# SCH_RP2040_Carrier_Board_for_AC_and_Meas.net
KiCad netlist of a schematic drawn in EasyEDA
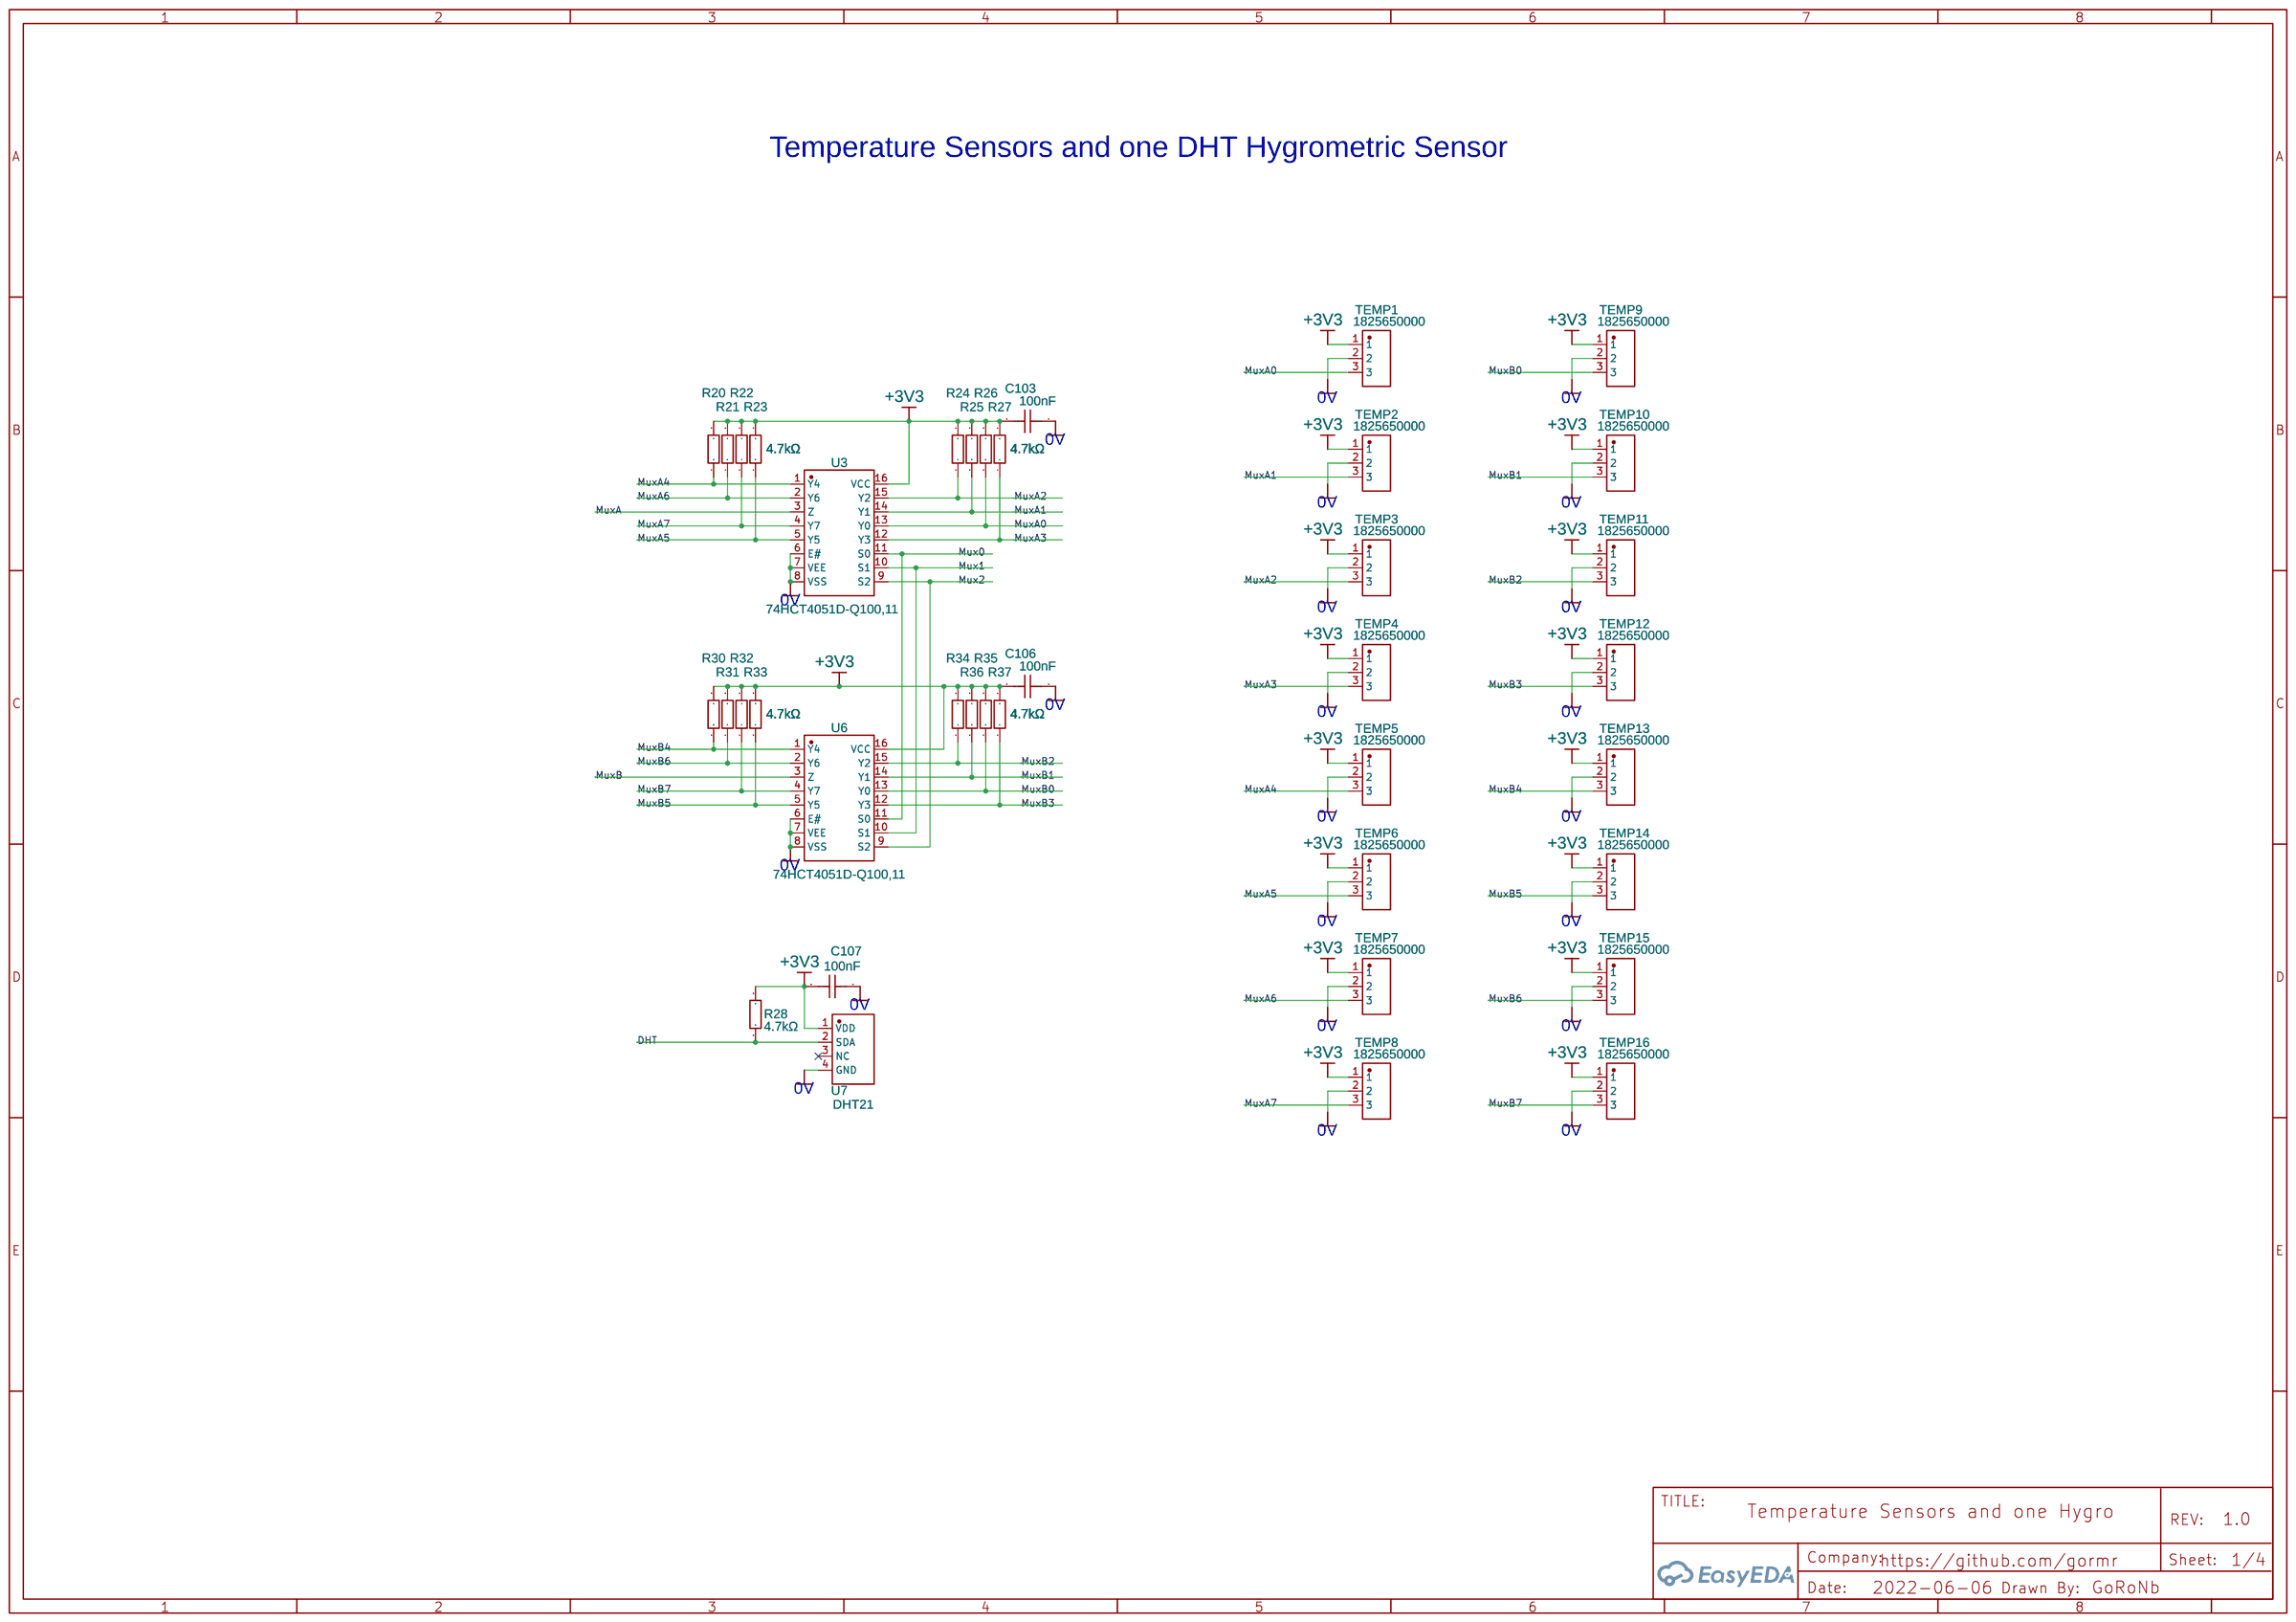
[diagram p0: Temperature/Analog Multiplexer]
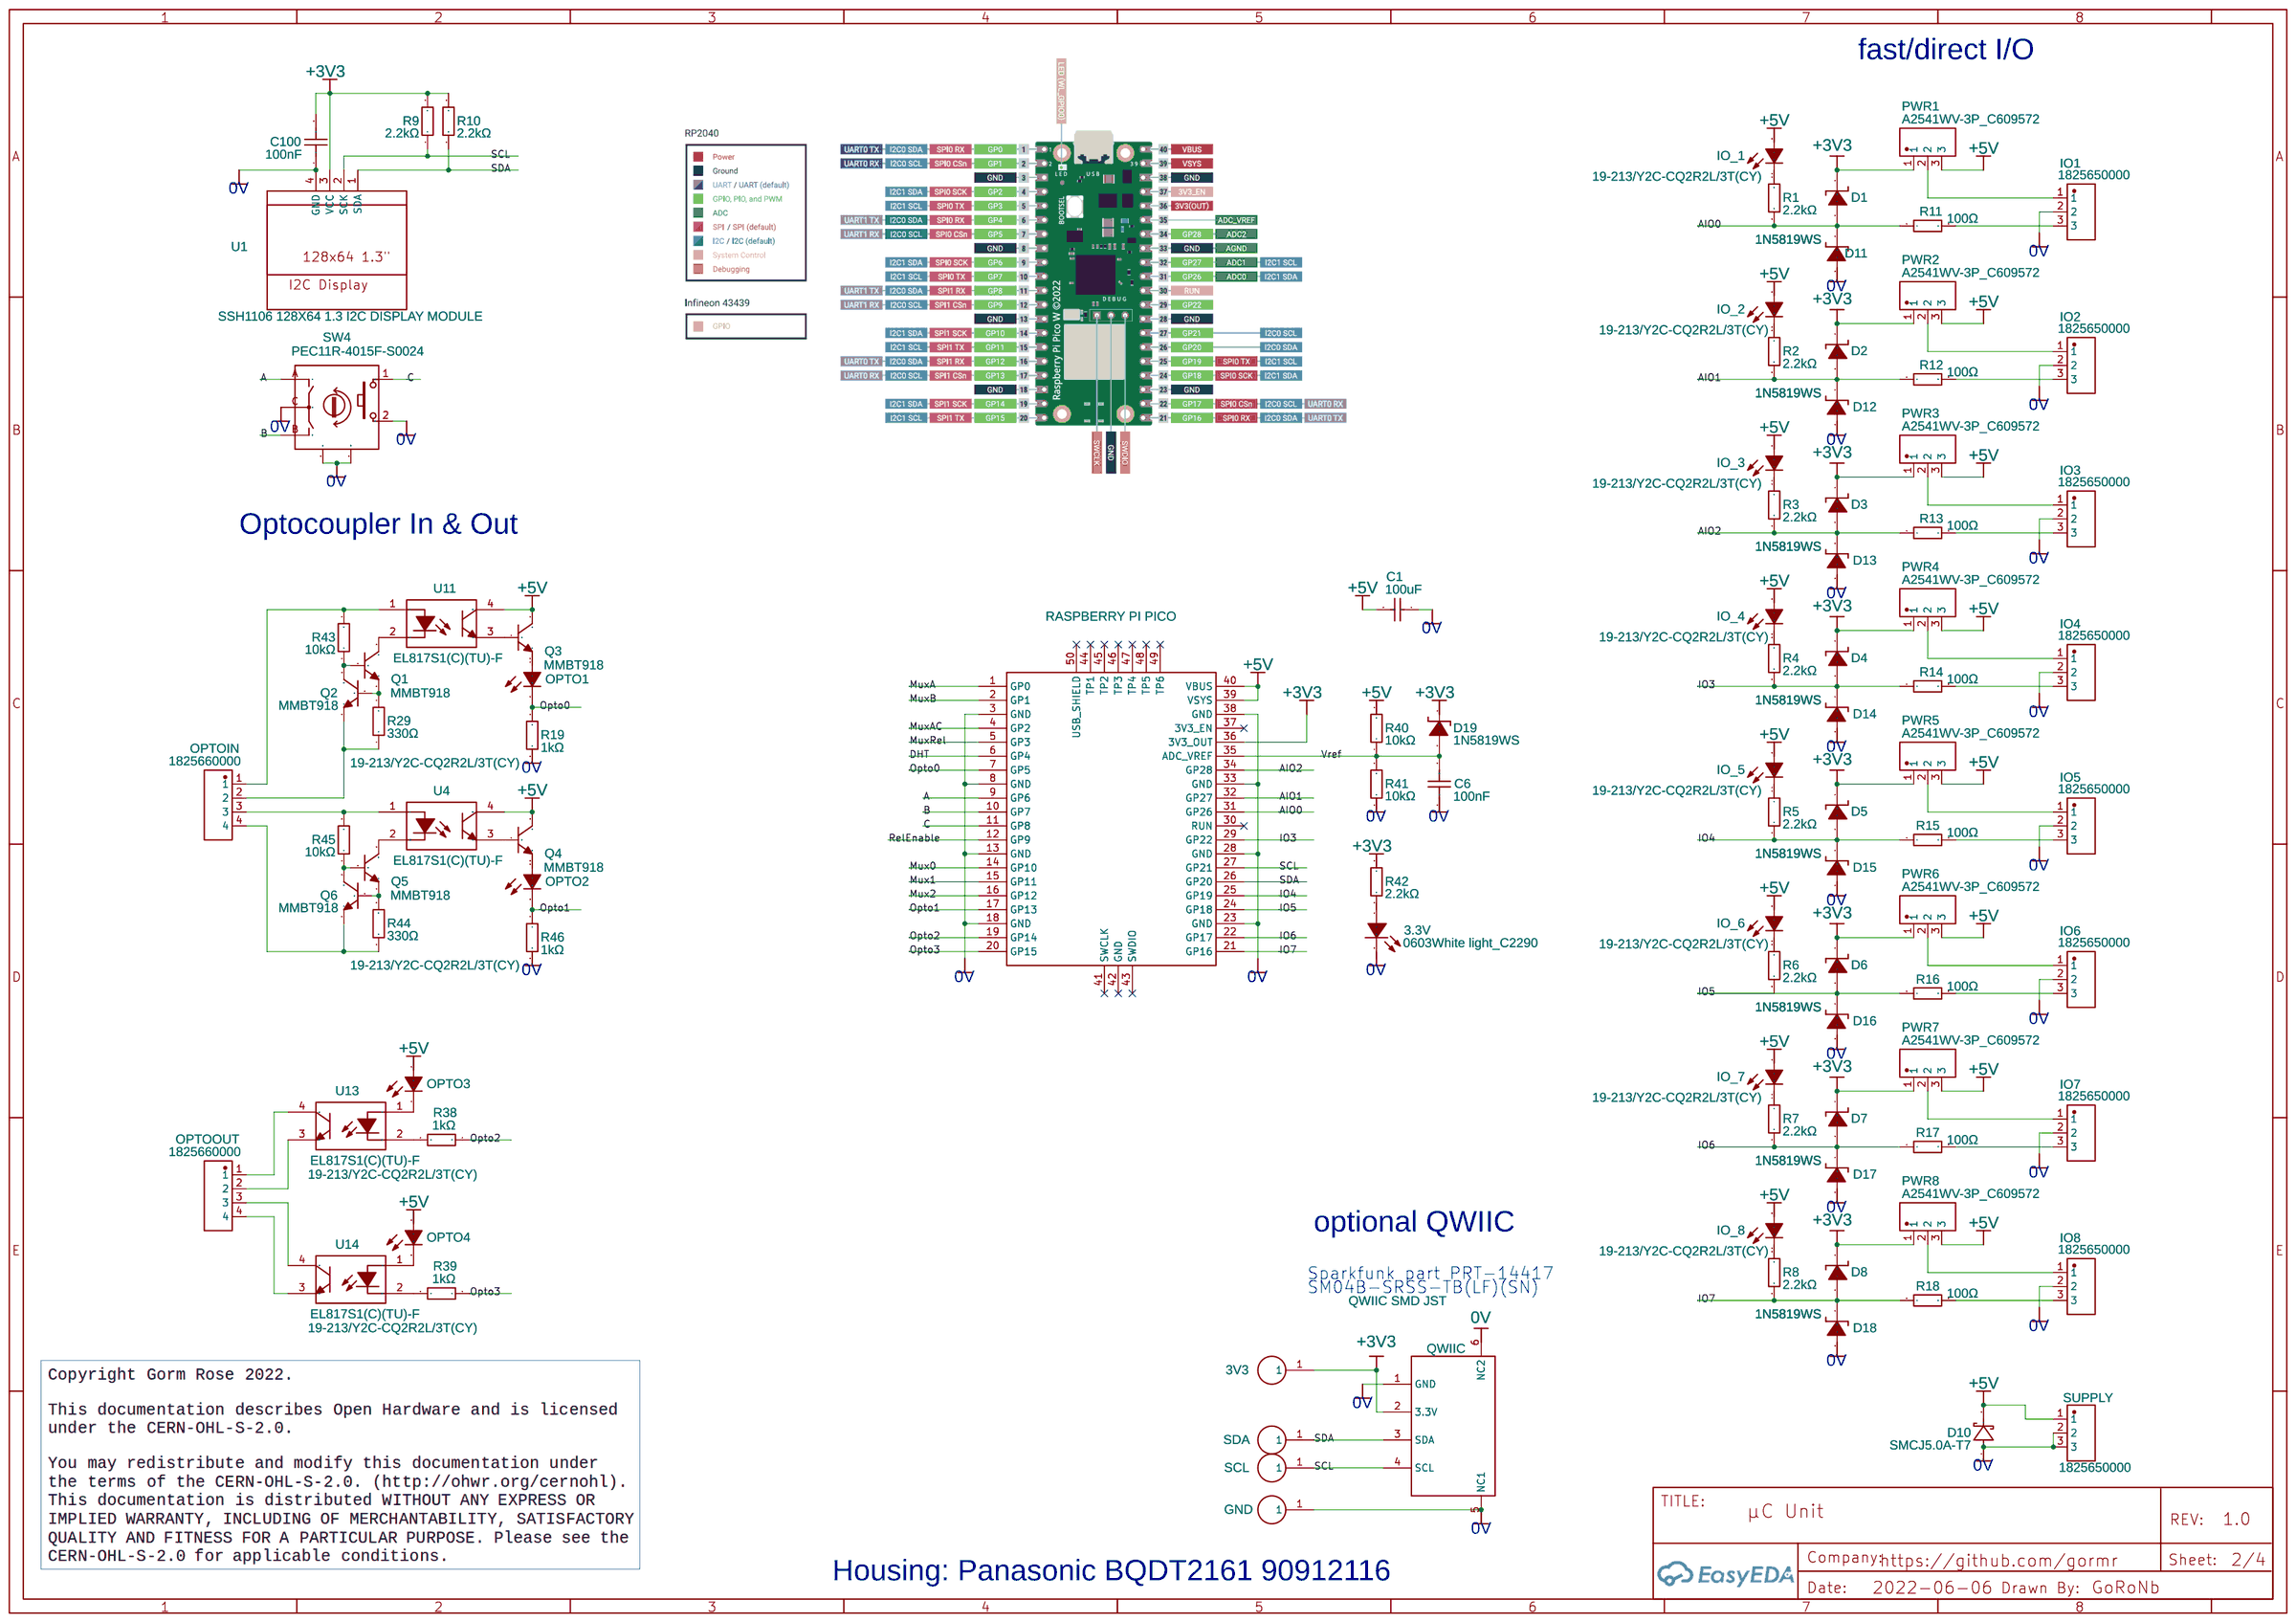
[diagram p1: Controller Unit]
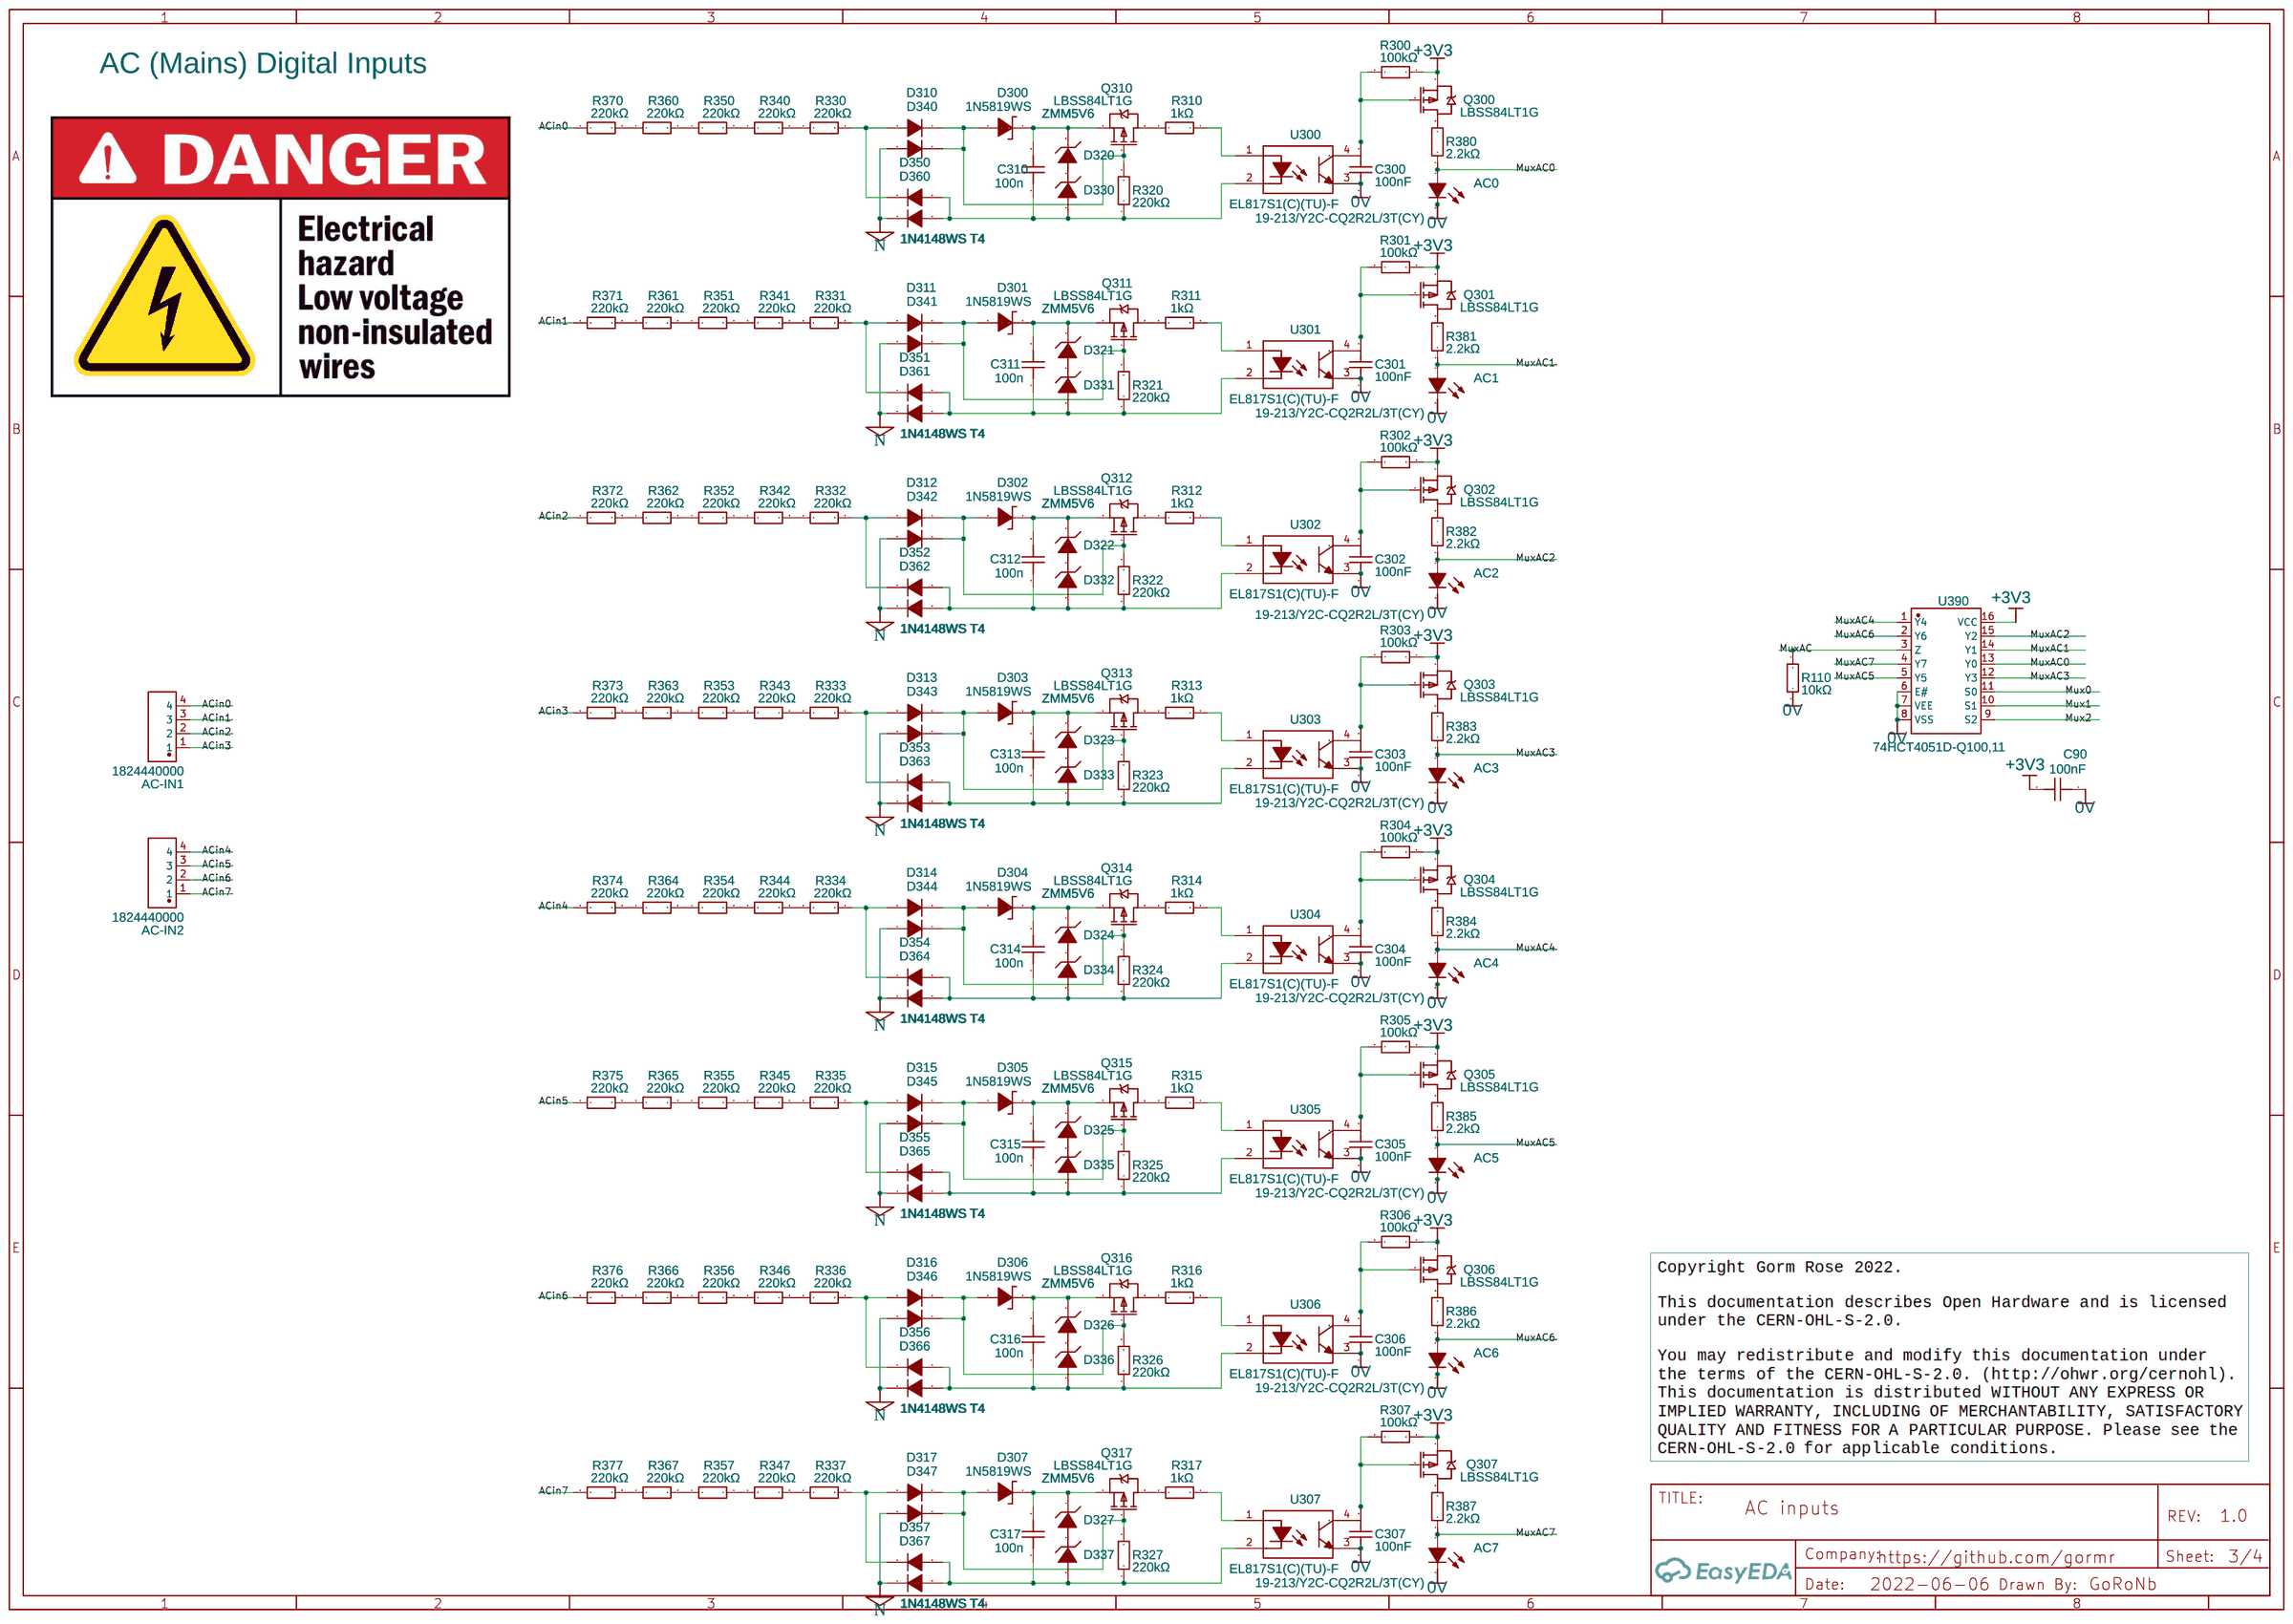
[diagram p2: AC inputs]
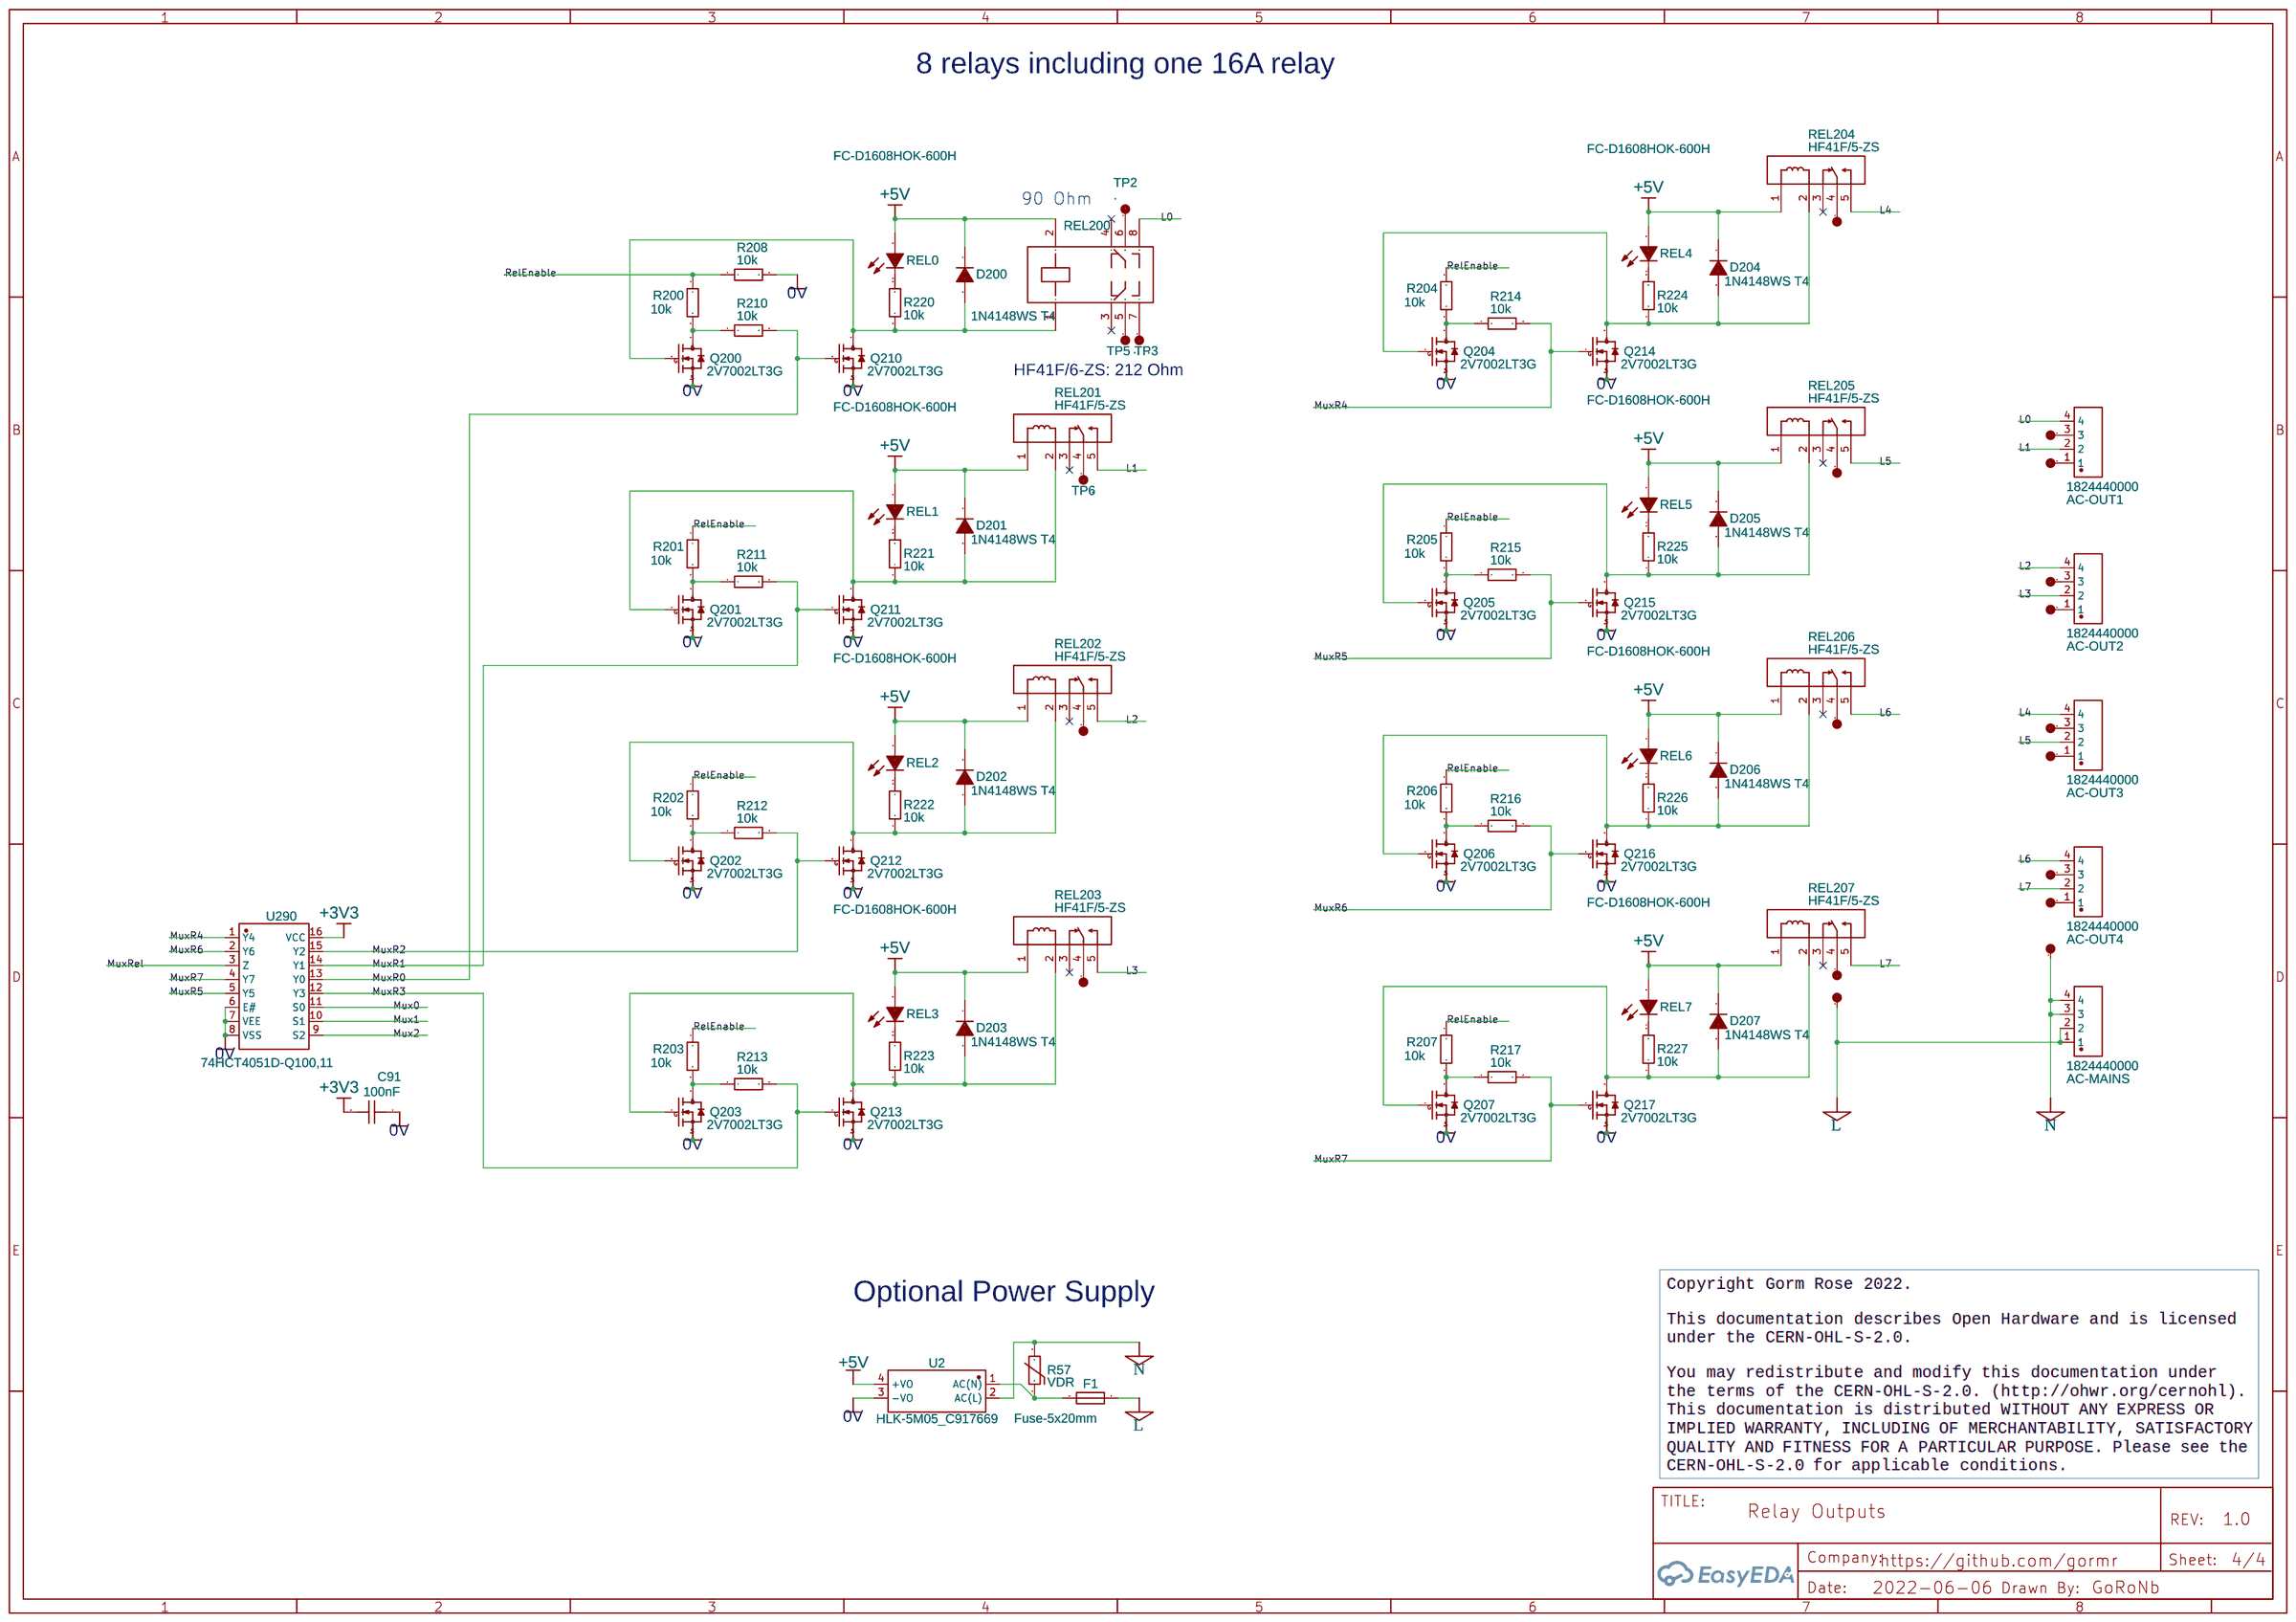
[diagram p3: Relay Outputs]

(export (version "E")
  (design (tool "Eeschema 10.0.6"))
  (components
    (comp (ref "C103")
      (value "100nF")
      (fields
        (field (name "BOM_Manufacturer Part") "CC0603KRX7R9BB104")
        (field (name "BOM_Supplier Part") "C14663")
      )
      (libsource (lib "") (part "CC0603KRX7R9BB104"))
    )
    (comp (ref "C106")
      (value "100nF")
      (fields
        (field (name "BOM_Manufacturer Part") "CC0603KRX7R9BB104")
        (field (name "BOM_Supplier Part") "C14663")
      )
      (libsource (lib "") (part "CC0603KRX7R9BB104"))
    )
    (comp (ref "C107")
      (value "100nF")
      (fields
        (field (name "BOM_Manufacturer Part") "CC0603KRX7R9BB104")
        (field (name "BOM_Supplier Part") "C14663")
      )
      (libsource (lib "") (part "CC0603KRX7R9BB104"))
    )
    (comp (ref "R20")
      (value "4.7kΩ")
      (fields
        (field (name "BOM_Manufacturer Part") "0603WAF4701T5E")
        (field (name "BOM_Supplier Part") "C23162")
      )
      (libsource (lib "") (part "0603WAF4701T5E"))
    )
    (comp (ref "R21")
      (value "4.7kΩ")
      (fields
        (field (name "BOM_Manufacturer Part") "0603WAF4701T5E")
        (field (name "BOM_Supplier Part") "C23162")
      )
      (libsource (lib "") (part "0603WAF4701T5E"))
    )
    (comp (ref "R22")
      (value "4.7kΩ")
      (fields
        (field (name "BOM_Manufacturer Part") "0603WAF4701T5E")
        (field (name "BOM_Supplier Part") "C23162")
      )
      (libsource (lib "") (part "0603WAF4701T5E"))
    )
    (comp (ref "R23")
      (value "4.7kΩ")
      (fields
        (field (name "BOM_Manufacturer Part") "0603WAF4701T5E")
        (field (name "BOM_Supplier Part") "C23162")
      )
      (libsource (lib "") (part "0603WAF4701T5E"))
    )
    (comp (ref "R24")
      (value "4.7kΩ")
      (fields
        (field (name "BOM_Manufacturer Part") "0603WAF4701T5E")
        (field (name "BOM_Supplier Part") "C23162")
      )
      (libsource (lib "") (part "0603WAF4701T5E"))
    )
    (comp (ref "R25")
      (value "4.7kΩ")
      (fields
        (field (name "BOM_Manufacturer Part") "0603WAF4701T5E")
        (field (name "BOM_Supplier Part") "C23162")
      )
      (libsource (lib "") (part "0603WAF4701T5E"))
    )
    (comp (ref "R26")
      (value "4.7kΩ")
      (fields
        (field (name "BOM_Manufacturer Part") "0603WAF4701T5E")
        (field (name "BOM_Supplier Part") "C23162")
      )
      (libsource (lib "") (part "0603WAF4701T5E"))
    )
    (comp (ref "R27")
      (value "4.7kΩ")
      (fields
        (field (name "BOM_Manufacturer Part") "0603WAF4701T5E")
        (field (name "BOM_Supplier Part") "C23162")
      )
      (libsource (lib "") (part "0603WAF4701T5E"))
    )
    (comp (ref "R28")
      (value "4.7kΩ")
      (fields
        (field (name "BOM_Manufacturer Part") "0603WAF4701T5E")
        (field (name "BOM_Supplier Part") "C23162")
      )
      (libsource (lib "") (part "0603WAF4701T5E"))
    )
    (comp (ref "R30")
      (value "4.7kΩ")
      (fields
        (field (name "BOM_Manufacturer Part") "0603WAF4701T5E")
        (field (name "BOM_Supplier Part") "C23162")
      )
      (libsource (lib "") (part "0603WAF4701T5E"))
    )
    (comp (ref "R31")
      (value "4.7kΩ")
      (fields
        (field (name "BOM_Manufacturer Part") "0603WAF4701T5E")
        (field (name "BOM_Supplier Part") "C23162")
      )
      (libsource (lib "") (part "0603WAF4701T5E"))
    )
    (comp (ref "R32")
      (value "4.7kΩ")
      (fields
        (field (name "BOM_Manufacturer Part") "0603WAF4701T5E")
        (field (name "BOM_Supplier Part") "C23162")
      )
      (libsource (lib "") (part "0603WAF4701T5E"))
    )
    (comp (ref "R33")
      (value "4.7kΩ")
      (fields
        (field (name "BOM_Manufacturer Part") "0603WAF4701T5E")
        (field (name "BOM_Supplier Part") "C23162")
      )
      (libsource (lib "") (part "0603WAF4701T5E"))
    )
    (comp (ref "R34")
      (value "4.7kΩ")
      (fields
        (field (name "BOM_Manufacturer Part") "0603WAF4701T5E")
        (field (name "BOM_Supplier Part") "C23162")
      )
      (libsource (lib "") (part "0603WAF4701T5E"))
    )
    (comp (ref "R35")
      (value "4.7kΩ")
      (fields
        (field (name "BOM_Manufacturer Part") "0603WAF4701T5E")
        (field (name "BOM_Supplier Part") "C23162")
      )
      (libsource (lib "") (part "0603WAF4701T5E"))
    )
    (comp (ref "R36")
      (value "4.7kΩ")
      (fields
        (field (name "BOM_Manufacturer Part") "0603WAF4701T5E")
        (field (name "BOM_Supplier Part") "C23162")
      )
      (libsource (lib "") (part "0603WAF4701T5E"))
    )
    (comp (ref "R37")
      (value "4.7kΩ")
      (fields
        (field (name "BOM_Manufacturer Part") "0603WAF4701T5E")
        (field (name "BOM_Supplier Part") "C23162")
      )
      (libsource (lib "") (part "0603WAF4701T5E"))
    )
    (comp (ref "TEMP1")
      (value "1825650000")
      (fields (field (name "BOM_Supplier Part") "281-2043-ND"))
      (libsource (lib "") (part "1825650000"))
    )
    (comp (ref "TEMP2")
      (value "1825650000")
      (fields (field (name "BOM_Supplier Part") "281-2043-ND"))
      (libsource (lib "") (part "1825650000"))
    )
    (comp (ref "TEMP3")
      (value "1825650000")
      (fields (field (name "BOM_Supplier Part") "281-2043-ND"))
      (libsource (lib "") (part "1825650000"))
    )
    (comp (ref "TEMP4")
      (value "1825650000")
      (fields (field (name "BOM_Supplier Part") "281-2043-ND"))
      (libsource (lib "") (part "1825650000"))
    )
    (comp (ref "TEMP5")
      (value "1825650000")
      (fields (field (name "BOM_Supplier Part") "281-2043-ND"))
      (libsource (lib "") (part "1825650000"))
    )
    (comp (ref "TEMP6")
      (value "1825650000")
      (fields (field (name "BOM_Supplier Part") "281-2043-ND"))
      (libsource (lib "") (part "1825650000"))
    )
    (comp (ref "TEMP7")
      (value "1825650000")
      (fields (field (name "BOM_Supplier Part") "281-2043-ND"))
      (libsource (lib "") (part "1825650000"))
    )
    (comp (ref "TEMP8")
      (value "1825650000")
      (fields (field (name "BOM_Supplier Part") "281-2043-ND"))
      (libsource (lib "") (part "1825650000"))
    )
    (comp (ref "TEMP9")
      (value "1825650000")
      (fields (field (name "BOM_Supplier Part") "281-2043-ND"))
      (libsource (lib "") (part "1825650000"))
    )
    (comp (ref "TEMP10")
      (value "1825650000")
      (fields (field (name "BOM_Supplier Part") "281-2043-ND"))
      (libsource (lib "") (part "1825650000"))
    )
    (comp (ref "TEMP11")
      (value "1825650000")
      (fields (field (name "BOM_Supplier Part") "281-2043-ND"))
      (libsource (lib "") (part "1825650000"))
    )
    (comp (ref "TEMP12")
      (value "1825650000")
      (fields (field (name "BOM_Supplier Part") "281-2043-ND"))
      (libsource (lib "") (part "1825650000"))
    )
    (comp (ref "TEMP13")
      (value "1825650000")
      (fields (field (name "BOM_Supplier Part") "281-2043-ND"))
      (libsource (lib "") (part "1825650000"))
    )
    (comp (ref "TEMP14")
      (value "1825650000")
      (fields (field (name "BOM_Supplier Part") "281-2043-ND"))
      (libsource (lib "") (part "1825650000"))
    )
    (comp (ref "TEMP15")
      (value "1825650000")
      (fields (field (name "BOM_Supplier Part") "281-2043-ND"))
      (libsource (lib "") (part "1825650000"))
    )
    (comp (ref "TEMP16")
      (value "1825650000")
      (fields (field (name "BOM_Supplier Part") "281-2043-ND"))
      (libsource (lib "") (part "1825650000"))
    )
    (comp (ref "U3")
      (value "74HCT4051D-Q100,11")
      (fields (field (name "BOM_Supplier Part") "C547698"))
      (libsource (lib "") (part "74HCT4051D-Q100,11"))
    )
    (comp (ref "U6")
      (value "74HCT4051D-Q100,11")
      (fields (field (name "BOM_Supplier Part") "C547698"))
      (libsource (lib "") (part "74HCT4051D-Q100,11"))
    )
    (comp (ref "U7")
      (value "DHT21")
      (fields (field (name "BOM_Supplier Part") "C2880290"))
      (libsource (lib "") (part "DHT21"))
    )
    (comp (ref "3.3V")
      (value "0603White light_C2290")
      (fields
        (field (name "BOM_Manufacturer Part") "0603White light")
        (field (name "BOM_Supplier Part") "C2290")
      )
      (libsource (lib "") (part "0603White light_C2290"))
    )
    (comp (ref "3V3") (value "10mA max.") (libsource (lib "") (part "Testpoint_1")))
    (comp (ref "C1")
      (value "100uF")
      (fields
        (field (name "BOM_Manufacturer Part") "CL31A107MQHNNNE")
        (field (name "BOM_Supplier Part") "C15008")
      )
      (libsource (lib "") (part "CL31A107MQHNNNE"))
    )
    (comp (ref "C6")
      (value "100nF")
      (fields
        (field (name "BOM_Manufacturer Part") "CC0603KRX7R9BB104")
        (field (name "BOM_Supplier Part") "C14663")
      )
      (libsource (lib "") (part "CC0603KRX7R9BB104_1"))
    )
    (comp (ref "C100")
      (value "100nF")
      (fields
        (field (name "BOM_Manufacturer Part") "CC0603KRX7R9BB104")
        (field (name "BOM_Supplier Part") "C14663")
      )
      (libsource (lib "") (part "CC0603KRX7R9BB104"))
    )
    (comp (ref "D1")
      (value "1N5819WS")
      (fields (field (name "BOM_Supplier Part") "C191023"))
      (libsource (lib "") (part "1N5819WS_1"))
    )
    (comp (ref "D2")
      (value "1N5819WS")
      (fields (field (name "BOM_Supplier Part") "C191023"))
      (libsource (lib "") (part "1N5819WS_1"))
    )
    (comp (ref "D3")
      (value "1N5819WS")
      (fields (field (name "BOM_Supplier Part") "C191023"))
      (libsource (lib "") (part "1N5819WS_1"))
    )
    (comp (ref "D4")
      (value "1N5819WS")
      (fields (field (name "BOM_Supplier Part") "C191023"))
      (libsource (lib "") (part "1N5819WS_1"))
    )
    (comp (ref "D5")
      (value "1N5819WS")
      (fields (field (name "BOM_Supplier Part") "C191023"))
      (libsource (lib "") (part "1N5819WS_1"))
    )
    (comp (ref "D6")
      (value "1N5819WS")
      (fields (field (name "BOM_Supplier Part") "C191023"))
      (libsource (lib "") (part "1N5819WS_1"))
    )
    (comp (ref "D7")
      (value "1N5819WS")
      (fields (field (name "BOM_Supplier Part") "C191023"))
      (libsource (lib "") (part "1N5819WS_1"))
    )
    (comp (ref "D8")
      (value "1N5819WS")
      (fields (field (name "BOM_Supplier Part") "C191023"))
      (libsource (lib "") (part "1N5819WS_1"))
    )
    (comp (ref "D10")
      (value "SMCJ5.0A-T7")
      (fields (field (name "BOM_Supplier Part") "C1983017"))
      (libsource (lib "") (part "SMCJ5.0A-T7"))
    )
    (comp (ref "D11")
      (value "1N5819WS")
      (fields (field (name "BOM_Supplier Part") "C191023"))
      (libsource (lib "") (part "1N5819WS"))
    )
    (comp (ref "D12")
      (value "1N5819WS")
      (fields (field (name "BOM_Supplier Part") "C191023"))
      (libsource (lib "") (part "1N5819WS"))
    )
    (comp (ref "D13")
      (value "1N5819WS")
      (fields (field (name "BOM_Supplier Part") "C191023"))
      (libsource (lib "") (part "1N5819WS"))
    )
    (comp (ref "D14")
      (value "1N5819WS")
      (fields (field (name "BOM_Supplier Part") "C191023"))
      (libsource (lib "") (part "1N5819WS"))
    )
    (comp (ref "D15")
      (value "1N5819WS")
      (fields (field (name "BOM_Supplier Part") "C191023"))
      (libsource (lib "") (part "1N5819WS"))
    )
    (comp (ref "D16")
      (value "1N5819WS")
      (fields (field (name "BOM_Supplier Part") "C191023"))
      (libsource (lib "") (part "1N5819WS"))
    )
    (comp (ref "D17")
      (value "1N5819WS")
      (fields (field (name "BOM_Supplier Part") "C191023"))
      (libsource (lib "") (part "1N5819WS"))
    )
    (comp (ref "D18")
      (value "1N5819WS")
      (fields (field (name "BOM_Supplier Part") "C191023"))
      (libsource (lib "") (part "1N5819WS"))
    )
    (comp (ref "D19")
      (value "1N5819WS")
      (fields (field (name "BOM_Supplier Part") "C191023"))
      (libsource (lib "") (part "1N5819WS_2"))
    )
    (comp (ref "GND") (value "10mA max.") (libsource (lib "") (part "Testpoint")))
    (comp (ref "GP1")
      (value "RASPBERRY PI PICO")
      (fields (field (name "BOM_Manufacturer Part") "RPi Pico"))
      (libsource (lib "") (part "RASPBERRY PI PICO"))
    )
    (comp (ref "IO1")
      (value "1825650000")
      (fields (field (name "BOM_Supplier Part") "281-2043-ND"))
      (libsource (lib "") (part "1825650000"))
    )
    (comp (ref "IO2")
      (value "1825650000")
      (fields (field (name "BOM_Supplier Part") "281-2043-ND"))
      (libsource (lib "") (part "1825650000"))
    )
    (comp (ref "IO3")
      (value "1825650000")
      (fields (field (name "BOM_Supplier Part") "281-2043-ND"))
      (libsource (lib "") (part "1825650000"))
    )
    (comp (ref "IO4")
      (value "1825650000")
      (fields (field (name "BOM_Supplier Part") "281-2043-ND"))
      (libsource (lib "") (part "1825650000"))
    )
    (comp (ref "IO5")
      (value "1825650000")
      (fields (field (name "BOM_Supplier Part") "281-2043-ND"))
      (libsource (lib "") (part "1825650000"))
    )
    (comp (ref "IO6")
      (value "1825650000")
      (fields (field (name "BOM_Supplier Part") "281-2043-ND"))
      (libsource (lib "") (part "1825650000"))
    )
    (comp (ref "IO7")
      (value "1825650000")
      (fields (field (name "BOM_Supplier Part") "281-2043-ND"))
      (libsource (lib "") (part "1825650000"))
    )
    (comp (ref "IO8")
      (value "1825650000")
      (fields (field (name "BOM_Supplier Part") "281-2043-ND"))
      (libsource (lib "") (part "1825650000"))
    )
    (comp (ref "IO_1")
      (value "19-213/Y2C-CQ2R2L/3T(CY)")
      (fields (field (name "BOM_Supplier Part") "C72038"))
      (libsource (lib "") (part "FC-D1608HYK-588J"))
    )
    (comp (ref "IO_2")
      (value "19-213/Y2C-CQ2R2L/3T(CY)")
      (fields (field (name "BOM_Supplier Part") "C72038"))
      (libsource (lib "") (part "FC-D1608HYK-588J"))
    )
    (comp (ref "IO_3")
      (value "19-213/Y2C-CQ2R2L/3T(CY)")
      (fields (field (name "BOM_Supplier Part") "C72038"))
      (libsource (lib "") (part "FC-D1608HYK-588J"))
    )
    (comp (ref "IO_4")
      (value "19-213/Y2C-CQ2R2L/3T(CY)")
      (fields (field (name "BOM_Supplier Part") "C72038"))
      (libsource (lib "") (part "FC-D1608HYK-588J"))
    )
    (comp (ref "IO_5")
      (value "19-213/Y2C-CQ2R2L/3T(CY)")
      (fields (field (name "BOM_Supplier Part") "C72038"))
      (libsource (lib "") (part "FC-D1608HYK-588J"))
    )
    (comp (ref "IO_6")
      (value "19-213/Y2C-CQ2R2L/3T(CY)")
      (fields (field (name "BOM_Supplier Part") "C72038"))
      (libsource (lib "") (part "FC-D1608HYK-588J"))
    )
    (comp (ref "IO_7")
      (value "19-213/Y2C-CQ2R2L/3T(CY)")
      (fields (field (name "BOM_Supplier Part") "C72038"))
      (libsource (lib "") (part "FC-D1608HYK-588J"))
    )
    (comp (ref "IO_8")
      (value "19-213/Y2C-CQ2R2L/3T(CY)")
      (fields (field (name "BOM_Supplier Part") "C72038"))
      (libsource (lib "") (part "FC-D1608HYK-588J"))
    )
    (comp (ref "OPTO1")
      (value "19-213/Y2C-CQ2R2L/3T(CY)")
      (fields (field (name "BOM_Supplier Part") "C72038"))
      (libsource (lib "") (part "19-213/Y2C-CQ2R2L/3T(CY)"))
    )
    (comp (ref "OPTO2")
      (value "19-213/Y2C-CQ2R2L/3T(CY)")
      (fields (field (name "BOM_Supplier Part") "C72038"))
      (libsource (lib "") (part "19-213/Y2C-CQ2R2L/3T(CY)"))
    )
    (comp (ref "OPTO3")
      (value "19-213/Y2C-CQ2R2L/3T(CY)")
      (fields (field (name "BOM_Supplier Part") "C72038"))
      (libsource (lib "") (part "19-213/Y2C-CQ2R2L/3T(CY)"))
    )
    (comp (ref "OPTO4")
      (value "19-213/Y2C-CQ2R2L/3T(CY)")
      (fields (field (name "BOM_Supplier Part") "C72038"))
      (libsource (lib "") (part "19-213/Y2C-CQ2R2L/3T(CY)"))
    )
    (comp (ref "OPTOIN")
      (value "1825660000")
      (fields (field (name "BOM_Supplier Part") "281-2044-ND"))
      (libsource (lib "") (part "1825660000_1"))
    )
    (comp (ref "OPTOOUT")
      (value "1825660000")
      (fields (field (name "BOM_Supplier Part") "281-2044-ND"))
      (libsource (lib "") (part "1825660000"))
    )
    (comp (ref "PWR1")
      (value "A2541WV-3P_C609572")
      (fields
        (field (name "BOM_Manufacturer Part") "A2541WV-3P")
        (field (name "BOM_Supplier Part") "C609572")
      )
      (libsource (lib "") (part "A2541WV-3P_C609572"))
    )
    (comp (ref "PWR2")
      (value "A2541WV-3P_C609572")
      (fields
        (field (name "BOM_Manufacturer Part") "A2541WV-3P")
        (field (name "BOM_Supplier Part") "C609572")
      )
      (libsource (lib "") (part "A2541WV-3P_C609572"))
    )
    (comp (ref "PWR3")
      (value "A2541WV-3P_C609572")
      (fields
        (field (name "BOM_Manufacturer Part") "A2541WV-3P")
        (field (name "BOM_Supplier Part") "C609572")
      )
      (libsource (lib "") (part "A2541WV-3P_C609572"))
    )
    (comp (ref "PWR4")
      (value "A2541WV-3P_C609572")
      (fields
        (field (name "BOM_Manufacturer Part") "A2541WV-3P")
        (field (name "BOM_Supplier Part") "C609572")
      )
      (libsource (lib "") (part "A2541WV-3P_C609572"))
    )
    (comp (ref "PWR5")
      (value "A2541WV-3P_C609572")
      (fields
        (field (name "BOM_Manufacturer Part") "A2541WV-3P")
        (field (name "BOM_Supplier Part") "C609572")
      )
      (libsource (lib "") (part "A2541WV-3P_C609572"))
    )
    (comp (ref "PWR6")
      (value "A2541WV-3P_C609572")
      (fields
        (field (name "BOM_Manufacturer Part") "A2541WV-3P")
        (field (name "BOM_Supplier Part") "C609572")
      )
      (libsource (lib "") (part "A2541WV-3P_C609572"))
    )
    (comp (ref "PWR7")
      (value "A2541WV-3P_C609572")
      (fields
        (field (name "BOM_Manufacturer Part") "A2541WV-3P")
        (field (name "BOM_Supplier Part") "C609572")
      )
      (libsource (lib "") (part "A2541WV-3P_C609572"))
    )
    (comp (ref "PWR8")
      (value "A2541WV-3P_C609572")
      (fields
        (field (name "BOM_Manufacturer Part") "A2541WV-3P")
        (field (name "BOM_Supplier Part") "C609572")
      )
      (libsource (lib "") (part "A2541WV-3P_C609572"))
    )
    (comp (ref "Q1")
      (value "MMBT918")
      (fields (field (name "BOM_Supplier Part") "C184118"))
      (libsource (lib "") (part "MMBT918"))
    )
    (comp (ref "Q2")
      (value "MMBT918")
      (fields (field (name "BOM_Supplier Part") "C184118"))
      (libsource (lib "") (part "MMBT918_1"))
    )
    (comp (ref "Q3")
      (value "MMBT918")
      (fields (field (name "BOM_Supplier Part") "C184118"))
      (libsource (lib "") (part "MMBT918"))
    )
    (comp (ref "Q4")
      (value "MMBT918")
      (fields (field (name "BOM_Supplier Part") "C184118"))
      (libsource (lib "") (part "MMBT918"))
    )
    (comp (ref "Q5")
      (value "MMBT918")
      (fields (field (name "BOM_Supplier Part") "C184118"))
      (libsource (lib "") (part "MMBT918"))
    )
    (comp (ref "Q6")
      (value "MMBT918")
      (fields (field (name "BOM_Supplier Part") "C184118"))
      (libsource (lib "") (part "MMBT918_1"))
    )
    (comp (ref "QWIIC")
      (value "QWIIC SMD JST")
      (fields
        (field (name "BOM_Manufacturer Part") "SM04B-SRSS-TB(LF)(SN)")
        (field (name "BOM_Supplier Part") "C160404")
      )
      (libsource (lib "") (part "QWIIC SMD JST"))
    )
    (comp (ref "R1")
      (value "2.2kΩ")
      (fields
        (field (name "BOM_Manufacturer Part") "0603WAF2201T5E")
        (field (name "BOM_Supplier Part") "C4190")
      )
      (libsource (lib "") (part "0603WAF2201T5E_1"))
    )
    (comp (ref "R2")
      (value "2.2kΩ")
      (fields
        (field (name "BOM_Manufacturer Part") "0603WAF2201T5E")
        (field (name "BOM_Supplier Part") "C4190")
      )
      (libsource (lib "") (part "0603WAF2201T5E_1"))
    )
    (comp (ref "R3")
      (value "2.2kΩ")
      (fields
        (field (name "BOM_Manufacturer Part") "0603WAF2201T5E")
        (field (name "BOM_Supplier Part") "C4190")
      )
      (libsource (lib "") (part "0603WAF2201T5E_1"))
    )
    (comp (ref "R4")
      (value "2.2kΩ")
      (fields
        (field (name "BOM_Manufacturer Part") "0603WAF2201T5E")
        (field (name "BOM_Supplier Part") "C4190")
      )
      (libsource (lib "") (part "0603WAF2201T5E_1"))
    )
    (comp (ref "R5")
      (value "2.2kΩ")
      (fields
        (field (name "BOM_Manufacturer Part") "0603WAF2201T5E")
        (field (name "BOM_Supplier Part") "C4190")
      )
      (libsource (lib "") (part "0603WAF2201T5E_1"))
    )
    (comp (ref "R6")
      (value "2.2kΩ")
      (fields
        (field (name "BOM_Manufacturer Part") "0603WAF2201T5E")
        (field (name "BOM_Supplier Part") "C4190")
      )
      (libsource (lib "") (part "0603WAF2201T5E_1"))
    )
    (comp (ref "R7")
      (value "2.2kΩ")
      (fields
        (field (name "BOM_Manufacturer Part") "0603WAF2201T5E")
        (field (name "BOM_Supplier Part") "C4190")
      )
      (libsource (lib "") (part "0603WAF2201T5E_1"))
    )
    (comp (ref "R8")
      (value "2.2kΩ")
      (fields
        (field (name "BOM_Manufacturer Part") "0603WAF2201T5E")
        (field (name "BOM_Supplier Part") "C4190")
      )
      (libsource (lib "") (part "0603WAF2201T5E_1"))
    )
    (comp (ref "R9")
      (value "2.2kΩ")
      (fields
        (field (name "BOM_Manufacturer Part") "0603WAF2201T5E")
        (field (name "BOM_Supplier Part") "C4190")
      )
      (libsource (lib "") (part "0603WAF2201T5E"))
    )
    (comp (ref "R10")
      (value "2.2kΩ")
      (fields
        (field (name "BOM_Manufacturer Part") "0603WAF2201T5E")
        (field (name "BOM_Supplier Part") "C4190")
      )
      (libsource (lib "") (part "0603WAF2201T5E"))
    )
    (comp (ref "R11")
      (value "100Ω")
      (fields
        (field (name "BOM_Manufacturer Part") "0603WAF1000T5E")
        (field (name "BOM_Supplier Part") "C22775")
      )
      (libsource (lib "") (part "0603WAF1000T5E"))
    )
    (comp (ref "R12")
      (value "100Ω")
      (fields
        (field (name "BOM_Manufacturer Part") "0603WAF1000T5E")
        (field (name "BOM_Supplier Part") "C22775")
      )
      (libsource (lib "") (part "0603WAF1000T5E"))
    )
    (comp (ref "R13")
      (value "100Ω")
      (fields
        (field (name "BOM_Manufacturer Part") "0603WAF1000T5E")
        (field (name "BOM_Supplier Part") "C22775")
      )
      (libsource (lib "") (part "0603WAF1000T5E"))
    )
    (comp (ref "R14")
      (value "100Ω")
      (fields
        (field (name "BOM_Manufacturer Part") "0603WAF1000T5E")
        (field (name "BOM_Supplier Part") "C22775")
      )
      (libsource (lib "") (part "0603WAF1000T5E"))
    )
    (comp (ref "R15")
      (value "100Ω")
      (fields
        (field (name "BOM_Manufacturer Part") "0603WAF1000T5E")
        (field (name "BOM_Supplier Part") "C22775")
      )
      (libsource (lib "") (part "0603WAF1000T5E"))
    )
    (comp (ref "R16")
      (value "100Ω")
      (fields
        (field (name "BOM_Manufacturer Part") "0603WAF1000T5E")
        (field (name "BOM_Supplier Part") "C22775")
      )
      (libsource (lib "") (part "0603WAF1000T5E"))
    )
    (comp (ref "R17")
      (value "100Ω")
      (fields
        (field (name "BOM_Manufacturer Part") "0603WAF1000T5E")
        (field (name "BOM_Supplier Part") "C22775")
      )
      (libsource (lib "") (part "0603WAF1000T5E"))
    )
    (comp (ref "R18")
      (value "100Ω")
      (fields
        (field (name "BOM_Manufacturer Part") "0603WAF1000T5E")
        (field (name "BOM_Supplier Part") "C22775")
      )
      (libsource (lib "") (part "0603WAF1000T5E"))
    )
    (comp (ref "R19")
      (value "1kΩ")
      (fields
        (field (name "BOM_Manufacturer Part") "0603WAF1001T5E")
        (field (name "BOM_Supplier Part") "C21190")
      )
      (libsource (lib "") (part "0603WAF1001T5E"))
    )
    (comp (ref "R29")
      (value "330Ω")
      (fields
        (field (name "BOM_Manufacturer Part") "0603WAF3300T5E")
        (field (name "BOM_Supplier Part") "C23138")
      )
      (libsource (lib "") (part "0603WAF3300T5E"))
    )
    (comp (ref "R38")
      (value "1kΩ")
      (fields
        (field (name "BOM_Manufacturer Part") "0603WAF1001T5E")
        (field (name "BOM_Supplier Part") "C21190")
      )
      (libsource (lib "") (part "0603WAF1001T5E_1"))
    )
    (comp (ref "R39")
      (value "1kΩ")
      (fields
        (field (name "BOM_Manufacturer Part") "0603WAF1001T5E")
        (field (name "BOM_Supplier Part") "C21190")
      )
      (libsource (lib "") (part "0603WAF1001T5E_1"))
    )
    (comp (ref "R40")
      (value "10kΩ")
      (fields
        (field (name "BOM_Manufacturer Part") "0603WAF1002T5E")
        (field (name "BOM_Supplier Part") "C25804")
      )
      (libsource (lib "") (part "0603WAF1002T5E"))
    )
    (comp (ref "R41")
      (value "10kΩ")
      (fields
        (field (name "BOM_Manufacturer Part") "0603WAF1002T5E")
        (field (name "BOM_Supplier Part") "C25804")
      )
      (libsource (lib "") (part "0603WAF1002T5E"))
    )
    (comp (ref "R42")
      (value "2.2kΩ")
      (fields
        (field (name "BOM_Manufacturer Part") "0603WAF2201T5E")
        (field (name "BOM_Supplier Part") "C4190")
      )
      (libsource (lib "") (part "0603WAF2201T5E"))
    )
    (comp (ref "R43")
      (value "10kΩ")
      (fields
        (field (name "BOM_Manufacturer Part") "0603WAF1002T5E")
        (field (name "BOM_Supplier Part") "C25804")
      )
      (libsource (lib "") (part "0603WAF1002T5E"))
    )
    (comp (ref "R44")
      (value "330Ω")
      (fields
        (field (name "BOM_Manufacturer Part") "0603WAF3300T5E")
        (field (name "BOM_Supplier Part") "C23138")
      )
      (libsource (lib "") (part "0603WAF3300T5E"))
    )
    (comp (ref "R45")
      (value "10kΩ")
      (fields
        (field (name "BOM_Manufacturer Part") "0603WAF1002T5E")
        (field (name "BOM_Supplier Part") "C25804")
      )
      (libsource (lib "") (part "0603WAF1002T5E"))
    )
    (comp (ref "R46")
      (value "1kΩ")
      (fields
        (field (name "BOM_Manufacturer Part") "0603WAF1001T5E")
        (field (name "BOM_Supplier Part") "C21190")
      )
      (libsource (lib "") (part "0603WAF1001T5E"))
    )
    (comp (ref "SCL") (value "10mA max.") (libsource (lib "") (part "Testpoint_3")))
    (comp (ref "SDA") (value "10mA max.") (libsource (lib "") (part "Testpoint_2")))
    (comp (ref "SUPPLY")
      (value "1825650000")
      (fields (field (name "BOM_Supplier Part") "281-2043-ND"))
      (libsource (lib "") (part "1825650000_1"))
    )
    (comp (ref "SW4")
      (value "PEC11R-4015F-S0024")
      (fields (field (name "BOM_Supplier Part") "C143789"))
      (libsource (lib "") (part "PEC11R-4015F-S0024"))
    )
    (comp (ref "U1")
      (value "SSH1106 128X64 1.3 I2C DISPLAY MODULE")
      (libsource (lib "") (part "SSH1106 128X64 1.3 I2C DISPLAY MODULE"))
    )
    (comp (ref "U4")
      (value "EL817S1(C)(TU)-F")
      (fields (field (name "BOM_Supplier Part") "C106900"))
      (libsource (lib "") (part "EL817S1(C)(TU)-F_1"))
    )
    (comp (ref "U11")
      (value "EL817S1(C)(TU)-F")
      (fields (field (name "BOM_Supplier Part") "C106900"))
      (libsource (lib "") (part "EL817S1(C)(TU)-F_1"))
    )
    (comp (ref "U13")
      (value "EL817S1(C)(TU)-F")
      (fields (field (name "BOM_Supplier Part") "C106900"))
      (libsource (lib "") (part "EL817S1(C)(TU)-F"))
    )
    (comp (ref "U14")
      (value "EL817S1(C)(TU)-F")
      (fields (field (name "BOM_Supplier Part") "C106900"))
      (libsource (lib "") (part "EL817S1(C)(TU)-F"))
    )
    (comp (ref "AC-IN1")
      (value "1824440000")
      (fields (field (name "BOM_Supplier Part") "281-2022-ND"))
      (libsource (lib "") (part "1824440000"))
    )
    (comp (ref "AC-IN2")
      (value "1824440000")
      (fields (field (name "BOM_Supplier Part") "281-2022-ND"))
      (libsource (lib "") (part "1824440000"))
    )
    (comp (ref "AC0")
      (value "19-213/Y2C-CQ2R2L/3T(CY)")
      (fields (field (name "BOM_Supplier Part") "C72038"))
      (libsource (lib "") (part "19-213/Y2C-CQ2R2L/3T(CY)"))
    )
    (comp (ref "AC1")
      (value "19-213/Y2C-CQ2R2L/3T(CY)")
      (fields (field (name "BOM_Supplier Part") "C72038"))
      (libsource (lib "") (part "19-213/Y2C-CQ2R2L/3T(CY)"))
    )
    (comp (ref "AC2")
      (value "19-213/Y2C-CQ2R2L/3T(CY)")
      (fields (field (name "BOM_Supplier Part") "C72038"))
      (libsource (lib "") (part "19-213/Y2C-CQ2R2L/3T(CY)"))
    )
    (comp (ref "AC3")
      (value "19-213/Y2C-CQ2R2L/3T(CY)")
      (fields (field (name "BOM_Supplier Part") "C72038"))
      (libsource (lib "") (part "19-213/Y2C-CQ2R2L/3T(CY)"))
    )
    (comp (ref "AC4")
      (value "19-213/Y2C-CQ2R2L/3T(CY)")
      (fields (field (name "BOM_Supplier Part") "C72038"))
      (libsource (lib "") (part "19-213/Y2C-CQ2R2L/3T(CY)"))
    )
    (comp (ref "AC5")
      (value "19-213/Y2C-CQ2R2L/3T(CY)")
      (fields (field (name "BOM_Supplier Part") "C72038"))
      (libsource (lib "") (part "19-213/Y2C-CQ2R2L/3T(CY)"))
    )
    (comp (ref "AC6")
      (value "19-213/Y2C-CQ2R2L/3T(CY)")
      (fields (field (name "BOM_Supplier Part") "C72038"))
      (libsource (lib "") (part "19-213/Y2C-CQ2R2L/3T(CY)"))
    )
    (comp (ref "AC7")
      (value "19-213/Y2C-CQ2R2L/3T(CY)")
      (fields (field (name "BOM_Supplier Part") "C72038"))
      (libsource (lib "") (part "19-213/Y2C-CQ2R2L/3T(CY)"))
    )
    (comp (ref "C90")
      (value "100nF")
      (fields
        (field (name "BOM_Manufacturer Part") "CC0603KRX7R9BB104")
        (field (name "BOM_Supplier Part") "C14663")
      )
      (libsource (lib "") (part "CC0603KRX7R9BB104_1"))
    )
    (comp (ref "C300")
      (value "100nF")
      (fields
        (field (name "BOM_Manufacturer Part") "CC0603KRX7R9BB104")
        (field (name "BOM_Supplier Part") "C14663")
      )
      (libsource (lib "") (part "CC0603KRX7R9BB104"))
    )
    (comp (ref "C301")
      (value "100nF")
      (fields
        (field (name "BOM_Manufacturer Part") "CC0603KRX7R9BB104")
        (field (name "BOM_Supplier Part") "C14663")
      )
      (libsource (lib "") (part "CC0603KRX7R9BB104"))
    )
    (comp (ref "C302")
      (value "100nF")
      (fields
        (field (name "BOM_Manufacturer Part") "CC0603KRX7R9BB104")
        (field (name "BOM_Supplier Part") "C14663")
      )
      (libsource (lib "") (part "CC0603KRX7R9BB104"))
    )
    (comp (ref "C303")
      (value "100nF")
      (fields
        (field (name "BOM_Manufacturer Part") "CC0603KRX7R9BB104")
        (field (name "BOM_Supplier Part") "C14663")
      )
      (libsource (lib "") (part "CC0603KRX7R9BB104"))
    )
    (comp (ref "C304")
      (value "100nF")
      (fields
        (field (name "BOM_Manufacturer Part") "CC0603KRX7R9BB104")
        (field (name "BOM_Supplier Part") "C14663")
      )
      (libsource (lib "") (part "CC0603KRX7R9BB104"))
    )
    (comp (ref "C305")
      (value "100nF")
      (fields
        (field (name "BOM_Manufacturer Part") "CC0603KRX7R9BB104")
        (field (name "BOM_Supplier Part") "C14663")
      )
      (libsource (lib "") (part "CC0603KRX7R9BB104"))
    )
    (comp (ref "C306")
      (value "100nF")
      (fields
        (field (name "BOM_Manufacturer Part") "CC0603KRX7R9BB104")
        (field (name "BOM_Supplier Part") "C14663")
      )
      (libsource (lib "") (part "CC0603KRX7R9BB104"))
    )
    (comp (ref "C307")
      (value "100nF")
      (fields
        (field (name "BOM_Manufacturer Part") "CC0603KRX7R9BB104")
        (field (name "BOM_Supplier Part") "C14663")
      )
      (libsource (lib "") (part "CC0603KRX7R9BB104"))
    )
    (comp (ref "C310") (value "100n") (libsource (lib "") (part "CC0603JRX7R8BB104")))
    (comp (ref "C311") (value "100n") (libsource (lib "") (part "CC0603JRX7R8BB104")))
    (comp (ref "C312") (value "100n") (libsource (lib "") (part "CC0603JRX7R8BB104")))
    (comp (ref "C313") (value "100n") (libsource (lib "") (part "CC0603JRX7R8BB104")))
    (comp (ref "C314") (value "100n") (libsource (lib "") (part "CC0603JRX7R8BB104")))
    (comp (ref "C315") (value "100n") (libsource (lib "") (part "CC0603JRX7R8BB104")))
    (comp (ref "C316") (value "100n") (libsource (lib "") (part "CC0603JRX7R8BB104")))
    (comp (ref "C317") (value "100n") (libsource (lib "") (part "CC0603JRX7R8BB104")))
    (comp (ref "D300")
      (value "1N5819WS")
      (fields (field (name "BOM_Supplier Part") "C191023"))
      (libsource (lib "") (part "1N5819WS"))
    )
    (comp (ref "D301")
      (value "1N5819WS")
      (fields (field (name "BOM_Supplier Part") "C191023"))
      (libsource (lib "") (part "1N5819WS"))
    )
    (comp (ref "D302")
      (value "1N5819WS")
      (fields (field (name "BOM_Supplier Part") "C191023"))
      (libsource (lib "") (part "1N5819WS"))
    )
    (comp (ref "D303")
      (value "1N5819WS")
      (fields (field (name "BOM_Supplier Part") "C191023"))
      (libsource (lib "") (part "1N5819WS"))
    )
    (comp (ref "D304")
      (value "1N5819WS")
      (fields (field (name "BOM_Supplier Part") "C191023"))
      (libsource (lib "") (part "1N5819WS"))
    )
    (comp (ref "D305")
      (value "1N5819WS")
      (fields (field (name "BOM_Supplier Part") "C191023"))
      (libsource (lib "") (part "1N5819WS"))
    )
    (comp (ref "D306")
      (value "1N5819WS")
      (fields (field (name "BOM_Supplier Part") "C191023"))
      (libsource (lib "") (part "1N5819WS"))
    )
    (comp (ref "D307")
      (value "1N5819WS")
      (fields (field (name "BOM_Supplier Part") "C191023"))
      (libsource (lib "") (part "1N5819WS"))
    )
    (comp (ref "D310")
      (value "1N4148WS T4")
      (fields (field (name "BOM_Manufacturer Part") "1N4148WS") (field (name "BOM_Supplier Part") "C2128"))
      (libsource (lib "") (part "1N4148WS T4"))
    )
    (comp (ref "D311")
      (value "1N4148WS T4")
      (fields (field (name "BOM_Manufacturer Part") "1N4148WS") (field (name "BOM_Supplier Part") "C2128"))
      (libsource (lib "") (part "1N4148WS T4"))
    )
    (comp (ref "D312")
      (value "1N4148WS T4")
      (fields (field (name "BOM_Manufacturer Part") "1N4148WS") (field (name "BOM_Supplier Part") "C2128"))
      (libsource (lib "") (part "1N4148WS T4"))
    )
    (comp (ref "D313")
      (value "1N4148WS T4")
      (fields (field (name "BOM_Manufacturer Part") "1N4148WS") (field (name "BOM_Supplier Part") "C2128"))
      (libsource (lib "") (part "1N4148WS T4"))
    )
    (comp (ref "D314")
      (value "1N4148WS T4")
      (fields (field (name "BOM_Manufacturer Part") "1N4148WS") (field (name "BOM_Supplier Part") "C2128"))
      (libsource (lib "") (part "1N4148WS T4"))
    )
    (comp (ref "D315")
      (value "1N4148WS T4")
      (fields (field (name "BOM_Manufacturer Part") "1N4148WS") (field (name "BOM_Supplier Part") "C2128"))
      (libsource (lib "") (part "1N4148WS T4"))
    )
    (comp (ref "D316")
      (value "1N4148WS T4")
      (fields (field (name "BOM_Manufacturer Part") "1N4148WS") (field (name "BOM_Supplier Part") "C2128"))
      (libsource (lib "") (part "1N4148WS T4"))
    )
    (comp (ref "D317")
      (value "1N4148WS T4")
      (fields (field (name "BOM_Manufacturer Part") "1N4148WS") (field (name "BOM_Supplier Part") "C2128"))
      (libsource (lib "") (part "1N4148WS T4"))
    )
    (comp (ref "D320")
      (value "ZMM5V6")
      (fields (field (name "BOM_Supplier Part") "C8062"))
      (libsource (lib "") (part "ZMM5V6"))
    )
    (comp (ref "D321")
      (value "ZMM5V6")
      (fields (field (name "BOM_Supplier Part") "C8062"))
      (libsource (lib "") (part "ZMM5V6"))
    )
    (comp (ref "D322")
      (value "ZMM5V6")
      (fields (field (name "BOM_Supplier Part") "C8062"))
      (libsource (lib "") (part "ZMM5V6"))
    )
    (comp (ref "D323")
      (value "ZMM5V6")
      (fields (field (name "BOM_Supplier Part") "C8062"))
      (libsource (lib "") (part "ZMM5V6"))
    )
    (comp (ref "D324")
      (value "ZMM5V6")
      (fields (field (name "BOM_Supplier Part") "C8062"))
      (libsource (lib "") (part "ZMM5V6"))
    )
    (comp (ref "D325")
      (value "ZMM5V6")
      (fields (field (name "BOM_Supplier Part") "C8062"))
      (libsource (lib "") (part "ZMM5V6"))
    )
    (comp (ref "D326")
      (value "ZMM5V6")
      (fields (field (name "BOM_Supplier Part") "C8062"))
      (libsource (lib "") (part "ZMM5V6"))
    )
    (comp (ref "D327")
      (value "ZMM5V6")
      (fields (field (name "BOM_Supplier Part") "C8062"))
      (libsource (lib "") (part "ZMM5V6"))
    )
    (comp (ref "D330")
      (value "ZMM5V6")
      (fields (field (name "BOM_Supplier Part") "C8062"))
      (libsource (lib "") (part "ZMM5V6"))
    )
    (comp (ref "D331")
      (value "ZMM5V6")
      (fields (field (name "BOM_Supplier Part") "C8062"))
      (libsource (lib "") (part "ZMM5V6"))
    )
    (comp (ref "D332")
      (value "ZMM5V6")
      (fields (field (name "BOM_Supplier Part") "C8062"))
      (libsource (lib "") (part "ZMM5V6"))
    )
    (comp (ref "D333")
      (value "ZMM5V6")
      (fields (field (name "BOM_Supplier Part") "C8062"))
      (libsource (lib "") (part "ZMM5V6"))
    )
    (comp (ref "D334")
      (value "ZMM5V6")
      (fields (field (name "BOM_Supplier Part") "C8062"))
      (libsource (lib "") (part "ZMM5V6"))
    )
    (comp (ref "D335")
      (value "ZMM5V6")
      (fields (field (name "BOM_Supplier Part") "C8062"))
      (libsource (lib "") (part "ZMM5V6"))
    )
    (comp (ref "D336")
      (value "ZMM5V6")
      (fields (field (name "BOM_Supplier Part") "C8062"))
      (libsource (lib "") (part "ZMM5V6"))
    )
    (comp (ref "D337")
      (value "ZMM5V6")
      (fields (field (name "BOM_Supplier Part") "C8062"))
      (libsource (lib "") (part "ZMM5V6"))
    )
    (comp (ref "D340")
      (value "1N4148WS T4")
      (fields (field (name "BOM_Manufacturer Part") "1N4148WS") (field (name "BOM_Supplier Part") "C2128"))
      (libsource (lib "") (part "1N4148WS T4"))
    )
    (comp (ref "D341")
      (value "1N4148WS T4")
      (fields (field (name "BOM_Manufacturer Part") "1N4148WS") (field (name "BOM_Supplier Part") "C2128"))
      (libsource (lib "") (part "1N4148WS T4"))
    )
    (comp (ref "D342")
      (value "1N4148WS T4")
      (fields (field (name "BOM_Manufacturer Part") "1N4148WS") (field (name "BOM_Supplier Part") "C2128"))
      (libsource (lib "") (part "1N4148WS T4"))
    )
    (comp (ref "D343")
      (value "1N4148WS T4")
      (fields (field (name "BOM_Manufacturer Part") "1N4148WS") (field (name "BOM_Supplier Part") "C2128"))
      (libsource (lib "") (part "1N4148WS T4"))
    )
    (comp (ref "D344")
      (value "1N4148WS T4")
      (fields (field (name "BOM_Manufacturer Part") "1N4148WS") (field (name "BOM_Supplier Part") "C2128"))
      (libsource (lib "") (part "1N4148WS T4"))
    )
    (comp (ref "D345")
      (value "1N4148WS T4")
      (fields (field (name "BOM_Manufacturer Part") "1N4148WS") (field (name "BOM_Supplier Part") "C2128"))
      (libsource (lib "") (part "1N4148WS T4"))
    )
    (comp (ref "D346")
      (value "1N4148WS T4")
      (fields (field (name "BOM_Manufacturer Part") "1N4148WS") (field (name "BOM_Supplier Part") "C2128"))
      (libsource (lib "") (part "1N4148WS T4"))
    )
    (comp (ref "D347")
      (value "1N4148WS T4")
      (fields (field (name "BOM_Manufacturer Part") "1N4148WS") (field (name "BOM_Supplier Part") "C2128"))
      (libsource (lib "") (part "1N4148WS T4"))
    )
    (comp (ref "D350")
      (value "1N4148WS T4")
      (fields (field (name "BOM_Manufacturer Part") "1N4148WS") (field (name "BOM_Supplier Part") "C2128"))
      (libsource (lib "") (part "1N4148WS T4_1"))
    )
    (comp (ref "D351")
      (value "1N4148WS T4")
      (fields (field (name "BOM_Manufacturer Part") "1N4148WS") (field (name "BOM_Supplier Part") "C2128"))
      (libsource (lib "") (part "1N4148WS T4_1"))
    )
    (comp (ref "D352")
      (value "1N4148WS T4")
      (fields (field (name "BOM_Manufacturer Part") "1N4148WS") (field (name "BOM_Supplier Part") "C2128"))
      (libsource (lib "") (part "1N4148WS T4_1"))
    )
    (comp (ref "D353")
      (value "1N4148WS T4")
      (fields (field (name "BOM_Manufacturer Part") "1N4148WS") (field (name "BOM_Supplier Part") "C2128"))
      (libsource (lib "") (part "1N4148WS T4_1"))
    )
    (comp (ref "D354")
      (value "1N4148WS T4")
      (fields (field (name "BOM_Manufacturer Part") "1N4148WS") (field (name "BOM_Supplier Part") "C2128"))
      (libsource (lib "") (part "1N4148WS T4_1"))
    )
    (comp (ref "D355")
      (value "1N4148WS T4")
      (fields (field (name "BOM_Manufacturer Part") "1N4148WS") (field (name "BOM_Supplier Part") "C2128"))
      (libsource (lib "") (part "1N4148WS T4_1"))
    )
    (comp (ref "D356")
      (value "1N4148WS T4")
      (fields (field (name "BOM_Manufacturer Part") "1N4148WS") (field (name "BOM_Supplier Part") "C2128"))
      (libsource (lib "") (part "1N4148WS T4_1"))
    )
    (comp (ref "D357")
      (value "1N4148WS T4")
      (fields (field (name "BOM_Manufacturer Part") "1N4148WS") (field (name "BOM_Supplier Part") "C2128"))
      (libsource (lib "") (part "1N4148WS T4_1"))
    )
    (comp (ref "D360")
      (value "1N4148WS T4")
      (fields (field (name "BOM_Manufacturer Part") "1N4148WS") (field (name "BOM_Supplier Part") "C2128"))
      (libsource (lib "") (part "1N4148WS T4_1"))
    )
    (comp (ref "D361")
      (value "1N4148WS T4")
      (fields (field (name "BOM_Manufacturer Part") "1N4148WS") (field (name "BOM_Supplier Part") "C2128"))
      (libsource (lib "") (part "1N4148WS T4_1"))
    )
    (comp (ref "D362")
      (value "1N4148WS T4")
      (fields (field (name "BOM_Manufacturer Part") "1N4148WS") (field (name "BOM_Supplier Part") "C2128"))
      (libsource (lib "") (part "1N4148WS T4_1"))
    )
    (comp (ref "D363")
      (value "1N4148WS T4")
      (fields (field (name "BOM_Manufacturer Part") "1N4148WS") (field (name "BOM_Supplier Part") "C2128"))
      (libsource (lib "") (part "1N4148WS T4_1"))
    )
    (comp (ref "D364")
      (value "1N4148WS T4")
      (fields (field (name "BOM_Manufacturer Part") "1N4148WS") (field (name "BOM_Supplier Part") "C2128"))
      (libsource (lib "") (part "1N4148WS T4_1"))
    )
    (comp (ref "D365")
      (value "1N4148WS T4")
      (fields (field (name "BOM_Manufacturer Part") "1N4148WS") (field (name "BOM_Supplier Part") "C2128"))
      (libsource (lib "") (part "1N4148WS T4_1"))
    )
    (comp (ref "D366")
      (value "1N4148WS T4")
      (fields (field (name "BOM_Manufacturer Part") "1N4148WS") (field (name "BOM_Supplier Part") "C2128"))
      (libsource (lib "") (part "1N4148WS T4_1"))
    )
    (comp (ref "D367")
      (value "1N4148WS T4")
      (fields (field (name "BOM_Manufacturer Part") "1N4148WS") (field (name "BOM_Supplier Part") "C2128"))
      (libsource (lib "") (part "1N4148WS T4_1"))
    )
    (comp (ref "Q300")
      (value "LBSS84LT1G")
      (fields (field (name "BOM_Supplier Part") "C8492"))
      (libsource (lib "") (part "LBSS84LT1G_1"))
    )
    (comp (ref "Q301")
      (value "LBSS84LT1G")
      (fields (field (name "BOM_Supplier Part") "C8492"))
      (libsource (lib "") (part "LBSS84LT1G_1"))
    )
    (comp (ref "Q302")
      (value "LBSS84LT1G")
      (fields (field (name "BOM_Supplier Part") "C8492"))
      (libsource (lib "") (part "LBSS84LT1G_1"))
    )
    (comp (ref "Q303")
      (value "LBSS84LT1G")
      (fields (field (name "BOM_Supplier Part") "C8492"))
      (libsource (lib "") (part "LBSS84LT1G_1"))
    )
    (comp (ref "Q304")
      (value "LBSS84LT1G")
      (fields (field (name "BOM_Supplier Part") "C8492"))
      (libsource (lib "") (part "LBSS84LT1G_1"))
    )
    (comp (ref "Q305")
      (value "LBSS84LT1G")
      (fields (field (name "BOM_Supplier Part") "C8492"))
      (libsource (lib "") (part "LBSS84LT1G_1"))
    )
    (comp (ref "Q306")
      (value "LBSS84LT1G")
      (fields (field (name "BOM_Supplier Part") "C8492"))
      (libsource (lib "") (part "LBSS84LT1G_1"))
    )
    (comp (ref "Q307")
      (value "LBSS84LT1G")
      (fields (field (name "BOM_Supplier Part") "C8492"))
      (libsource (lib "") (part "LBSS84LT1G_1"))
    )
    (comp (ref "Q310")
      (value "LBSS84LT1G")
      (fields (field (name "BOM_Supplier Part") "C8492"))
      (libsource (lib "") (part "LBSS84LT1G"))
    )
    (comp (ref "Q311")
      (value "LBSS84LT1G")
      (fields (field (name "BOM_Supplier Part") "C8492"))
      (libsource (lib "") (part "LBSS84LT1G"))
    )
    (comp (ref "Q312")
      (value "LBSS84LT1G")
      (fields (field (name "BOM_Supplier Part") "C8492"))
      (libsource (lib "") (part "LBSS84LT1G"))
    )
    (comp (ref "Q313")
      (value "LBSS84LT1G")
      (fields (field (name "BOM_Supplier Part") "C8492"))
      (libsource (lib "") (part "LBSS84LT1G"))
    )
    (comp (ref "Q314")
      (value "LBSS84LT1G")
      (fields (field (name "BOM_Supplier Part") "C8492"))
      (libsource (lib "") (part "LBSS84LT1G"))
    )
    (comp (ref "Q315")
      (value "LBSS84LT1G")
      (fields (field (name "BOM_Supplier Part") "C8492"))
      (libsource (lib "") (part "LBSS84LT1G"))
    )
    (comp (ref "Q316")
      (value "LBSS84LT1G")
      (fields (field (name "BOM_Supplier Part") "C8492"))
      (libsource (lib "") (part "LBSS84LT1G"))
    )
    (comp (ref "Q317")
      (value "LBSS84LT1G")
      (fields (field (name "BOM_Supplier Part") "C8492"))
      (libsource (lib "") (part "LBSS84LT1G"))
    )
    (comp (ref "R110")
      (value "10kΩ")
      (fields
        (field (name "BOM_Manufacturer Part") "0603WAF1002T5E")
        (field (name "BOM_Supplier Part") "C25804")
      )
      (libsource (lib "") (part "0603WAF1002T5E"))
    )
    (comp (ref "R300")
      (value "100kΩ")
      (fields
        (field (name "BOM_Manufacturer Part") "0603WAF1003T5E")
        (field (name "BOM_Supplier Part") "C25803")
      )
      (libsource (lib "") (part "0603WAF1003T5E"))
    )
    (comp (ref "R301")
      (value "100kΩ")
      (fields
        (field (name "BOM_Manufacturer Part") "0603WAF1003T5E")
        (field (name "BOM_Supplier Part") "C25803")
      )
      (libsource (lib "") (part "0603WAF1003T5E"))
    )
    (comp (ref "R302")
      (value "100kΩ")
      (fields
        (field (name "BOM_Manufacturer Part") "0603WAF1003T5E")
        (field (name "BOM_Supplier Part") "C25803")
      )
      (libsource (lib "") (part "0603WAF1003T5E"))
    )
    (comp (ref "R303")
      (value "100kΩ")
      (fields
        (field (name "BOM_Manufacturer Part") "0603WAF1003T5E")
        (field (name "BOM_Supplier Part") "C25803")
      )
      (libsource (lib "") (part "0603WAF1003T5E"))
    )
    (comp (ref "R304")
      (value "100kΩ")
      (fields
        (field (name "BOM_Manufacturer Part") "0603WAF1003T5E")
        (field (name "BOM_Supplier Part") "C25803")
      )
      (libsource (lib "") (part "0603WAF1003T5E"))
    )
    (comp (ref "R305")
      (value "100kΩ")
      (fields
        (field (name "BOM_Manufacturer Part") "0603WAF1003T5E")
        (field (name "BOM_Supplier Part") "C25803")
      )
      (libsource (lib "") (part "0603WAF1003T5E"))
    )
    (comp (ref "R306")
      (value "100kΩ")
      (fields
        (field (name "BOM_Manufacturer Part") "0603WAF1003T5E")
        (field (name "BOM_Supplier Part") "C25803")
      )
      (libsource (lib "") (part "0603WAF1003T5E"))
    )
    (comp (ref "R307")
      (value "100kΩ")
      (fields
        (field (name "BOM_Manufacturer Part") "0603WAF1003T5E")
        (field (name "BOM_Supplier Part") "C25803")
      )
      (libsource (lib "") (part "0603WAF1003T5E"))
    )
    (comp (ref "R310")
      (value "1kΩ")
      (fields
        (field (name "BOM_Manufacturer Part") "0603WAF1001T5E")
        (field (name "BOM_Supplier Part") "C21190")
      )
      (libsource (lib "") (part "0603WAF1001T5E"))
    )
    (comp (ref "R311")
      (value "1kΩ")
      (fields
        (field (name "BOM_Manufacturer Part") "0603WAF1001T5E")
        (field (name "BOM_Supplier Part") "C21190")
      )
      (libsource (lib "") (part "0603WAF1001T5E"))
    )
    (comp (ref "R312")
      (value "1kΩ")
      (fields
        (field (name "BOM_Manufacturer Part") "0603WAF1001T5E")
        (field (name "BOM_Supplier Part") "C21190")
      )
      (libsource (lib "") (part "0603WAF1001T5E"))
    )
    (comp (ref "R313")
      (value "1kΩ")
      (fields
        (field (name "BOM_Manufacturer Part") "0603WAF1001T5E")
        (field (name "BOM_Supplier Part") "C21190")
      )
      (libsource (lib "") (part "0603WAF1001T5E"))
    )
    (comp (ref "R314")
      (value "1kΩ")
      (fields
        (field (name "BOM_Manufacturer Part") "0603WAF1001T5E")
        (field (name "BOM_Supplier Part") "C21190")
      )
      (libsource (lib "") (part "0603WAF1001T5E"))
    )
    (comp (ref "R315")
      (value "1kΩ")
      (fields
        (field (name "BOM_Manufacturer Part") "0603WAF1001T5E")
        (field (name "BOM_Supplier Part") "C21190")
      )
      (libsource (lib "") (part "0603WAF1001T5E"))
    )
    (comp (ref "R316")
      (value "1kΩ")
      (fields
        (field (name "BOM_Manufacturer Part") "0603WAF1001T5E")
        (field (name "BOM_Supplier Part") "C21190")
      )
      (libsource (lib "") (part "0603WAF1001T5E"))
    )
    (comp (ref "R317")
      (value "1kΩ")
      (fields
        (field (name "BOM_Manufacturer Part") "0603WAF1001T5E")
        (field (name "BOM_Supplier Part") "C21190")
      )
      (libsource (lib "") (part "0603WAF1001T5E"))
    )
    (comp (ref "R320")
      (value "220kΩ")
      (fields
        (field (name "BOM_Manufacturer Part") "0805W8F2203T5E")
        (field (name "BOM_Supplier Part") "C17556")
      )
      (libsource (lib "") (part "0805W8F2203T5E_1"))
    )
    (comp (ref "R321")
      (value "220kΩ")
      (fields
        (field (name "BOM_Manufacturer Part") "0805W8F2203T5E")
        (field (name "BOM_Supplier Part") "C17556")
      )
      (libsource (lib "") (part "0805W8F2203T5E_1"))
    )
    (comp (ref "R322")
      (value "220kΩ")
      (fields
        (field (name "BOM_Manufacturer Part") "0805W8F2203T5E")
        (field (name "BOM_Supplier Part") "C17556")
      )
      (libsource (lib "") (part "0805W8F2203T5E_1"))
    )
    (comp (ref "R323")
      (value "220kΩ")
      (fields
        (field (name "BOM_Manufacturer Part") "0805W8F2203T5E")
        (field (name "BOM_Supplier Part") "C17556")
      )
      (libsource (lib "") (part "0805W8F2203T5E_1"))
    )
    (comp (ref "R324")
      (value "220kΩ")
      (fields
        (field (name "BOM_Manufacturer Part") "0805W8F2203T5E")
        (field (name "BOM_Supplier Part") "C17556")
      )
      (libsource (lib "") (part "0805W8F2203T5E_1"))
    )
    (comp (ref "R325")
      (value "220kΩ")
      (fields
        (field (name "BOM_Manufacturer Part") "0805W8F2203T5E")
        (field (name "BOM_Supplier Part") "C17556")
      )
      (libsource (lib "") (part "0805W8F2203T5E_1"))
    )
    (comp (ref "R326")
      (value "220kΩ")
      (fields
        (field (name "BOM_Manufacturer Part") "0805W8F2203T5E")
        (field (name "BOM_Supplier Part") "C17556")
      )
      (libsource (lib "") (part "0805W8F2203T5E_1"))
    )
    (comp (ref "R327")
      (value "220kΩ")
      (fields
        (field (name "BOM_Manufacturer Part") "0805W8F2203T5E")
        (field (name "BOM_Supplier Part") "C17556")
      )
      (libsource (lib "") (part "0805W8F2203T5E_1"))
    )
    (comp (ref "R330")
      (value "220kΩ")
      (fields
        (field (name "BOM_Manufacturer Part") "0805W8F2203T5E")
        (field (name "BOM_Supplier Part") "C17556")
      )
      (libsource (lib "") (part "0805W8F2203T5E"))
    )
    (comp (ref "R331")
      (value "220kΩ")
      (fields
        (field (name "BOM_Manufacturer Part") "0805W8F2203T5E")
        (field (name "BOM_Supplier Part") "C17556")
      )
      (libsource (lib "") (part "0805W8F2203T5E"))
    )
    (comp (ref "R332")
      (value "220kΩ")
      (fields
        (field (name "BOM_Manufacturer Part") "0805W8F2203T5E")
        (field (name "BOM_Supplier Part") "C17556")
      )
      (libsource (lib "") (part "0805W8F2203T5E"))
    )
    (comp (ref "R333")
      (value "220kΩ")
      (fields
        (field (name "BOM_Manufacturer Part") "0805W8F2203T5E")
        (field (name "BOM_Supplier Part") "C17556")
      )
      (libsource (lib "") (part "0805W8F2203T5E"))
    )
    (comp (ref "R334")
      (value "220kΩ")
      (fields
        (field (name "BOM_Manufacturer Part") "0805W8F2203T5E")
        (field (name "BOM_Supplier Part") "C17556")
      )
      (libsource (lib "") (part "0805W8F2203T5E"))
    )
    (comp (ref "R335")
      (value "220kΩ")
      (fields
        (field (name "BOM_Manufacturer Part") "0805W8F2203T5E")
        (field (name "BOM_Supplier Part") "C17556")
      )
      (libsource (lib "") (part "0805W8F2203T5E"))
    )
    (comp (ref "R336")
      (value "220kΩ")
      (fields
        (field (name "BOM_Manufacturer Part") "0805W8F2203T5E")
        (field (name "BOM_Supplier Part") "C17556")
      )
      (libsource (lib "") (part "0805W8F2203T5E"))
    )
    (comp (ref "R337")
      (value "220kΩ")
      (fields
        (field (name "BOM_Manufacturer Part") "0805W8F2203T5E")
        (field (name "BOM_Supplier Part") "C17556")
      )
      (libsource (lib "") (part "0805W8F2203T5E"))
    )
    (comp (ref "R340")
      (value "220kΩ")
      (fields
        (field (name "BOM_Manufacturer Part") "0805W8F2203T5E")
        (field (name "BOM_Supplier Part") "C17556")
      )
      (libsource (lib "") (part "0805W8F2203T5E"))
    )
    (comp (ref "R341")
      (value "220kΩ")
      (fields
        (field (name "BOM_Manufacturer Part") "0805W8F2203T5E")
        (field (name "BOM_Supplier Part") "C17556")
      )
      (libsource (lib "") (part "0805W8F2203T5E"))
    )
    (comp (ref "R342")
      (value "220kΩ")
      (fields
        (field (name "BOM_Manufacturer Part") "0805W8F2203T5E")
        (field (name "BOM_Supplier Part") "C17556")
      )
      (libsource (lib "") (part "0805W8F2203T5E"))
    )
    (comp (ref "R343")
      (value "220kΩ")
      (fields
        (field (name "BOM_Manufacturer Part") "0805W8F2203T5E")
        (field (name "BOM_Supplier Part") "C17556")
      )
      (libsource (lib "") (part "0805W8F2203T5E"))
    )
    (comp (ref "R344")
      (value "220kΩ")
      (fields
        (field (name "BOM_Manufacturer Part") "0805W8F2203T5E")
        (field (name "BOM_Supplier Part") "C17556")
      )
      (libsource (lib "") (part "0805W8F2203T5E"))
    )
    (comp (ref "R345")
      (value "220kΩ")
      (fields
        (field (name "BOM_Manufacturer Part") "0805W8F2203T5E")
        (field (name "BOM_Supplier Part") "C17556")
      )
      (libsource (lib "") (part "0805W8F2203T5E"))
    )
    (comp (ref "R346")
      (value "220kΩ")
      (fields
        (field (name "BOM_Manufacturer Part") "0805W8F2203T5E")
        (field (name "BOM_Supplier Part") "C17556")
      )
      (libsource (lib "") (part "0805W8F2203T5E"))
    )
    (comp (ref "R347")
      (value "220kΩ")
      (fields
        (field (name "BOM_Manufacturer Part") "0805W8F2203T5E")
        (field (name "BOM_Supplier Part") "C17556")
      )
      (libsource (lib "") (part "0805W8F2203T5E"))
    )
    (comp (ref "R350")
      (value "220kΩ")
      (fields
        (field (name "BOM_Manufacturer Part") "0805W8F2203T5E")
        (field (name "BOM_Supplier Part") "C17556")
      )
      (libsource (lib "") (part "0805W8F2203T5E"))
    )
    (comp (ref "R351")
      (value "220kΩ")
      (fields
        (field (name "BOM_Manufacturer Part") "0805W8F2203T5E")
        (field (name "BOM_Supplier Part") "C17556")
      )
      (libsource (lib "") (part "0805W8F2203T5E"))
    )
    (comp (ref "R352")
      (value "220kΩ")
      (fields
        (field (name "BOM_Manufacturer Part") "0805W8F2203T5E")
        (field (name "BOM_Supplier Part") "C17556")
      )
      (libsource (lib "") (part "0805W8F2203T5E"))
    )
    (comp (ref "R353")
      (value "220kΩ")
      (fields
        (field (name "BOM_Manufacturer Part") "0805W8F2203T5E")
        (field (name "BOM_Supplier Part") "C17556")
      )
      (libsource (lib "") (part "0805W8F2203T5E"))
    )
    (comp (ref "R354")
      (value "220kΩ")
      (fields
        (field (name "BOM_Manufacturer Part") "0805W8F2203T5E")
        (field (name "BOM_Supplier Part") "C17556")
      )
      (libsource (lib "") (part "0805W8F2203T5E"))
    )
    (comp (ref "R355")
      (value "220kΩ")
      (fields
        (field (name "BOM_Manufacturer Part") "0805W8F2203T5E")
        (field (name "BOM_Supplier Part") "C17556")
      )
      (libsource (lib "") (part "0805W8F2203T5E"))
    )
    (comp (ref "R356")
      (value "220kΩ")
      (fields
        (field (name "BOM_Manufacturer Part") "0805W8F2203T5E")
        (field (name "BOM_Supplier Part") "C17556")
      )
      (libsource (lib "") (part "0805W8F2203T5E"))
    )
    (comp (ref "R357")
      (value "220kΩ")
      (fields
        (field (name "BOM_Manufacturer Part") "0805W8F2203T5E")
        (field (name "BOM_Supplier Part") "C17556")
      )
      (libsource (lib "") (part "0805W8F2203T5E"))
    )
    (comp (ref "R360")
      (value "220kΩ")
      (fields
        (field (name "BOM_Manufacturer Part") "0805W8F2203T5E")
        (field (name "BOM_Supplier Part") "C17556")
      )
      (libsource (lib "") (part "0805W8F2203T5E"))
    )
    (comp (ref "R361")
      (value "220kΩ")
      (fields
        (field (name "BOM_Manufacturer Part") "0805W8F2203T5E")
        (field (name "BOM_Supplier Part") "C17556")
      )
      (libsource (lib "") (part "0805W8F2203T5E"))
    )
    (comp (ref "R362")
      (value "220kΩ")
      (fields
        (field (name "BOM_Manufacturer Part") "0805W8F2203T5E")
        (field (name "BOM_Supplier Part") "C17556")
      )
      (libsource (lib "") (part "0805W8F2203T5E"))
    )
    (comp (ref "R363")
      (value "220kΩ")
      (fields
        (field (name "BOM_Manufacturer Part") "0805W8F2203T5E")
        (field (name "BOM_Supplier Part") "C17556")
      )
      (libsource (lib "") (part "0805W8F2203T5E"))
    )
    (comp (ref "R364")
      (value "220kΩ")
      (fields
        (field (name "BOM_Manufacturer Part") "0805W8F2203T5E")
        (field (name "BOM_Supplier Part") "C17556")
      )
      (libsource (lib "") (part "0805W8F2203T5E"))
    )
    (comp (ref "R365")
      (value "220kΩ")
      (fields
        (field (name "BOM_Manufacturer Part") "0805W8F2203T5E")
        (field (name "BOM_Supplier Part") "C17556")
      )
      (libsource (lib "") (part "0805W8F2203T5E"))
    )
    (comp (ref "R366")
      (value "220kΩ")
      (fields
        (field (name "BOM_Manufacturer Part") "0805W8F2203T5E")
        (field (name "BOM_Supplier Part") "C17556")
      )
      (libsource (lib "") (part "0805W8F2203T5E"))
    )
    (comp (ref "R367")
      (value "220kΩ")
      (fields
        (field (name "BOM_Manufacturer Part") "0805W8F2203T5E")
        (field (name "BOM_Supplier Part") "C17556")
      )
      (libsource (lib "") (part "0805W8F2203T5E"))
    )
    (comp (ref "R370")
      (value "220kΩ")
      (fields
        (field (name "BOM_Manufacturer Part") "0805W8F2203T5E")
        (field (name "BOM_Supplier Part") "C17556")
      )
      (libsource (lib "") (part "0805W8F2203T5E"))
    )
    (comp (ref "R371")
      (value "220kΩ")
      (fields
        (field (name "BOM_Manufacturer Part") "0805W8F2203T5E")
        (field (name "BOM_Supplier Part") "C17556")
      )
      (libsource (lib "") (part "0805W8F2203T5E"))
    )
    (comp (ref "R372")
      (value "220kΩ")
      (fields
        (field (name "BOM_Manufacturer Part") "0805W8F2203T5E")
        (field (name "BOM_Supplier Part") "C17556")
      )
      (libsource (lib "") (part "0805W8F2203T5E"))
    )
    (comp (ref "R373")
      (value "220kΩ")
      (fields
        (field (name "BOM_Manufacturer Part") "0805W8F2203T5E")
        (field (name "BOM_Supplier Part") "C17556")
      )
      (libsource (lib "") (part "0805W8F2203T5E"))
    )
    (comp (ref "R374")
      (value "220kΩ")
      (fields
        (field (name "BOM_Manufacturer Part") "0805W8F2203T5E")
        (field (name "BOM_Supplier Part") "C17556")
      )
      (libsource (lib "") (part "0805W8F2203T5E"))
    )
    (comp (ref "R375")
      (value "220kΩ")
      (fields
        (field (name "BOM_Manufacturer Part") "0805W8F2203T5E")
        (field (name "BOM_Supplier Part") "C17556")
      )
      (libsource (lib "") (part "0805W8F2203T5E"))
    )
    (comp (ref "R376")
      (value "220kΩ")
      (fields
        (field (name "BOM_Manufacturer Part") "0805W8F2203T5E")
        (field (name "BOM_Supplier Part") "C17556")
      )
      (libsource (lib "") (part "0805W8F2203T5E"))
    )
    (comp (ref "R377")
      (value "220kΩ")
      (fields
        (field (name "BOM_Manufacturer Part") "0805W8F2203T5E")
        (field (name "BOM_Supplier Part") "C17556")
      )
      (libsource (lib "") (part "0805W8F2203T5E"))
    )
    (comp (ref "R380")
      (value "2.2kΩ")
      (fields
        (field (name "BOM_Manufacturer Part") "0603WAF2201T5E")
        (field (name "BOM_Supplier Part") "C4190")
      )
      (libsource (lib "") (part "0603WAF2201T5E"))
    )
    (comp (ref "R381")
      (value "2.2kΩ")
      (fields
        (field (name "BOM_Manufacturer Part") "0603WAF2201T5E")
        (field (name "BOM_Supplier Part") "C4190")
      )
      (libsource (lib "") (part "0603WAF2201T5E"))
    )
    (comp (ref "R382")
      (value "2.2kΩ")
      (fields
        (field (name "BOM_Manufacturer Part") "0603WAF2201T5E")
        (field (name "BOM_Supplier Part") "C4190")
      )
      (libsource (lib "") (part "0603WAF2201T5E"))
    )
    (comp (ref "R383")
      (value "2.2kΩ")
      (fields
        (field (name "BOM_Manufacturer Part") "0603WAF2201T5E")
        (field (name "BOM_Supplier Part") "C4190")
      )
      (libsource (lib "") (part "0603WAF2201T5E"))
    )
    (comp (ref "R384")
      (value "2.2kΩ")
      (fields
        (field (name "BOM_Manufacturer Part") "0603WAF2201T5E")
        (field (name "BOM_Supplier Part") "C4190")
      )
      (libsource (lib "") (part "0603WAF2201T5E"))
    )
    (comp (ref "R385")
      (value "2.2kΩ")
      (fields
        (field (name "BOM_Manufacturer Part") "0603WAF2201T5E")
        (field (name "BOM_Supplier Part") "C4190")
      )
      (libsource (lib "") (part "0603WAF2201T5E"))
    )
    (comp (ref "R386")
      (value "2.2kΩ")
      (fields
        (field (name "BOM_Manufacturer Part") "0603WAF2201T5E")
        (field (name "BOM_Supplier Part") "C4190")
      )
      (libsource (lib "") (part "0603WAF2201T5E"))
    )
    (comp (ref "R387")
      (value "2.2kΩ")
      (fields
        (field (name "BOM_Manufacturer Part") "0603WAF2201T5E")
        (field (name "BOM_Supplier Part") "C4190")
      )
      (libsource (lib "") (part "0603WAF2201T5E"))
    )
    (comp (ref "U300")
      (value "EL817S1(C)(TU)-F")
      (fields (field (name "BOM_Supplier Part") "C106900"))
      (libsource (lib "") (part "EL817S1(C)(TU)-F"))
    )
    (comp (ref "U301")
      (value "EL817S1(C)(TU)-F")
      (fields (field (name "BOM_Supplier Part") "C106900"))
      (libsource (lib "") (part "EL817S1(C)(TU)-F"))
    )
    (comp (ref "U302")
      (value "EL817S1(C)(TU)-F")
      (fields (field (name "BOM_Supplier Part") "C106900"))
      (libsource (lib "") (part "EL817S1(C)(TU)-F"))
    )
    (comp (ref "U303")
      (value "EL817S1(C)(TU)-F")
      (fields (field (name "BOM_Supplier Part") "C106900"))
      (libsource (lib "") (part "EL817S1(C)(TU)-F"))
    )
    (comp (ref "U304")
      (value "EL817S1(C)(TU)-F")
      (fields (field (name "BOM_Supplier Part") "C106900"))
      (libsource (lib "") (part "EL817S1(C)(TU)-F"))
    )
    (comp (ref "U305")
      (value "EL817S1(C)(TU)-F")
      (fields (field (name "BOM_Supplier Part") "C106900"))
      (libsource (lib "") (part "EL817S1(C)(TU)-F"))
    )
    (comp (ref "U306")
      (value "EL817S1(C)(TU)-F")
      (fields (field (name "BOM_Supplier Part") "C106900"))
      (libsource (lib "") (part "EL817S1(C)(TU)-F"))
    )
    (comp (ref "U307")
      (value "EL817S1(C)(TU)-F")
      (fields (field (name "BOM_Supplier Part") "C106900"))
      (libsource (lib "") (part "EL817S1(C)(TU)-F"))
    )
    (comp (ref "U390")
      (value "74HCT4051D-Q100,11")
      (fields (field (name "BOM_Supplier Part") "C547698"))
      (libsource (lib "") (part "74HCT4051D-Q100,11"))
    )
    (comp (ref "AC-MAINS")
      (value "1824440000")
      (fields (field (name "BOM_Supplier Part") "281-2022-ND"))
      (libsource (lib "") (part "1824440000"))
    )
    (comp (ref "AC-OUT1")
      (value "1824440000")
      (fields (field (name "BOM_Supplier Part") "281-2022-ND"))
      (libsource (lib "") (part "1824440000_1"))
    )
    (comp (ref "AC-OUT2")
      (value "1824440000")
      (fields (field (name "BOM_Supplier Part") "281-2022-ND"))
      (libsource (lib "") (part "1824440000_1"))
    )
    (comp (ref "AC-OUT3")
      (value "1824440000")
      (fields (field (name "BOM_Supplier Part") "281-2022-ND"))
      (libsource (lib "") (part "1824440000_1"))
    )
    (comp (ref "AC-OUT4")
      (value "1824440000")
      (fields (field (name "BOM_Supplier Part") "281-2022-ND"))
      (libsource (lib "") (part "1824440000_1"))
    )
    (comp (ref "C91")
      (value "100nF")
      (fields
        (field (name "BOM_Manufacturer Part") "CC0603KRX7R9BB104")
        (field (name "BOM_Supplier Part") "C14663")
      )
      (libsource (lib "") (part "CC0603KRX7R9BB104"))
    )
    (comp (ref "D200")
      (value "1N4148WS T4")
      (fields (field (name "BOM_Manufacturer Part") "1N4148WS") (field (name "BOM_Supplier Part") "C2128"))
      (libsource (lib "") (part "1N4148WS T4"))
    )
    (comp (ref "D201")
      (value "1N4148WS T4")
      (fields (field (name "BOM_Manufacturer Part") "1N4148WS") (field (name "BOM_Supplier Part") "C2128"))
      (libsource (lib "") (part "1N4148WS T4"))
    )
    (comp (ref "D202")
      (value "1N4148WS T4")
      (fields (field (name "BOM_Manufacturer Part") "1N4148WS") (field (name "BOM_Supplier Part") "C2128"))
      (libsource (lib "") (part "1N4148WS T4"))
    )
    (comp (ref "D203")
      (value "1N4148WS T4")
      (fields (field (name "BOM_Manufacturer Part") "1N4148WS") (field (name "BOM_Supplier Part") "C2128"))
      (libsource (lib "") (part "1N4148WS T4"))
    )
    (comp (ref "D204")
      (value "1N4148WS T4")
      (fields (field (name "BOM_Manufacturer Part") "1N4148WS") (field (name "BOM_Supplier Part") "C2128"))
      (libsource (lib "") (part "1N4148WS T4"))
    )
    (comp (ref "D205")
      (value "1N4148WS T4")
      (fields (field (name "BOM_Manufacturer Part") "1N4148WS") (field (name "BOM_Supplier Part") "C2128"))
      (libsource (lib "") (part "1N4148WS T4"))
    )
    (comp (ref "D206")
      (value "1N4148WS T4")
      (fields (field (name "BOM_Manufacturer Part") "1N4148WS") (field (name "BOM_Supplier Part") "C2128"))
      (libsource (lib "") (part "1N4148WS T4"))
    )
    (comp (ref "D207")
      (value "1N4148WS T4")
      (fields (field (name "BOM_Manufacturer Part") "1N4148WS") (field (name "BOM_Supplier Part") "C2128"))
      (libsource (lib "") (part "1N4148WS T4"))
    )
    (comp (ref "F1") (value "Fuse-5x20mm") (libsource (lib "") (part "Fuse-5x20mm")))
    (comp (ref "Q200")
      (value "2V7002LT3G")
      (fields (field (name "BOM_Supplier Part") "C152521"))
      (libsource (lib "") (part "2V7002LT3G"))
    )
    (comp (ref "Q201")
      (value "2V7002LT3G")
      (fields (field (name "BOM_Supplier Part") "C152521"))
      (libsource (lib "") (part "2V7002LT3G"))
    )
    (comp (ref "Q202")
      (value "2V7002LT3G")
      (fields (field (name "BOM_Supplier Part") "C152521"))
      (libsource (lib "") (part "2V7002LT3G"))
    )
    (comp (ref "Q203")
      (value "2V7002LT3G")
      (fields (field (name "BOM_Supplier Part") "C152521"))
      (libsource (lib "") (part "2V7002LT3G"))
    )
    (comp (ref "Q204")
      (value "2V7002LT3G")
      (fields (field (name "BOM_Supplier Part") "C152521"))
      (libsource (lib "") (part "2V7002LT3G"))
    )
    (comp (ref "Q205")
      (value "2V7002LT3G")
      (fields (field (name "BOM_Supplier Part") "C152521"))
      (libsource (lib "") (part "2V7002LT3G"))
    )
    (comp (ref "Q206")
      (value "2V7002LT3G")
      (fields (field (name "BOM_Supplier Part") "C152521"))
      (libsource (lib "") (part "2V7002LT3G"))
    )
    (comp (ref "Q207")
      (value "2V7002LT3G")
      (fields (field (name "BOM_Supplier Part") "C152521"))
      (libsource (lib "") (part "2V7002LT3G"))
    )
    (comp (ref "Q210")
      (value "2V7002LT3G")
      (fields (field (name "BOM_Supplier Part") "C152521"))
      (libsource (lib "") (part "2V7002LT3G"))
    )
    (comp (ref "Q211")
      (value "2V7002LT3G")
      (fields (field (name "BOM_Supplier Part") "C152521"))
      (libsource (lib "") (part "2V7002LT3G"))
    )
    (comp (ref "Q212")
      (value "2V7002LT3G")
      (fields (field (name "BOM_Supplier Part") "C152521"))
      (libsource (lib "") (part "2V7002LT3G"))
    )
    (comp (ref "Q213")
      (value "2V7002LT3G")
      (fields (field (name "BOM_Supplier Part") "C152521"))
      (libsource (lib "") (part "2V7002LT3G"))
    )
    (comp (ref "Q214")
      (value "2V7002LT3G")
      (fields (field (name "BOM_Supplier Part") "C152521"))
      (libsource (lib "") (part "2V7002LT3G"))
    )
    (comp (ref "Q215")
      (value "2V7002LT3G")
      (fields (field (name "BOM_Supplier Part") "C152521"))
      (libsource (lib "") (part "2V7002LT3G"))
    )
    (comp (ref "Q216")
      (value "2V7002LT3G")
      (fields (field (name "BOM_Supplier Part") "C152521"))
      (libsource (lib "") (part "2V7002LT3G"))
    )
    (comp (ref "Q217")
      (value "2V7002LT3G")
      (fields (field (name "BOM_Supplier Part") "C152521"))
      (libsource (lib "") (part "2V7002LT3G"))
    )
    (comp (ref "R57")
      (value "VDR")
      (fields
        (field (name "BOM_Manufacturer Part") "VDR-10D391K")
        (field (name "BOM_Supplier Part") "C283937")
      )
      (libsource (lib "") (part "VDR-10D391K"))
    )
    (comp (ref "R200")
      (value "10k")
      (fields
        (field (name "BOM_Manufacturer Part") "0603WAF1001T5E")
        (field (name "BOM_Supplier Part") "C21190")
      )
      (libsource (lib "") (part "0603WAF1001T5E"))
    )
    (comp (ref "R201")
      (value "10k")
      (fields
        (field (name "BOM_Manufacturer Part") "0603WAF1001T5E")
        (field (name "BOM_Supplier Part") "C21190")
      )
      (libsource (lib "") (part "0603WAF1001T5E"))
    )
    (comp (ref "R202")
      (value "10k")
      (fields
        (field (name "BOM_Manufacturer Part") "0603WAF1001T5E")
        (field (name "BOM_Supplier Part") "C21190")
      )
      (libsource (lib "") (part "0603WAF1001T5E"))
    )
    (comp (ref "R203")
      (value "10k")
      (fields
        (field (name "BOM_Manufacturer Part") "0603WAF1001T5E")
        (field (name "BOM_Supplier Part") "C21190")
      )
      (libsource (lib "") (part "0603WAF1001T5E"))
    )
    (comp (ref "R204")
      (value "10k")
      (fields
        (field (name "BOM_Manufacturer Part") "0603WAF1001T5E")
        (field (name "BOM_Supplier Part") "C21190")
      )
      (libsource (lib "") (part "0603WAF1001T5E"))
    )
    (comp (ref "R205")
      (value "10k")
      (fields
        (field (name "BOM_Manufacturer Part") "0603WAF1001T5E")
        (field (name "BOM_Supplier Part") "C21190")
      )
      (libsource (lib "") (part "0603WAF1001T5E"))
    )
    (comp (ref "R206")
      (value "10k")
      (fields
        (field (name "BOM_Manufacturer Part") "0603WAF1001T5E")
        (field (name "BOM_Supplier Part") "C21190")
      )
      (libsource (lib "") (part "0603WAF1001T5E"))
    )
    (comp (ref "R207")
      (value "10k")
      (fields
        (field (name "BOM_Manufacturer Part") "0603WAF1001T5E")
        (field (name "BOM_Supplier Part") "C21190")
      )
      (libsource (lib "") (part "0603WAF1001T5E"))
    )
    (comp (ref "R208")
      (value "10k")
      (fields
        (field (name "BOM_Manufacturer Part") "0603WAF1001T5E")
        (field (name "BOM_Supplier Part") "C21190")
      )
      (libsource (lib "") (part "0603WAF1001T5E_2"))
    )
    (comp (ref "R210")
      (value "10k")
      (fields
        (field (name "BOM_Manufacturer Part") "0603WAF1001T5E")
        (field (name "BOM_Supplier Part") "C21190")
      )
      (libsource (lib "") (part "0603WAF1001T5E_2"))
    )
    (comp (ref "R211")
      (value "10k")
      (fields
        (field (name "BOM_Manufacturer Part") "0603WAF1001T5E")
        (field (name "BOM_Supplier Part") "C21190")
      )
      (libsource (lib "") (part "0603WAF1001T5E_2"))
    )
    (comp (ref "R212")
      (value "10k")
      (fields
        (field (name "BOM_Manufacturer Part") "0603WAF1001T5E")
        (field (name "BOM_Supplier Part") "C21190")
      )
      (libsource (lib "") (part "0603WAF1001T5E_2"))
    )
    (comp (ref "R213")
      (value "10k")
      (fields
        (field (name "BOM_Manufacturer Part") "0603WAF1001T5E")
        (field (name "BOM_Supplier Part") "C21190")
      )
      (libsource (lib "") (part "0603WAF1001T5E_2"))
    )
    (comp (ref "R214")
      (value "10k")
      (fields
        (field (name "BOM_Manufacturer Part") "0603WAF1001T5E")
        (field (name "BOM_Supplier Part") "C21190")
      )
      (libsource (lib "") (part "0603WAF1001T5E_2"))
    )
    (comp (ref "R215")
      (value "10k")
      (fields
        (field (name "BOM_Manufacturer Part") "0603WAF1001T5E")
        (field (name "BOM_Supplier Part") "C21190")
      )
      (libsource (lib "") (part "0603WAF1001T5E_2"))
    )
    (comp (ref "R216")
      (value "10k")
      (fields
        (field (name "BOM_Manufacturer Part") "0603WAF1001T5E")
        (field (name "BOM_Supplier Part") "C21190")
      )
      (libsource (lib "") (part "0603WAF1001T5E_2"))
    )
    (comp (ref "R217")
      (value "10k")
      (fields
        (field (name "BOM_Manufacturer Part") "0603WAF1001T5E")
        (field (name "BOM_Supplier Part") "C21190")
      )
      (libsource (lib "") (part "0603WAF1001T5E_2"))
    )
    (comp (ref "R220")
      (value "10k")
      (fields
        (field (name "BOM_Manufacturer Part") "0603WAF1001T5E")
        (field (name "BOM_Supplier Part") "C21190")
      )
      (libsource (lib "") (part "0603WAF1001T5E_1"))
    )
    (comp (ref "R221")
      (value "10k")
      (fields
        (field (name "BOM_Manufacturer Part") "0603WAF1001T5E")
        (field (name "BOM_Supplier Part") "C21190")
      )
      (libsource (lib "") (part "0603WAF1001T5E_1"))
    )
    (comp (ref "R222")
      (value "10k")
      (fields
        (field (name "BOM_Manufacturer Part") "0603WAF1001T5E")
        (field (name "BOM_Supplier Part") "C21190")
      )
      (libsource (lib "") (part "0603WAF1001T5E_1"))
    )
    (comp (ref "R223")
      (value "10k")
      (fields
        (field (name "BOM_Manufacturer Part") "0603WAF1001T5E")
        (field (name "BOM_Supplier Part") "C21190")
      )
      (libsource (lib "") (part "0603WAF1001T5E_1"))
    )
    (comp (ref "R224")
      (value "10k")
      (fields
        (field (name "BOM_Manufacturer Part") "0603WAF1001T5E")
        (field (name "BOM_Supplier Part") "C21190")
      )
      (libsource (lib "") (part "0603WAF1001T5E_1"))
    )
    (comp (ref "R225")
      (value "10k")
      (fields
        (field (name "BOM_Manufacturer Part") "0603WAF1001T5E")
        (field (name "BOM_Supplier Part") "C21190")
      )
      (libsource (lib "") (part "0603WAF1001T5E_1"))
    )
    (comp (ref "R226")
      (value "10k")
      (fields
        (field (name "BOM_Manufacturer Part") "0603WAF1001T5E")
        (field (name "BOM_Supplier Part") "C21190")
      )
      (libsource (lib "") (part "0603WAF1001T5E_1"))
    )
    (comp (ref "R227")
      (value "10k")
      (fields
        (field (name "BOM_Manufacturer Part") "0603WAF1001T5E")
        (field (name "BOM_Supplier Part") "C21190")
      )
      (libsource (lib "") (part "0603WAF1001T5E_1"))
    )
    (comp (ref "REL0")
      (value "FC-D1608HOK-600H")
      (fields (field (name "BOM_Supplier Part") "C84269"))
      (libsource (lib "") (part "FC-D1608HOK-600H"))
    )
    (comp (ref "REL1")
      (value "FC-D1608HOK-600H")
      (fields (field (name "BOM_Supplier Part") "C84269"))
      (libsource (lib "") (part "FC-D1608HOK-600H"))
    )
    (comp (ref "REL2")
      (value "FC-D1608HOK-600H")
      (fields (field (name "BOM_Supplier Part") "C84269"))
      (libsource (lib "") (part "FC-D1608HOK-600H"))
    )
    (comp (ref "REL3")
      (value "FC-D1608HOK-600H")
      (fields (field (name "BOM_Supplier Part") "C84269"))
      (libsource (lib "") (part "FC-D1608HOK-600H"))
    )
    (comp (ref "REL4")
      (value "FC-D1608HOK-600H")
      (fields (field (name "BOM_Supplier Part") "C84269"))
      (libsource (lib "") (part "FC-D1608HOK-600H"))
    )
    (comp (ref "REL5")
      (value "FC-D1608HOK-600H")
      (fields (field (name "BOM_Supplier Part") "C84269"))
      (libsource (lib "") (part "FC-D1608HOK-600H"))
    )
    (comp (ref "REL6")
      (value "FC-D1608HOK-600H")
      (fields (field (name "BOM_Supplier Part") "C84269"))
      (libsource (lib "") (part "FC-D1608HOK-600H"))
    )
    (comp (ref "REL7")
      (value "FC-D1608HOK-600H")
      (fields (field (name "BOM_Supplier Part") "C84269"))
      (libsource (lib "") (part "FC-D1608HOK-600H"))
    )
    (comp (ref "REL200")
      (value "HF115F/012-2ZS4AF")
      (fields (field (name "BOM_Supplier Part") "C882372"))
      (libsource (lib "") (part "HF115F/012-2ZS4AF"))
    )
    (comp (ref "REL201")
      (value "HF41F/5-ZS")
      (fields (field (name "BOM_Supplier Part") "C91698"))
      (libsource (lib "") (part "HF41F/5-ZS"))
    )
    (comp (ref "REL202")
      (value "HF41F/5-ZS")
      (fields (field (name "BOM_Supplier Part") "C91698"))
      (libsource (lib "") (part "HF41F/5-ZS"))
    )
    (comp (ref "REL203")
      (value "HF41F/5-ZS")
      (fields (field (name "BOM_Supplier Part") "C91698"))
      (libsource (lib "") (part "HF41F/5-ZS"))
    )
    (comp (ref "REL204")
      (value "HF41F/5-ZS")
      (fields (field (name "BOM_Supplier Part") "C91698"))
      (libsource (lib "") (part "HF41F/5-ZS"))
    )
    (comp (ref "REL205")
      (value "HF41F/5-ZS")
      (fields (field (name "BOM_Supplier Part") "C91698"))
      (libsource (lib "") (part "HF41F/5-ZS"))
    )
    (comp (ref "REL206")
      (value "HF41F/5-ZS")
      (fields (field (name "BOM_Supplier Part") "C91698"))
      (libsource (lib "") (part "HF41F/5-ZS"))
    )
    (comp (ref "REL207")
      (value "HF41F/5-ZS")
      (fields (field (name "BOM_Supplier Part") "C91698"))
      (libsource (lib "") (part "HF41F/5-ZS"))
    )
    (comp (ref "TP1") (value ".") (libsource (lib "") (part "TESTPOIN-SMD-Ø1.2MM_1")))
    (comp (ref "TP2") (value ".") (libsource (lib "") (part "TESTPOIN-SMD-Ø1.2MM_2")))
    (comp (ref "TP3") (value ".") (libsource (lib "") (part "TESTPOIN-SMD-Ø1.2MM")))
    (comp (ref "TP4") (value ".") (libsource (lib "") (part "TESTPOIN-SMD-Ø1.2MM_2")))
    (comp (ref "TP5") (value ".") (libsource (lib "") (part "TESTPOIN-SMD-Ø1.2MM")))
    (comp (ref "TP6") (value ".") (libsource (lib "") (part "TESTPOIN-SMD-Ø1.2MM")))
    (comp (ref "TP7") (value ".") (libsource (lib "") (part "TESTPOIN-SMD-Ø1.2MM_1")))
    (comp (ref "TP8") (value ".") (libsource (lib "") (part "TESTPOIN-SMD-Ø1.2MM_1")))
    (comp (ref "TP9") (value ".") (libsource (lib "") (part "TESTPOIN-SMD-Ø1.2MM_1")))
    (comp (ref "TP10") (value ".") (libsource (lib "") (part "TESTPOIN-SMD-Ø1.2MM_1")))
    (comp (ref "TP11") (value ".") (libsource (lib "") (part "TESTPOIN-SMD-Ø1.2MM_1")))
    (comp (ref "TP12") (value ".") (libsource (lib "") (part "TESTPOIN-SMD-Ø1.2MM_1")))
    (comp (ref "TP13") (value ".") (libsource (lib "") (part "TESTPOIN-SMD-Ø1.2MM_1")))
    (comp (ref "TP14") (value ".") (libsource (lib "") (part "TESTPOIN-SMD-Ø1.2MM_2")))
    (comp (ref "TP15") (value ".") (libsource (lib "") (part "TESTPOIN-SMD-Ø1.2MM")))
    (comp (ref "TP16") (value ".") (libsource (lib "") (part "TESTPOIN-SMD-Ø1.2MM")))
    (comp (ref "TP17") (value ".") (libsource (lib "") (part "TESTPOIN-SMD-Ø1.2MM")))
    (comp (ref "TP18") (value ".") (libsource (lib "") (part "TESTPOIN-SMD-Ø1.2MM")))
    (comp (ref "TP19") (value ".") (libsource (lib "") (part "TESTPOIN-SMD-Ø1.2MM")))
    (comp (ref "TP20") (value ".") (libsource (lib "") (part "TESTPOIN-SMD-Ø1.2MM")))
    (comp (ref "U2")
      (value "HLK-5M05_C917669")
      (fields (field (name "BOM_Manufacturer Part") "HLK-5M05") (field (name "BOM_Supplier Part") "C917669"))
      (libsource (lib "") (part "HLK-5M05_C917669"))
    )
    (comp (ref "U290")
      (value "74HCT4051D-Q100,11")
      (fields (field (name "BOM_Supplier Part") "C547698"))
      (libsource (lib "") (part "74HCT4051D-Q100,11"))
    )
  )
  (nets
    (net (code "1") (name "+3V3") (class "Default")
      (node (ref "3V3") (pin "1") (pinfunction "1_1") (pintype "unspecified"))
      (node (ref "C100") (pin "2") (pinfunction "2_2") (pintype "unspecified"))
      (node (ref "C103") (pin "2") (pinfunction "2_2") (pintype "unspecified"))
      (node (ref "C106") (pin "2") (pinfunction "2_2") (pintype "unspecified"))
      (node (ref "C107") (pin "2") (pinfunction "2_2") (pintype "unspecified"))
      (node (ref "C90") (pin "2") (pinfunction "2_2") (pintype "unspecified"))
      (node (ref "C91") (pin "2") (pinfunction "2_2") (pintype "unspecified"))
      (node (ref "D1") (pin "1") (pinfunction "C_1") (pintype "unspecified"))
      (node (ref "D19") (pin "1") (pinfunction "C_1") (pintype "unspecified"))
      (node (ref "D2") (pin "1") (pinfunction "C_1") (pintype "unspecified"))
      (node (ref "D3") (pin "1") (pinfunction "C_1") (pintype "unspecified"))
      (node (ref "D4") (pin "1") (pinfunction "C_1") (pintype "unspecified"))
      (node (ref "D5") (pin "1") (pinfunction "C_1") (pintype "unspecified"))
      (node (ref "D6") (pin "1") (pinfunction "C_1") (pintype "unspecified"))
      (node (ref "D7") (pin "1") (pinfunction "C_1") (pintype "unspecified"))
      (node (ref "D8") (pin "1") (pinfunction "C_1") (pintype "unspecified"))
      (node (ref "GP1") (pin "36") (pinfunction "3V3_OUT_36") (pintype "unspecified"))
      (node (ref "PWR1") (pin "1") (pinfunction "1_1") (pintype "unspecified"))
      (node (ref "PWR2") (pin "1") (pinfunction "1_1") (pintype "unspecified"))
      (node (ref "PWR3") (pin "1") (pinfunction "1_1") (pintype "unspecified"))
      (node (ref "PWR4") (pin "1") (pinfunction "1_1") (pintype "unspecified"))
      (node (ref "PWR5") (pin "1") (pinfunction "1_1") (pintype "unspecified"))
      (node (ref "PWR6") (pin "1") (pinfunction "1_1") (pintype "unspecified"))
      (node (ref "PWR7") (pin "1") (pinfunction "1_1") (pintype "unspecified"))
      (node (ref "PWR8") (pin "1") (pinfunction "1_1") (pintype "unspecified"))
      (node (ref "Q300") (pin "2") (pinfunction "S_2") (pintype "unspecified"))
      (node (ref "Q301") (pin "2") (pinfunction "S_2") (pintype "unspecified"))
      (node (ref "Q302") (pin "2") (pinfunction "S_2") (pintype "unspecified"))
      (node (ref "Q303") (pin "2") (pinfunction "S_2") (pintype "unspecified"))
      (node (ref "Q304") (pin "2") (pinfunction "S_2") (pintype "unspecified"))
      (node (ref "Q305") (pin "2") (pinfunction "S_2") (pintype "unspecified"))
      (node (ref "Q306") (pin "2") (pinfunction "S_2") (pintype "unspecified"))
      (node (ref "Q307") (pin "2") (pinfunction "S_2") (pintype "unspecified"))
      (node (ref "QWIIC") (pin "2") (pinfunction "3.3V_2") (pintype "unspecified"))
      (node (ref "R10") (pin "2") (pinfunction "2_2") (pintype "input"))
      (node (ref "R20") (pin "2") (pinfunction "2_2") (pintype "input"))
      (node (ref "R21") (pin "2") (pinfunction "2_2") (pintype "input"))
      (node (ref "R22") (pin "2") (pinfunction "2_2") (pintype "input"))
      (node (ref "R23") (pin "2") (pinfunction "2_2") (pintype "input"))
      (node (ref "R24") (pin "2") (pinfunction "2_2") (pintype "input"))
      (node (ref "R25") (pin "2") (pinfunction "2_2") (pintype "input"))
      (node (ref "R26") (pin "2") (pinfunction "2_2") (pintype "input"))
      (node (ref "R27") (pin "2") (pinfunction "2_2") (pintype "input"))
      (node (ref "R28") (pin "2") (pinfunction "2_2") (pintype "input"))
      (node (ref "R30") (pin "2") (pinfunction "2_2") (pintype "input"))
      (node (ref "R300") (pin "1") (pinfunction "1_1") (pintype "input"))
      (node (ref "R301") (pin "1") (pinfunction "1_1") (pintype "input"))
      (node (ref "R302") (pin "1") (pinfunction "1_1") (pintype "input"))
      (node (ref "R303") (pin "1") (pinfunction "1_1") (pintype "input"))
      (node (ref "R304") (pin "1") (pinfunction "1_1") (pintype "input"))
      (node (ref "R305") (pin "1") (pinfunction "1_1") (pintype "input"))
      (node (ref "R306") (pin "1") (pinfunction "1_1") (pintype "input"))
      (node (ref "R307") (pin "1") (pinfunction "1_1") (pintype "input"))
      (node (ref "R31") (pin "2") (pinfunction "2_2") (pintype "input"))
      (node (ref "R32") (pin "2") (pinfunction "2_2") (pintype "input"))
      (node (ref "R33") (pin "2") (pinfunction "2_2") (pintype "input"))
      (node (ref "R34") (pin "2") (pinfunction "2_2") (pintype "input"))
      (node (ref "R35") (pin "2") (pinfunction "2_2") (pintype "input"))
      (node (ref "R36") (pin "2") (pinfunction "2_2") (pintype "input"))
      (node (ref "R37") (pin "2") (pinfunction "2_2") (pintype "input"))
      (node (ref "R42") (pin "2") (pinfunction "2_2") (pintype "input"))
      (node (ref "R9") (pin "2") (pinfunction "2_2") (pintype "input"))
      (node (ref "TEMP1") (pin "1") (pinfunction "1_1") (pintype "unspecified"))
      (node (ref "TEMP10") (pin "1") (pinfunction "1_1") (pintype "unspecified"))
      (node (ref "TEMP11") (pin "1") (pinfunction "1_1") (pintype "unspecified"))
      (node (ref "TEMP12") (pin "1") (pinfunction "1_1") (pintype "unspecified"))
      (node (ref "TEMP13") (pin "1") (pinfunction "1_1") (pintype "unspecified"))
      (node (ref "TEMP14") (pin "1") (pinfunction "1_1") (pintype "unspecified"))
      (node (ref "TEMP15") (pin "1") (pinfunction "1_1") (pintype "unspecified"))
      (node (ref "TEMP16") (pin "1") (pinfunction "1_1") (pintype "unspecified"))
      (node (ref "TEMP2") (pin "1") (pinfunction "1_1") (pintype "unspecified"))
      (node (ref "TEMP3") (pin "1") (pinfunction "1_1") (pintype "unspecified"))
      (node (ref "TEMP4") (pin "1") (pinfunction "1_1") (pintype "unspecified"))
      (node (ref "TEMP5") (pin "1") (pinfunction "1_1") (pintype "unspecified"))
      (node (ref "TEMP6") (pin "1") (pinfunction "1_1") (pintype "unspecified"))
      (node (ref "TEMP7") (pin "1") (pinfunction "1_1") (pintype "unspecified"))
      (node (ref "TEMP8") (pin "1") (pinfunction "1_1") (pintype "unspecified"))
      (node (ref "TEMP9") (pin "1") (pinfunction "1_1") (pintype "unspecified"))
      (node (ref "U1") (pin "3") (pinfunction "VCC_3") (pintype "unspecified"))
      (node (ref "U290") (pin "16") (pinfunction "VCC_16") (pintype "unspecified"))
      (node (ref "U3") (pin "16") (pinfunction "VCC_16") (pintype "unspecified"))
      (node (ref "U390") (pin "16") (pinfunction "VCC_16") (pintype "unspecified"))
      (node (ref "U6") (pin "16") (pinfunction "VCC_16") (pintype "unspecified"))
      (node (ref "U7") (pin "1") (pinfunction "VDD_1") (pintype "unspecified"))
    )
    (net (code "2") (name "+5V") (class "Default")
      (node (ref "C1") (pin "2") (pinfunction "2_2") (pintype "input"))
      (node (ref "D10") (pin "2") (pinfunction "K_2") (pintype "unspecified"))
      (node (ref "D200") (pin "1") (pinfunction "K_1") (pintype "unspecified"))
      (node (ref "D201") (pin "1") (pinfunction "K_1") (pintype "unspecified"))
      (node (ref "D202") (pin "1") (pinfunction "K_1") (pintype "unspecified"))
      (node (ref "D203") (pin "1") (pinfunction "K_1") (pintype "unspecified"))
      (node (ref "D204") (pin "1") (pinfunction "K_1") (pintype "unspecified"))
      (node (ref "D205") (pin "1") (pinfunction "K_1") (pintype "unspecified"))
      (node (ref "D206") (pin "1") (pinfunction "K_1") (pintype "unspecified"))
      (node (ref "D207") (pin "1") (pinfunction "K_1") (pintype "unspecified"))
      (node (ref "GP1") (pin "39") (pinfunction "VSYS_39") (pintype "unspecified"))
      (node (ref "GP1") (pin "40") (pinfunction "VBUS_40") (pintype "unspecified"))
      (node (ref "IO_1") (pin "2") (pinfunction "A_2") (pintype "input"))
      (node (ref "IO_2") (pin "2") (pinfunction "A_2") (pintype "input"))
      (node (ref "IO_3") (pin "2") (pinfunction "A_2") (pintype "input"))
      (node (ref "IO_4") (pin "2") (pinfunction "A_2") (pintype "input"))
      (node (ref "IO_5") (pin "2") (pinfunction "A_2") (pintype "input"))
      (node (ref "IO_6") (pin "2") (pinfunction "A_2") (pintype "input"))
      (node (ref "IO_7") (pin "2") (pinfunction "A_2") (pintype "input"))
      (node (ref "IO_8") (pin "2") (pinfunction "A_2") (pintype "input"))
      (node (ref "OPTO3") (pin "1") (pinfunction "A_1") (pintype "input"))
      (node (ref "OPTO4") (pin "1") (pinfunction "A_1") (pintype "input"))
      (node (ref "PWR1") (pin "3") (pinfunction "3_3") (pintype "unspecified"))
      (node (ref "PWR2") (pin "3") (pinfunction "3_3") (pintype "unspecified"))
      (node (ref "PWR3") (pin "3") (pinfunction "3_3") (pintype "unspecified"))
      (node (ref "PWR4") (pin "3") (pinfunction "3_3") (pintype "unspecified"))
      (node (ref "PWR5") (pin "3") (pinfunction "3_3") (pintype "unspecified"))
      (node (ref "PWR6") (pin "3") (pinfunction "3_3") (pintype "unspecified"))
      (node (ref "PWR7") (pin "3") (pinfunction "3_3") (pintype "unspecified"))
      (node (ref "PWR8") (pin "3") (pinfunction "3_3") (pintype "unspecified"))
      (node (ref "Q3") (pin "3") (pinfunction "C_3") (pintype "unspecified"))
      (node (ref "Q4") (pin "3") (pinfunction "C_3") (pintype "unspecified"))
      (node (ref "R40") (pin "2") (pinfunction "2_2") (pintype "input"))
      (node (ref "REL0") (pin "2") (pinfunction "A_2") (pintype "input"))
      (node (ref "REL1") (pin "2") (pinfunction "A_2") (pintype "input"))
      (node (ref "REL2") (pin "2") (pinfunction "A_2") (pintype "input"))
      (node (ref "REL200") (pin "2") (pinfunction "2_2") (pintype "input"))
      (node (ref "REL201") (pin "1") (pinfunction "COIL_1") (pintype "unspecified"))
      (node (ref "REL202") (pin "1") (pinfunction "COIL_1") (pintype "unspecified"))
      (node (ref "REL203") (pin "1") (pinfunction "COIL_1") (pintype "unspecified"))
      (node (ref "REL204") (pin "1") (pinfunction "COIL_1") (pintype "unspecified"))
      (node (ref "REL205") (pin "1") (pinfunction "COIL_1") (pintype "unspecified"))
      (node (ref "REL206") (pin "1") (pinfunction "COIL_1") (pintype "unspecified"))
      (node (ref "REL207") (pin "1") (pinfunction "COIL_1") (pintype "unspecified"))
      (node (ref "REL3") (pin "2") (pinfunction "A_2") (pintype "input"))
      (node (ref "REL4") (pin "2") (pinfunction "A_2") (pintype "input"))
      (node (ref "REL5") (pin "2") (pinfunction "A_2") (pintype "input"))
      (node (ref "REL6") (pin "2") (pinfunction "A_2") (pintype "input"))
      (node (ref "REL7") (pin "2") (pinfunction "A_2") (pintype "input"))
      (node (ref "SUPPLY") (pin "1") (pinfunction "1_1") (pintype "unspecified"))
      (node (ref "U11") (pin "4") (pinfunction "COL_4") (pintype "unspecified"))
      (node (ref "U2") (pin "4") (pinfunction "+VO_4") (pintype "unspecified"))
      (node (ref "U4") (pin "4") (pinfunction "COL_4") (pintype "unspecified"))
    )
    (net (code "3") (name "0V") (class "Default")
      (node (ref "3.3V") (pin "2") (pinfunction "K_2") (pintype "unspecified"))
      (node (ref "AC0") (pin "2") (pinfunction "C_2") (pintype "input"))
      (node (ref "AC1") (pin "2") (pinfunction "C_2") (pintype "input"))
      (node (ref "AC2") (pin "2") (pinfunction "C_2") (pintype "input"))
      (node (ref "AC3") (pin "2") (pinfunction "C_2") (pintype "input"))
      (node (ref "AC4") (pin "2") (pinfunction "C_2") (pintype "input"))
      (node (ref "AC5") (pin "2") (pinfunction "C_2") (pintype "input"))
      (node (ref "AC6") (pin "2") (pinfunction "C_2") (pintype "input"))
      (node (ref "AC7") (pin "2") (pinfunction "C_2") (pintype "input"))
      (node (ref "C1") (pin "1") (pinfunction "1_1") (pintype "input"))
      (node (ref "C100") (pin "1") (pinfunction "1_1") (pintype "unspecified"))
      (node (ref "C103") (pin "1") (pinfunction "1_1") (pintype "unspecified"))
      (node (ref "C106") (pin "1") (pinfunction "1_1") (pintype "unspecified"))
      (node (ref "C107") (pin "1") (pinfunction "1_1") (pintype "unspecified"))
      (node (ref "C300") (pin "1") (pinfunction "1_1") (pintype "unspecified"))
      (node (ref "C301") (pin "1") (pinfunction "1_1") (pintype "unspecified"))
      (node (ref "C302") (pin "1") (pinfunction "1_1") (pintype "unspecified"))
      (node (ref "C303") (pin "1") (pinfunction "1_1") (pintype "unspecified"))
      (node (ref "C304") (pin "1") (pinfunction "1_1") (pintype "unspecified"))
      (node (ref "C305") (pin "1") (pinfunction "1_1") (pintype "unspecified"))
      (node (ref "C306") (pin "1") (pinfunction "1_1") (pintype "unspecified"))
      (node (ref "C307") (pin "1") (pinfunction "1_1") (pintype "unspecified"))
      (node (ref "C6") (pin "1") (pinfunction "1_1") (pintype "unspecified"))
      (node (ref "C90") (pin "1") (pinfunction "1_1") (pintype "unspecified"))
      (node (ref "C91") (pin "1") (pinfunction "1_1") (pintype "unspecified"))
      (node (ref "D10") (pin "1") (pinfunction "A_1") (pintype "unspecified"))
      (node (ref "D11") (pin "2") (pinfunction "A_2") (pintype "unspecified"))
      (node (ref "D12") (pin "2") (pinfunction "A_2") (pintype "unspecified"))
      (node (ref "D13") (pin "2") (pinfunction "A_2") (pintype "unspecified"))
      (node (ref "D14") (pin "2") (pinfunction "A_2") (pintype "unspecified"))
      (node (ref "D15") (pin "2") (pinfunction "A_2") (pintype "unspecified"))
      (node (ref "D16") (pin "2") (pinfunction "A_2") (pintype "unspecified"))
      (node (ref "D17") (pin "2") (pinfunction "A_2") (pintype "unspecified"))
      (node (ref "D18") (pin "2") (pinfunction "A_2") (pintype "unspecified"))
      (node (ref "GND") (pin "1") (pinfunction "1_1") (pintype "unspecified"))
      (node (ref "GP1") (pin "13") (pinfunction "GND_13") (pintype "unspecified"))
      (node (ref "GP1") (pin "18") (pinfunction "GND_18") (pintype "unspecified"))
      (node (ref "GP1") (pin "23") (pinfunction "GND_23") (pintype "unspecified"))
      (node (ref "GP1") (pin "28") (pinfunction "GND_28") (pintype "unspecified"))
      (node (ref "GP1") (pin "3") (pinfunction "GND_3") (pintype "unspecified"))
      (node (ref "GP1") (pin "33") (pinfunction "GND_33") (pintype "unspecified"))
      (node (ref "GP1") (pin "38") (pinfunction "GND_38") (pintype "unspecified"))
      (node (ref "GP1") (pin "8") (pinfunction "GND_8") (pintype "unspecified"))
      (node (ref "IO1") (pin "2") (pinfunction "2_2") (pintype "unspecified"))
      (node (ref "IO2") (pin "2") (pinfunction "2_2") (pintype "unspecified"))
      (node (ref "IO3") (pin "2") (pinfunction "2_2") (pintype "unspecified"))
      (node (ref "IO4") (pin "2") (pinfunction "2_2") (pintype "unspecified"))
      (node (ref "IO5") (pin "2") (pinfunction "2_2") (pintype "unspecified"))
      (node (ref "IO6") (pin "2") (pinfunction "2_2") (pintype "unspecified"))
      (node (ref "IO7") (pin "2") (pinfunction "2_2") (pintype "unspecified"))
      (node (ref "IO8") (pin "2") (pinfunction "2_2") (pintype "unspecified"))
      (node (ref "Q200") (pin "2") (pinfunction "S_2") (pintype "unspecified"))
      (node (ref "Q201") (pin "2") (pinfunction "S_2") (pintype "unspecified"))
      (node (ref "Q202") (pin "2") (pinfunction "S_2") (pintype "unspecified"))
      (node (ref "Q203") (pin "2") (pinfunction "S_2") (pintype "unspecified"))
      (node (ref "Q204") (pin "2") (pinfunction "S_2") (pintype "unspecified"))
      (node (ref "Q205") (pin "2") (pinfunction "S_2") (pintype "unspecified"))
      (node (ref "Q206") (pin "2") (pinfunction "S_2") (pintype "unspecified"))
      (node (ref "Q207") (pin "2") (pinfunction "S_2") (pintype "unspecified"))
      (node (ref "Q210") (pin "2") (pinfunction "S_2") (pintype "unspecified"))
      (node (ref "Q211") (pin "2") (pinfunction "S_2") (pintype "unspecified"))
      (node (ref "Q212") (pin "2") (pinfunction "S_2") (pintype "unspecified"))
      (node (ref "Q213") (pin "2") (pinfunction "S_2") (pintype "unspecified"))
      (node (ref "Q214") (pin "2") (pinfunction "S_2") (pintype "unspecified"))
      (node (ref "Q215") (pin "2") (pinfunction "S_2") (pintype "unspecified"))
      (node (ref "Q216") (pin "2") (pinfunction "S_2") (pintype "unspecified"))
      (node (ref "Q217") (pin "2") (pinfunction "S_2") (pintype "unspecified"))
      (node (ref "QWIIC") (pin "1") (pinfunction "GND_1") (pintype "unspecified"))
      (node (ref "QWIIC") (pin "5") (pinfunction "NC1_5") (pintype "unspecified"))
      (node (ref "QWIIC") (pin "6") (pinfunction "NC2_6") (pintype "unspecified"))
      (node (ref "R110") (pin "1") (pinfunction "1_1") (pintype "input"))
      (node (ref "R19") (pin "2") (pinfunction "2_2") (pintype "input"))
      (node (ref "R208") (pin "2") (pinfunction "2_2") (pintype "input"))
      (node (ref "R41") (pin "1") (pinfunction "1_1") (pintype "input"))
      (node (ref "R46") (pin "2") (pinfunction "2_2") (pintype "input"))
      (node (ref "SUPPLY") (pin "2") (pinfunction "2_2") (pintype "unspecified"))
      (node (ref "SUPPLY") (pin "3") (pinfunction "3_3") (pintype "unspecified"))
      (node (ref "SW4") (pin "2") (pinfunction "2_2") (pintype "unspecified"))
      (node (ref "SW4") (pin "C") (pinfunction "C_C") (pintype "unspecified"))
      (node (ref "SW4") (pin "MT1") (pinfunction "MT1_MT1") (pintype "unspecified"))
      (node (ref "SW4") (pin "MT2") (pinfunction "MT2_MT2") (pintype "unspecified"))
      (node (ref "TEMP1") (pin "2") (pinfunction "2_2") (pintype "unspecified"))
      (node (ref "TEMP10") (pin "2") (pinfunction "2_2") (pintype "unspecified"))
      (node (ref "TEMP11") (pin "2") (pinfunction "2_2") (pintype "unspecified"))
      (node (ref "TEMP12") (pin "2") (pinfunction "2_2") (pintype "unspecified"))
      (node (ref "TEMP13") (pin "2") (pinfunction "2_2") (pintype "unspecified"))
      (node (ref "TEMP14") (pin "2") (pinfunction "2_2") (pintype "unspecified"))
      (node (ref "TEMP15") (pin "2") (pinfunction "2_2") (pintype "unspecified"))
      (node (ref "TEMP16") (pin "2") (pinfunction "2_2") (pintype "unspecified"))
      (node (ref "TEMP2") (pin "2") (pinfunction "2_2") (pintype "unspecified"))
      (node (ref "TEMP3") (pin "2") (pinfunction "2_2") (pintype "unspecified"))
      (node (ref "TEMP4") (pin "2") (pinfunction "2_2") (pintype "unspecified"))
      (node (ref "TEMP5") (pin "2") (pinfunction "2_2") (pintype "unspecified"))
      (node (ref "TEMP6") (pin "2") (pinfunction "2_2") (pintype "unspecified"))
      (node (ref "TEMP7") (pin "2") (pinfunction "2_2") (pintype "unspecified"))
      (node (ref "TEMP8") (pin "2") (pinfunction "2_2") (pintype "unspecified"))
      (node (ref "TEMP9") (pin "2") (pinfunction "2_2") (pintype "unspecified"))
      (node (ref "U1") (pin "4") (pinfunction "GND_4") (pintype "unspecified"))
      (node (ref "U2") (pin "3") (pinfunction "-VO_3") (pintype "unspecified"))
      (node (ref "U290") (pin "6") (pinfunction "E#_6") (pintype "unspecified"))
      (node (ref "U290") (pin "7") (pinfunction "VEE_7") (pintype "unspecified"))
      (node (ref "U290") (pin "8") (pinfunction "VSS_8") (pintype "unspecified"))
      (node (ref "U3") (pin "6") (pinfunction "E#_6") (pintype "unspecified"))
      (node (ref "U3") (pin "7") (pinfunction "VEE_7") (pintype "unspecified"))
      (node (ref "U3") (pin "8") (pinfunction "VSS_8") (pintype "unspecified"))
      (node (ref "U300") (pin "3") (pinfunction "EM_3") (pintype "unspecified"))
      (node (ref "U301") (pin "3") (pinfunction "EM_3") (pintype "unspecified"))
      (node (ref "U302") (pin "3") (pinfunction "EM_3") (pintype "unspecified"))
      (node (ref "U303") (pin "3") (pinfunction "EM_3") (pintype "unspecified"))
      (node (ref "U304") (pin "3") (pinfunction "EM_3") (pintype "unspecified"))
      (node (ref "U305") (pin "3") (pinfunction "EM_3") (pintype "unspecified"))
      (node (ref "U306") (pin "3") (pinfunction "EM_3") (pintype "unspecified"))
      (node (ref "U307") (pin "3") (pinfunction "EM_3") (pintype "unspecified"))
      (node (ref "U390") (pin "6") (pinfunction "E#_6") (pintype "unspecified"))
      (node (ref "U390") (pin "7") (pinfunction "VEE_7") (pintype "unspecified"))
      (node (ref "U390") (pin "8") (pinfunction "VSS_8") (pintype "unspecified"))
      (node (ref "U6") (pin "6") (pinfunction "E#_6") (pintype "unspecified"))
      (node (ref "U6") (pin "7") (pinfunction "VEE_7") (pintype "unspecified"))
      (node (ref "U6") (pin "8") (pinfunction "VSS_8") (pintype "unspecified"))
      (node (ref "U7") (pin "4") (pinfunction "GND_4") (pintype "unspecified"))
    )
    (net (code "4") (name "A") (class "Default")
      (node (ref "GP1") (pin "9") (pinfunction "GP6_9") (pintype "unspecified"))
      (node (ref "SW4") (pin "A") (pinfunction "A_A") (pintype "unspecified"))
    )
    (net (code "5") (name "ACin0") (class "Default")
      (node (ref "AC-IN1") (pin "4") (pinfunction "4_4") (pintype "unspecified"))
      (node (ref "R370") (pin "1") (pinfunction "1_1") (pintype "input"))
    )
    (net (code "6") (name "ACin1") (class "Default")
      (node (ref "AC-IN1") (pin "3") (pinfunction "3_3") (pintype "unspecified"))
      (node (ref "R371") (pin "1") (pinfunction "1_1") (pintype "input"))
    )
    (net (code "7") (name "ACin2") (class "Default")
      (node (ref "AC-IN1") (pin "2") (pinfunction "2_2") (pintype "unspecified"))
      (node (ref "R372") (pin "1") (pinfunction "1_1") (pintype "input"))
    )
    (net (code "8") (name "ACin3") (class "Default")
      (node (ref "AC-IN1") (pin "1") (pinfunction "1_1") (pintype "unspecified"))
      (node (ref "R373") (pin "1") (pinfunction "1_1") (pintype "input"))
    )
    (net (code "9") (name "ACin4") (class "Default")
      (node (ref "AC-IN2") (pin "4") (pinfunction "4_4") (pintype "unspecified"))
      (node (ref "R374") (pin "1") (pinfunction "1_1") (pintype "input"))
    )
    (net (code "10") (name "ACin5") (class "Default")
      (node (ref "AC-IN2") (pin "3") (pinfunction "3_3") (pintype "unspecified"))
      (node (ref "R375") (pin "1") (pinfunction "1_1") (pintype "input"))
    )
    (net (code "11") (name "ACin6") (class "Default")
      (node (ref "AC-IN2") (pin "2") (pinfunction "2_2") (pintype "unspecified"))
      (node (ref "R376") (pin "1") (pinfunction "1_1") (pintype "input"))
    )
    (net (code "12") (name "ACin7") (class "Default")
      (node (ref "AC-IN2") (pin "1") (pinfunction "1_1") (pintype "unspecified"))
      (node (ref "R377") (pin "1") (pinfunction "1_1") (pintype "input"))
    )
    (net (code "13") (name "AIO0") (class "Default")
      (node (ref "D1") (pin "2") (pinfunction "A_2") (pintype "unspecified"))
      (node (ref "D11") (pin "1") (pinfunction "C_1") (pintype "unspecified"))
      (node (ref "GP1") (pin "31") (pinfunction "GP26_31") (pintype "unspecified"))
      (node (ref "R1") (pin "2") (pinfunction "2_2") (pintype "input"))
      (node (ref "R11") (pin "1") (pinfunction "1_1") (pintype "input"))
    )
    (net (code "14") (name "AIO1") (class "Default")
      (node (ref "D12") (pin "1") (pinfunction "C_1") (pintype "unspecified"))
      (node (ref "D2") (pin "2") (pinfunction "A_2") (pintype "unspecified"))
      (node (ref "GP1") (pin "32") (pinfunction "GP27_32") (pintype "unspecified"))
      (node (ref "R12") (pin "1") (pinfunction "1_1") (pintype "input"))
      (node (ref "R2") (pin "2") (pinfunction "2_2") (pintype "input"))
    )
    (net (code "15") (name "AIO2") (class "Default")
      (node (ref "D13") (pin "1") (pinfunction "C_1") (pintype "unspecified"))
      (node (ref "D3") (pin "2") (pinfunction "A_2") (pintype "unspecified"))
      (node (ref "GP1") (pin "34") (pinfunction "GP28_34") (pintype "unspecified"))
      (node (ref "R13") (pin "1") (pinfunction "1_1") (pintype "input"))
      (node (ref "R3") (pin "2") (pinfunction "2_2") (pintype "input"))
    )
    (net (code "16") (name "B") (class "Default")
      (node (ref "GP1") (pin "10") (pinfunction "GP7_10") (pintype "unspecified"))
      (node (ref "SW4") (pin "B") (pinfunction "B_B") (pintype "unspecified"))
    )
    (net (code "17") (name "C") (class "Default")
      (node (ref "GP1") (pin "11") (pinfunction "GP8_11") (pintype "unspecified"))
      (node (ref "SW4") (pin "1") (pinfunction "1_1") (pintype "unspecified"))
    )
    (net (code "18") (name "DHT") (class "Default")
      (node (ref "GP1") (pin "6") (pinfunction "GP4_6") (pintype "unspecified"))
      (node (ref "R28") (pin "1") (pinfunction "1_1") (pintype "input"))
      (node (ref "U7") (pin "2") (pinfunction "SDA_2") (pintype "unspecified"))
    )
    (net (code "19") (name "IO3") (class "Default")
      (node (ref "D14") (pin "1") (pinfunction "C_1") (pintype "unspecified"))
      (node (ref "D4") (pin "2") (pinfunction "A_2") (pintype "unspecified"))
      (node (ref "GP1") (pin "29") (pinfunction "GP22_29") (pintype "unspecified"))
      (node (ref "R14") (pin "1") (pinfunction "1_1") (pintype "input"))
      (node (ref "R4") (pin "2") (pinfunction "2_2") (pintype "input"))
    )
    (net (code "20") (name "IO4") (class "Default")
      (node (ref "D15") (pin "1") (pinfunction "C_1") (pintype "unspecified"))
      (node (ref "D5") (pin "2") (pinfunction "A_2") (pintype "unspecified"))
      (node (ref "GP1") (pin "25") (pinfunction "GP19_25") (pintype "unspecified"))
      (node (ref "R15") (pin "1") (pinfunction "1_1") (pintype "input"))
      (node (ref "R5") (pin "2") (pinfunction "2_2") (pintype "input"))
    )
    (net (code "21") (name "IO5") (class "Default")
      (node (ref "D16") (pin "1") (pinfunction "C_1") (pintype "unspecified"))
      (node (ref "D6") (pin "2") (pinfunction "A_2") (pintype "unspecified"))
      (node (ref "GP1") (pin "24") (pinfunction "GP18_24") (pintype "unspecified"))
      (node (ref "R16") (pin "1") (pinfunction "1_1") (pintype "input"))
      (node (ref "R6") (pin "2") (pinfunction "2_2") (pintype "input"))
    )
    (net (code "22") (name "IO6") (class "Default")
      (node (ref "D17") (pin "1") (pinfunction "C_1") (pintype "unspecified"))
      (node (ref "D7") (pin "2") (pinfunction "A_2") (pintype "unspecified"))
      (node (ref "GP1") (pin "22") (pinfunction "GP17_22") (pintype "unspecified"))
      (node (ref "R17") (pin "1") (pinfunction "1_1") (pintype "input"))
      (node (ref "R7") (pin "2") (pinfunction "2_2") (pintype "input"))
    )
    (net (code "23") (name "IO7") (class "Default")
      (node (ref "D18") (pin "1") (pinfunction "C_1") (pintype "unspecified"))
      (node (ref "D8") (pin "2") (pinfunction "A_2") (pintype "unspecified"))
      (node (ref "GP1") (pin "21") (pinfunction "GP16_21") (pintype "unspecified"))
      (node (ref "R18") (pin "1") (pinfunction "1_1") (pintype "input"))
      (node (ref "R8") (pin "2") (pinfunction "2_2") (pintype "input"))
    )
    (net (code "24") (name "L") (class "Default")
      (node (ref "AC-MAINS") (pin "1") (pinfunction "1_1") (pintype "unspecified"))
      (node (ref "AC-MAINS") (pin "2") (pinfunction "2_2") (pintype "unspecified"))
      (node (ref "F1") (pin "2") (pinfunction "2_2") (pintype "unspecified"))
      (node (ref "TP14") (pin "1") (pinfunction "1_1") (pintype "unspecified"))
    )
    (net (code "25") (name "L0") (class "Default")
      (node (ref "AC-OUT1") (pin "4") (pinfunction "4_4") (pintype "unspecified"))
      (node (ref "REL200") (pin "8") (pinfunction "8_8") (pintype "input"))
    )
    (net (code "26") (name "L1") (class "Default")
      (node (ref "AC-OUT1") (pin "2") (pinfunction "2_2") (pintype "unspecified"))
      (node (ref "REL201") (pin "5") (pinfunction "NO_5") (pintype "unspecified"))
    )
    (net (code "27") (name "L2") (class "Default")
      (node (ref "AC-OUT2") (pin "4") (pinfunction "4_4") (pintype "unspecified"))
      (node (ref "REL202") (pin "5") (pinfunction "NO_5") (pintype "unspecified"))
    )
    (net (code "28") (name "L3") (class "Default")
      (node (ref "AC-OUT2") (pin "2") (pinfunction "2_2") (pintype "unspecified"))
      (node (ref "REL203") (pin "5") (pinfunction "NO_5") (pintype "unspecified"))
    )
    (net (code "29") (name "L4") (class "Default")
      (node (ref "AC-OUT3") (pin "4") (pinfunction "4_4") (pintype "unspecified"))
      (node (ref "REL204") (pin "5") (pinfunction "NO_5") (pintype "unspecified"))
    )
    (net (code "30") (name "L5") (class "Default")
      (node (ref "AC-OUT3") (pin "2") (pinfunction "2_2") (pintype "unspecified"))
      (node (ref "REL205") (pin "5") (pinfunction "NO_5") (pintype "unspecified"))
    )
    (net (code "31") (name "L6") (class "Default")
      (node (ref "AC-OUT4") (pin "4") (pinfunction "4_4") (pintype "unspecified"))
      (node (ref "REL206") (pin "5") (pinfunction "NO_5") (pintype "unspecified"))
    )
    (net (code "32") (name "L7") (class "Default")
      (node (ref "AC-OUT4") (pin "2") (pinfunction "2_2") (pintype "unspecified"))
      (node (ref "REL207") (pin "5") (pinfunction "NO_5") (pintype "unspecified"))
    )
    (net (code "33") (name "Mux0") (class "Default")
      (node (ref "GP1") (pin "14") (pinfunction "GP10_14") (pintype "unspecified"))
      (node (ref "U290") (pin "11") (pinfunction "S0_11") (pintype "unspecified"))
      (node (ref "U3") (pin "11") (pinfunction "S0_11") (pintype "unspecified"))
      (node (ref "U390") (pin "11") (pinfunction "S0_11") (pintype "unspecified"))
      (node (ref "U6") (pin "11") (pinfunction "S0_11") (pintype "unspecified"))
    )
    (net (code "34") (name "Mux1") (class "Default")
      (node (ref "GP1") (pin "15") (pinfunction "GP11_15") (pintype "unspecified"))
      (node (ref "U290") (pin "10") (pinfunction "S1_10") (pintype "unspecified"))
      (node (ref "U3") (pin "10") (pinfunction "S1_10") (pintype "unspecified"))
      (node (ref "U390") (pin "10") (pinfunction "S1_10") (pintype "unspecified"))
      (node (ref "U6") (pin "10") (pinfunction "S1_10") (pintype "unspecified"))
    )
    (net (code "35") (name "Mux2") (class "Default")
      (node (ref "GP1") (pin "16") (pinfunction "GP12_16") (pintype "unspecified"))
      (node (ref "U290") (pin "9") (pinfunction "S2_9") (pintype "unspecified"))
      (node (ref "U3") (pin "9") (pinfunction "S2_9") (pintype "unspecified"))
      (node (ref "U390") (pin "9") (pinfunction "S2_9") (pintype "unspecified"))
      (node (ref "U6") (pin "9") (pinfunction "S2_9") (pintype "unspecified"))
    )
    (net (code "36") (name "MuxA") (class "Default")
      (node (ref "GP1") (pin "1") (pinfunction "GP0_1") (pintype "unspecified"))
      (node (ref "U3") (pin "3") (pinfunction "Z_3") (pintype "unspecified"))
    )
    (net (code "37") (name "MuxA0") (class "Default")
      (node (ref "R26") (pin "1") (pinfunction "1_1") (pintype "input"))
      (node (ref "TEMP1") (pin "3") (pinfunction "3_3") (pintype "unspecified"))
      (node (ref "U3") (pin "13") (pinfunction "Y0_13") (pintype "unspecified"))
    )
    (net (code "38") (name "MuxA1") (class "Default")
      (node (ref "R25") (pin "1") (pinfunction "1_1") (pintype "input"))
      (node (ref "TEMP2") (pin "3") (pinfunction "3_3") (pintype "unspecified"))
      (node (ref "U3") (pin "14") (pinfunction "Y1_14") (pintype "unspecified"))
    )
    (net (code "39") (name "MuxA2") (class "Default")
      (node (ref "R24") (pin "1") (pinfunction "1_1") (pintype "input"))
      (node (ref "TEMP3") (pin "3") (pinfunction "3_3") (pintype "unspecified"))
      (node (ref "U3") (pin "15") (pinfunction "Y2_15") (pintype "unspecified"))
    )
    (net (code "40") (name "MuxA3") (class "Default")
      (node (ref "R27") (pin "1") (pinfunction "1_1") (pintype "input"))
      (node (ref "TEMP4") (pin "3") (pinfunction "3_3") (pintype "unspecified"))
      (node (ref "U3") (pin "12") (pinfunction "Y3_12") (pintype "unspecified"))
    )
    (net (code "41") (name "MuxA4") (class "Default")
      (node (ref "R20") (pin "1") (pinfunction "1_1") (pintype "input"))
      (node (ref "TEMP5") (pin "3") (pinfunction "3_3") (pintype "unspecified"))
      (node (ref "U3") (pin "1") (pinfunction "Y4_1") (pintype "unspecified"))
    )
    (net (code "42") (name "MuxA5") (class "Default")
      (node (ref "R23") (pin "1") (pinfunction "1_1") (pintype "input"))
      (node (ref "TEMP6") (pin "3") (pinfunction "3_3") (pintype "unspecified"))
      (node (ref "U3") (pin "5") (pinfunction "Y5_5") (pintype "unspecified"))
    )
    (net (code "43") (name "MuxA6") (class "Default")
      (node (ref "R21") (pin "1") (pinfunction "1_1") (pintype "input"))
      (node (ref "TEMP7") (pin "3") (pinfunction "3_3") (pintype "unspecified"))
      (node (ref "U3") (pin "2") (pinfunction "Y6_2") (pintype "unspecified"))
    )
    (net (code "44") (name "MuxA7") (class "Default")
      (node (ref "R22") (pin "1") (pinfunction "1_1") (pintype "input"))
      (node (ref "TEMP8") (pin "3") (pinfunction "3_3") (pintype "unspecified"))
      (node (ref "U3") (pin "4") (pinfunction "Y7_4") (pintype "unspecified"))
    )
    (net (code "45") (name "MuxAC") (class "Default")
      (node (ref "GP1") (pin "4") (pinfunction "GP2_4") (pintype "unspecified"))
      (node (ref "R110") (pin "2") (pinfunction "2_2") (pintype "input"))
      (node (ref "U390") (pin "3") (pinfunction "Z_3") (pintype "unspecified"))
    )
    (net (code "46") (name "MuxAC0") (class "Default")
      (node (ref "AC0") (pin "1") (pinfunction "A_1") (pintype "input"))
      (node (ref "R380") (pin "1") (pinfunction "1_1") (pintype "input"))
      (node (ref "U390") (pin "13") (pinfunction "Y0_13") (pintype "unspecified"))
    )
    (net (code "47") (name "MuxAC1") (class "Default")
      (node (ref "AC1") (pin "1") (pinfunction "A_1") (pintype "input"))
      (node (ref "R381") (pin "1") (pinfunction "1_1") (pintype "input"))
      (node (ref "U390") (pin "14") (pinfunction "Y1_14") (pintype "unspecified"))
    )
    (net (code "48") (name "MuxAC2") (class "Default")
      (node (ref "AC2") (pin "1") (pinfunction "A_1") (pintype "input"))
      (node (ref "R382") (pin "1") (pinfunction "1_1") (pintype "input"))
      (node (ref "U390") (pin "15") (pinfunction "Y2_15") (pintype "unspecified"))
    )
    (net (code "49") (name "MuxAC3") (class "Default")
      (node (ref "AC3") (pin "1") (pinfunction "A_1") (pintype "input"))
      (node (ref "R383") (pin "1") (pinfunction "1_1") (pintype "input"))
      (node (ref "U390") (pin "12") (pinfunction "Y3_12") (pintype "unspecified"))
    )
    (net (code "50") (name "MuxAC4") (class "Default")
      (node (ref "AC4") (pin "1") (pinfunction "A_1") (pintype "input"))
      (node (ref "R384") (pin "1") (pinfunction "1_1") (pintype "input"))
      (node (ref "U390") (pin "1") (pinfunction "Y4_1") (pintype "unspecified"))
    )
    (net (code "51") (name "MuxAC5") (class "Default")
      (node (ref "AC5") (pin "1") (pinfunction "A_1") (pintype "input"))
      (node (ref "R385") (pin "1") (pinfunction "1_1") (pintype "input"))
      (node (ref "U390") (pin "5") (pinfunction "Y5_5") (pintype "unspecified"))
    )
    (net (code "52") (name "MuxAC6") (class "Default")
      (node (ref "AC6") (pin "1") (pinfunction "A_1") (pintype "input"))
      (node (ref "R386") (pin "1") (pinfunction "1_1") (pintype "input"))
      (node (ref "U390") (pin "2") (pinfunction "Y6_2") (pintype "unspecified"))
    )
    (net (code "53") (name "MuxAC7") (class "Default")
      (node (ref "AC7") (pin "1") (pinfunction "A_1") (pintype "input"))
      (node (ref "R387") (pin "1") (pinfunction "1_1") (pintype "input"))
      (node (ref "U390") (pin "4") (pinfunction "Y7_4") (pintype "unspecified"))
    )
    (net (code "54") (name "MuxB") (class "Default")
      (node (ref "GP1") (pin "2") (pinfunction "GP1_2") (pintype "unspecified"))
      (node (ref "U6") (pin "3") (pinfunction "Z_3") (pintype "unspecified"))
    )
    (net (code "55") (name "MuxB0") (class "Default")
      (node (ref "R35") (pin "1") (pinfunction "1_1") (pintype "input"))
      (node (ref "TEMP9") (pin "3") (pinfunction "3_3") (pintype "unspecified"))
      (node (ref "U6") (pin "13") (pinfunction "Y0_13") (pintype "unspecified"))
    )
    (net (code "56") (name "MuxB1") (class "Default")
      (node (ref "R36") (pin "1") (pinfunction "1_1") (pintype "input"))
      (node (ref "TEMP10") (pin "3") (pinfunction "3_3") (pintype "unspecified"))
      (node (ref "U6") (pin "14") (pinfunction "Y1_14") (pintype "unspecified"))
    )
    (net (code "57") (name "MuxB2") (class "Default")
      (node (ref "R34") (pin "1") (pinfunction "1_1") (pintype "input"))
      (node (ref "TEMP11") (pin "3") (pinfunction "3_3") (pintype "unspecified"))
      (node (ref "U6") (pin "15") (pinfunction "Y2_15") (pintype "unspecified"))
    )
    (net (code "58") (name "MuxB3") (class "Default")
      (node (ref "R37") (pin "1") (pinfunction "1_1") (pintype "input"))
      (node (ref "TEMP12") (pin "3") (pinfunction "3_3") (pintype "unspecified"))
      (node (ref "U6") (pin "12") (pinfunction "Y3_12") (pintype "unspecified"))
    )
    (net (code "59") (name "MuxB4") (class "Default")
      (node (ref "R30") (pin "1") (pinfunction "1_1") (pintype "input"))
      (node (ref "TEMP13") (pin "3") (pinfunction "3_3") (pintype "unspecified"))
      (node (ref "U6") (pin "1") (pinfunction "Y4_1") (pintype "unspecified"))
    )
    (net (code "60") (name "MuxB5") (class "Default")
      (node (ref "R33") (pin "1") (pinfunction "1_1") (pintype "input"))
      (node (ref "TEMP14") (pin "3") (pinfunction "3_3") (pintype "unspecified"))
      (node (ref "U6") (pin "5") (pinfunction "Y5_5") (pintype "unspecified"))
    )
    (net (code "61") (name "MuxB6") (class "Default")
      (node (ref "R31") (pin "1") (pinfunction "1_1") (pintype "input"))
      (node (ref "TEMP15") (pin "3") (pinfunction "3_3") (pintype "unspecified"))
      (node (ref "U6") (pin "2") (pinfunction "Y6_2") (pintype "unspecified"))
    )
    (net (code "62") (name "MuxB7") (class "Default")
      (node (ref "R32") (pin "1") (pinfunction "1_1") (pintype "input"))
      (node (ref "TEMP16") (pin "3") (pinfunction "3_3") (pintype "unspecified"))
      (node (ref "U6") (pin "4") (pinfunction "Y7_4") (pintype "unspecified"))
    )
    (net (code "63") (name "MuxR0") (class "Default")
      (node (ref "Q210") (pin "1") (pinfunction "G_1") (pintype "unspecified"))
      (node (ref "R210") (pin "2") (pinfunction "2_2") (pintype "input"))
      (node (ref "U290") (pin "13") (pinfunction "Y0_13") (pintype "unspecified"))
    )
    (net (code "64") (name "MuxR1") (class "Default")
      (node (ref "Q211") (pin "1") (pinfunction "G_1") (pintype "unspecified"))
      (node (ref "R211") (pin "2") (pinfunction "2_2") (pintype "input"))
      (node (ref "U290") (pin "14") (pinfunction "Y1_14") (pintype "unspecified"))
    )
    (net (code "65") (name "MuxR2") (class "Default")
      (node (ref "Q212") (pin "1") (pinfunction "G_1") (pintype "unspecified"))
      (node (ref "R212") (pin "2") (pinfunction "2_2") (pintype "input"))
      (node (ref "U290") (pin "15") (pinfunction "Y2_15") (pintype "unspecified"))
    )
    (net (code "66") (name "MuxR3") (class "Default")
      (node (ref "Q213") (pin "1") (pinfunction "G_1") (pintype "unspecified"))
      (node (ref "R213") (pin "2") (pinfunction "2_2") (pintype "input"))
      (node (ref "U290") (pin "12") (pinfunction "Y3_12") (pintype "unspecified"))
    )
    (net (code "67") (name "MuxR4") (class "Default")
      (node (ref "Q214") (pin "1") (pinfunction "G_1") (pintype "unspecified"))
      (node (ref "R214") (pin "2") (pinfunction "2_2") (pintype "input"))
      (node (ref "U290") (pin "1") (pinfunction "Y4_1") (pintype "unspecified"))
    )
    (net (code "68") (name "MuxR5") (class "Default")
      (node (ref "Q215") (pin "1") (pinfunction "G_1") (pintype "unspecified"))
      (node (ref "R215") (pin "2") (pinfunction "2_2") (pintype "input"))
      (node (ref "U290") (pin "5") (pinfunction "Y5_5") (pintype "unspecified"))
    )
    (net (code "69") (name "MuxR6") (class "Default")
      (node (ref "Q216") (pin "1") (pinfunction "G_1") (pintype "unspecified"))
      (node (ref "R216") (pin "2") (pinfunction "2_2") (pintype "input"))
      (node (ref "U290") (pin "2") (pinfunction "Y6_2") (pintype "unspecified"))
    )
    (net (code "70") (name "MuxR7") (class "Default")
      (node (ref "Q217") (pin "1") (pinfunction "G_1") (pintype "unspecified"))
      (node (ref "R217") (pin "2") (pinfunction "2_2") (pintype "input"))
      (node (ref "U290") (pin "4") (pinfunction "Y7_4") (pintype "unspecified"))
    )
    (net (code "71") (name "MuxRel") (class "Default")
      (node (ref "GP1") (pin "5") (pinfunction "GP3_5") (pintype "unspecified"))
      (node (ref "U290") (pin "3") (pinfunction "Z_3") (pintype "unspecified"))
    )
    (net (code "72") (name "N") (class "Default")
      (node (ref "AC-MAINS") (pin "3") (pinfunction "3_3") (pintype "unspecified"))
      (node (ref "AC-MAINS") (pin "4") (pinfunction "4_4") (pintype "unspecified"))
      (node (ref "D340") (pin "2") (pinfunction "A_2") (pintype "unspecified"))
      (node (ref "D341") (pin "2") (pinfunction "A_2") (pintype "unspecified"))
      (node (ref "D342") (pin "2") (pinfunction "A_2") (pintype "unspecified"))
      (node (ref "D343") (pin "2") (pinfunction "A_2") (pintype "unspecified"))
      (node (ref "D344") (pin "2") (pinfunction "A_2") (pintype "unspecified"))
      (node (ref "D345") (pin "2") (pinfunction "A_2") (pintype "unspecified"))
      (node (ref "D346") (pin "2") (pinfunction "A_2") (pintype "unspecified"))
      (node (ref "D347") (pin "2") (pinfunction "A_2") (pintype "unspecified"))
      (node (ref "D360") (pin "1") (pinfunction "K_1") (pintype "unspecified"))
      (node (ref "D361") (pin "1") (pinfunction "K_1") (pintype "unspecified"))
      (node (ref "D362") (pin "1") (pinfunction "K_1") (pintype "unspecified"))
      (node (ref "D363") (pin "1") (pinfunction "K_1") (pintype "unspecified"))
      (node (ref "D364") (pin "1") (pinfunction "K_1") (pintype "unspecified"))
      (node (ref "D365") (pin "1") (pinfunction "K_1") (pintype "unspecified"))
      (node (ref "D366") (pin "1") (pinfunction "K_1") (pintype "unspecified"))
      (node (ref "D367") (pin "1") (pinfunction "K_1") (pintype "unspecified"))
      (node (ref "R57") (pin "2") (pinfunction "2_2") (pintype "unspecified"))
      (node (ref "TP4") (pin "1") (pinfunction "1_1") (pintype "unspecified"))
      (node (ref "U2") (pin "2") (pinfunction "AC(L)_2") (pintype "unspecified"))
    )
    (net (code "73") (name "Net-(3.3V-A)") (class "Default")
      (node (ref "3.3V") (pin "1") (pinfunction "A_1") (pintype "unspecified"))
      (node (ref "R42") (pin "1") (pinfunction "1_1") (pintype "input"))
    )
    (net (code "74") (name "Net-(AC-OUT1-Pad1)") (class "Default")
      (node (ref "AC-OUT1") (pin "1") (pinfunction "1_1") (pintype "unspecified"))
      (node (ref "TP12") (pin "1") (pinfunction "1_1") (pintype "unspecified"))
    )
    (net (code "75") (name "Net-(AC-OUT1-Pad3)") (class "Default")
      (node (ref "AC-OUT1") (pin "3") (pinfunction "3_3") (pintype "unspecified"))
      (node (ref "TP13") (pin "1") (pinfunction "1_1") (pintype "unspecified"))
    )
    (net (code "76") (name "Net-(AC-OUT2-Pad1)") (class "Default")
      (node (ref "AC-OUT2") (pin "1") (pinfunction "1_1") (pintype "unspecified"))
      (node (ref "TP10") (pin "1") (pinfunction "1_1") (pintype "unspecified"))
    )
    (net (code "77") (name "Net-(AC-OUT2-Pad3)") (class "Default")
      (node (ref "AC-OUT2") (pin "3") (pinfunction "3_3") (pintype "unspecified"))
      (node (ref "TP11") (pin "1") (pinfunction "1_1") (pintype "unspecified"))
    )
    (net (code "78") (name "Net-(AC-OUT3-Pad1)") (class "Default")
      (node (ref "AC-OUT3") (pin "1") (pinfunction "1_1") (pintype "unspecified"))
      (node (ref "TP8") (pin "1") (pinfunction "1_1") (pintype "unspecified"))
    )
    (net (code "79") (name "Net-(AC-OUT3-Pad3)") (class "Default")
      (node (ref "AC-OUT3") (pin "3") (pinfunction "3_3") (pintype "unspecified"))
      (node (ref "TP9") (pin "1") (pinfunction "1_1") (pintype "unspecified"))
    )
    (net (code "80") (name "Net-(AC-OUT4-Pad1)") (class "Default")
      (node (ref "AC-OUT4") (pin "1") (pinfunction "1_1") (pintype "unspecified"))
      (node (ref "TP1") (pin "1") (pinfunction "1_1") (pintype "unspecified"))
    )
    (net (code "81") (name "Net-(AC-OUT4-Pad3)") (class "Default")
      (node (ref "AC-OUT4") (pin "3") (pinfunction "3_3") (pintype "unspecified"))
      (node (ref "TP7") (pin "1") (pinfunction "1_1") (pintype "unspecified"))
    )
    (net (code "82") (name "Net-(D200-A)") (class "Default")
      (node (ref "D200") (pin "2") (pinfunction "A_2") (pintype "unspecified"))
      (node (ref "Q200") (pin "1") (pinfunction "G_1") (pintype "unspecified"))
      (node (ref "Q210") (pin "3") (pinfunction "D_3") (pintype "unspecified"))
      (node (ref "R220") (pin "1") (pinfunction "1_1") (pintype "input"))
      (node (ref "REL200") (pin "1") (pinfunction "1_1") (pintype "input"))
    )
    (net (code "83") (name "Net-(D201-A)") (class "Default")
      (node (ref "D201") (pin "2") (pinfunction "A_2") (pintype "unspecified"))
      (node (ref "Q201") (pin "1") (pinfunction "G_1") (pintype "unspecified"))
      (node (ref "Q211") (pin "3") (pinfunction "D_3") (pintype "unspecified"))
      (node (ref "R221") (pin "1") (pinfunction "1_1") (pintype "input"))
      (node (ref "REL201") (pin "2") (pinfunction "COIL_2") (pintype "unspecified"))
    )
    (net (code "84") (name "Net-(D202-A)") (class "Default")
      (node (ref "D202") (pin "2") (pinfunction "A_2") (pintype "unspecified"))
      (node (ref "Q202") (pin "1") (pinfunction "G_1") (pintype "unspecified"))
      (node (ref "Q212") (pin "3") (pinfunction "D_3") (pintype "unspecified"))
      (node (ref "R222") (pin "1") (pinfunction "1_1") (pintype "input"))
      (node (ref "REL202") (pin "2") (pinfunction "COIL_2") (pintype "unspecified"))
    )
    (net (code "85") (name "Net-(D203-A)") (class "Default")
      (node (ref "D203") (pin "2") (pinfunction "A_2") (pintype "unspecified"))
      (node (ref "Q203") (pin "1") (pinfunction "G_1") (pintype "unspecified"))
      (node (ref "Q213") (pin "3") (pinfunction "D_3") (pintype "unspecified"))
      (node (ref "R223") (pin "1") (pinfunction "1_1") (pintype "input"))
      (node (ref "REL203") (pin "2") (pinfunction "COIL_2") (pintype "unspecified"))
    )
    (net (code "86") (name "Net-(D204-A)") (class "Default")
      (node (ref "D204") (pin "2") (pinfunction "A_2") (pintype "unspecified"))
      (node (ref "Q204") (pin "1") (pinfunction "G_1") (pintype "unspecified"))
      (node (ref "Q214") (pin "3") (pinfunction "D_3") (pintype "unspecified"))
      (node (ref "R224") (pin "1") (pinfunction "1_1") (pintype "input"))
      (node (ref "REL204") (pin "2") (pinfunction "COIL_2") (pintype "unspecified"))
    )
    (net (code "87") (name "Net-(D205-A)") (class "Default")
      (node (ref "D205") (pin "2") (pinfunction "A_2") (pintype "unspecified"))
      (node (ref "Q205") (pin "1") (pinfunction "G_1") (pintype "unspecified"))
      (node (ref "Q215") (pin "3") (pinfunction "D_3") (pintype "unspecified"))
      (node (ref "R225") (pin "1") (pinfunction "1_1") (pintype "input"))
      (node (ref "REL205") (pin "2") (pinfunction "COIL_2") (pintype "unspecified"))
    )
    (net (code "88") (name "Net-(D206-A)") (class "Default")
      (node (ref "D206") (pin "2") (pinfunction "A_2") (pintype "unspecified"))
      (node (ref "Q206") (pin "1") (pinfunction "G_1") (pintype "unspecified"))
      (node (ref "Q216") (pin "3") (pinfunction "D_3") (pintype "unspecified"))
      (node (ref "R226") (pin "1") (pinfunction "1_1") (pintype "input"))
      (node (ref "REL206") (pin "2") (pinfunction "COIL_2") (pintype "unspecified"))
    )
    (net (code "89") (name "Net-(D207-A)") (class "Default")
      (node (ref "D207") (pin "2") (pinfunction "A_2") (pintype "unspecified"))
      (node (ref "Q207") (pin "1") (pinfunction "G_1") (pintype "unspecified"))
      (node (ref "Q217") (pin "3") (pinfunction "D_3") (pintype "unspecified"))
      (node (ref "R227") (pin "1") (pinfunction "1_1") (pintype "input"))
      (node (ref "REL207") (pin "2") (pinfunction "COIL_2") (pintype "unspecified"))
    )
    (net (code "90") (name "Net-(D300-A)") (class "Default")
      (node (ref "D300") (pin "2") (pinfunction "A_2") (pintype "unspecified"))
      (node (ref "D310") (pin "1") (pinfunction "K_1") (pintype "unspecified"))
      (node (ref "D340") (pin "1") (pinfunction "K_1") (pintype "unspecified"))
      (node (ref "Q310") (pin "1") (pinfunction "G_1") (pintype "unspecified"))
      (node (ref "R320") (pin "2") (pinfunction "2_2") (pintype "input"))
    )
    (net (code "91") (name "Net-(D300-C)") (class "Default")
      (node (ref "C310") (pin "2") (pinfunction "2_2") (pintype "unspecified"))
      (node (ref "D300") (pin "1") (pinfunction "C_1") (pintype "unspecified"))
      (node (ref "D320") (pin "1") (pinfunction "C_1") (pintype "unspecified"))
      (node (ref "Q310") (pin "2") (pinfunction "S_2") (pintype "unspecified"))
    )
    (net (code "92") (name "Net-(D301-A)") (class "Default")
      (node (ref "D301") (pin "2") (pinfunction "A_2") (pintype "unspecified"))
      (node (ref "D311") (pin "1") (pinfunction "K_1") (pintype "unspecified"))
      (node (ref "D341") (pin "1") (pinfunction "K_1") (pintype "unspecified"))
      (node (ref "Q311") (pin "1") (pinfunction "G_1") (pintype "unspecified"))
      (node (ref "R321") (pin "2") (pinfunction "2_2") (pintype "input"))
    )
    (net (code "93") (name "Net-(D301-C)") (class "Default")
      (node (ref "C311") (pin "2") (pinfunction "2_2") (pintype "unspecified"))
      (node (ref "D301") (pin "1") (pinfunction "C_1") (pintype "unspecified"))
      (node (ref "D321") (pin "1") (pinfunction "C_1") (pintype "unspecified"))
      (node (ref "Q311") (pin "2") (pinfunction "S_2") (pintype "unspecified"))
    )
    (net (code "94") (name "Net-(D302-A)") (class "Default")
      (node (ref "D302") (pin "2") (pinfunction "A_2") (pintype "unspecified"))
      (node (ref "D312") (pin "1") (pinfunction "K_1") (pintype "unspecified"))
      (node (ref "D342") (pin "1") (pinfunction "K_1") (pintype "unspecified"))
      (node (ref "Q312") (pin "1") (pinfunction "G_1") (pintype "unspecified"))
      (node (ref "R322") (pin "2") (pinfunction "2_2") (pintype "input"))
    )
    (net (code "95") (name "Net-(D302-C)") (class "Default")
      (node (ref "C312") (pin "2") (pinfunction "2_2") (pintype "unspecified"))
      (node (ref "D302") (pin "1") (pinfunction "C_1") (pintype "unspecified"))
      (node (ref "D322") (pin "1") (pinfunction "C_1") (pintype "unspecified"))
      (node (ref "Q312") (pin "2") (pinfunction "S_2") (pintype "unspecified"))
    )
    (net (code "96") (name "Net-(D303-A)") (class "Default")
      (node (ref "D303") (pin "2") (pinfunction "A_2") (pintype "unspecified"))
      (node (ref "D313") (pin "1") (pinfunction "K_1") (pintype "unspecified"))
      (node (ref "D343") (pin "1") (pinfunction "K_1") (pintype "unspecified"))
      (node (ref "Q313") (pin "1") (pinfunction "G_1") (pintype "unspecified"))
      (node (ref "R323") (pin "2") (pinfunction "2_2") (pintype "input"))
    )
    (net (code "97") (name "Net-(D303-C)") (class "Default")
      (node (ref "C313") (pin "2") (pinfunction "2_2") (pintype "unspecified"))
      (node (ref "D303") (pin "1") (pinfunction "C_1") (pintype "unspecified"))
      (node (ref "D323") (pin "1") (pinfunction "C_1") (pintype "unspecified"))
      (node (ref "Q313") (pin "2") (pinfunction "S_2") (pintype "unspecified"))
    )
    (net (code "98") (name "Net-(D304-A)") (class "Default")
      (node (ref "D304") (pin "2") (pinfunction "A_2") (pintype "unspecified"))
      (node (ref "D314") (pin "1") (pinfunction "K_1") (pintype "unspecified"))
      (node (ref "D344") (pin "1") (pinfunction "K_1") (pintype "unspecified"))
      (node (ref "Q314") (pin "1") (pinfunction "G_1") (pintype "unspecified"))
      (node (ref "R324") (pin "2") (pinfunction "2_2") (pintype "input"))
    )
    (net (code "99") (name "Net-(D304-C)") (class "Default")
      (node (ref "C314") (pin "2") (pinfunction "2_2") (pintype "unspecified"))
      (node (ref "D304") (pin "1") (pinfunction "C_1") (pintype "unspecified"))
      (node (ref "D324") (pin "1") (pinfunction "C_1") (pintype "unspecified"))
      (node (ref "Q314") (pin "2") (pinfunction "S_2") (pintype "unspecified"))
    )
    (net (code "100") (name "Net-(D305-A)") (class "Default")
      (node (ref "D305") (pin "2") (pinfunction "A_2") (pintype "unspecified"))
      (node (ref "D315") (pin "1") (pinfunction "K_1") (pintype "unspecified"))
      (node (ref "D345") (pin "1") (pinfunction "K_1") (pintype "unspecified"))
      (node (ref "Q315") (pin "1") (pinfunction "G_1") (pintype "unspecified"))
      (node (ref "R325") (pin "2") (pinfunction "2_2") (pintype "input"))
    )
    (net (code "101") (name "Net-(D305-C)") (class "Default")
      (node (ref "C315") (pin "2") (pinfunction "2_2") (pintype "unspecified"))
      (node (ref "D305") (pin "1") (pinfunction "C_1") (pintype "unspecified"))
      (node (ref "D325") (pin "1") (pinfunction "C_1") (pintype "unspecified"))
      (node (ref "Q315") (pin "2") (pinfunction "S_2") (pintype "unspecified"))
    )
    (net (code "102") (name "Net-(D306-A)") (class "Default")
      (node (ref "D306") (pin "2") (pinfunction "A_2") (pintype "unspecified"))
      (node (ref "D316") (pin "1") (pinfunction "K_1") (pintype "unspecified"))
      (node (ref "D346") (pin "1") (pinfunction "K_1") (pintype "unspecified"))
      (node (ref "Q316") (pin "1") (pinfunction "G_1") (pintype "unspecified"))
      (node (ref "R326") (pin "2") (pinfunction "2_2") (pintype "input"))
    )
    (net (code "103") (name "Net-(D306-C)") (class "Default")
      (node (ref "C316") (pin "2") (pinfunction "2_2") (pintype "unspecified"))
      (node (ref "D306") (pin "1") (pinfunction "C_1") (pintype "unspecified"))
      (node (ref "D326") (pin "1") (pinfunction "C_1") (pintype "unspecified"))
      (node (ref "Q316") (pin "2") (pinfunction "S_2") (pintype "unspecified"))
    )
    (net (code "104") (name "Net-(D307-A)") (class "Default")
      (node (ref "D307") (pin "2") (pinfunction "A_2") (pintype "unspecified"))
      (node (ref "D317") (pin "1") (pinfunction "K_1") (pintype "unspecified"))
      (node (ref "D347") (pin "1") (pinfunction "K_1") (pintype "unspecified"))
      (node (ref "Q317") (pin "1") (pinfunction "G_1") (pintype "unspecified"))
      (node (ref "R327") (pin "2") (pinfunction "2_2") (pintype "input"))
    )
    (net (code "105") (name "Net-(D307-C)") (class "Default")
      (node (ref "C317") (pin "2") (pinfunction "2_2") (pintype "unspecified"))
      (node (ref "D307") (pin "1") (pinfunction "C_1") (pintype "unspecified"))
      (node (ref "D327") (pin "1") (pinfunction "C_1") (pintype "unspecified"))
      (node (ref "Q317") (pin "2") (pinfunction "S_2") (pintype "unspecified"))
    )
    (net (code "106") (name "Net-(D310-A)") (class "Default")
      (node (ref "D310") (pin "2") (pinfunction "A_2") (pintype "unspecified"))
      (node (ref "D350") (pin "1") (pinfunction "K_1") (pintype "unspecified"))
      (node (ref "R330") (pin "2") (pinfunction "2_2") (pintype "input"))
    )
    (net (code "107") (name "Net-(D311-A)") (class "Default")
      (node (ref "D311") (pin "2") (pinfunction "A_2") (pintype "unspecified"))
      (node (ref "D351") (pin "1") (pinfunction "K_1") (pintype "unspecified"))
      (node (ref "R331") (pin "2") (pinfunction "2_2") (pintype "input"))
    )
    (net (code "108") (name "Net-(D312-A)") (class "Default")
      (node (ref "D312") (pin "2") (pinfunction "A_2") (pintype "unspecified"))
      (node (ref "D352") (pin "1") (pinfunction "K_1") (pintype "unspecified"))
      (node (ref "R332") (pin "2") (pinfunction "2_2") (pintype "input"))
    )
    (net (code "109") (name "Net-(D313-A)") (class "Default")
      (node (ref "D313") (pin "2") (pinfunction "A_2") (pintype "unspecified"))
      (node (ref "D353") (pin "1") (pinfunction "K_1") (pintype "unspecified"))
      (node (ref "R333") (pin "2") (pinfunction "2_2") (pintype "input"))
    )
    (net (code "110") (name "Net-(D314-A)") (class "Default")
      (node (ref "D314") (pin "2") (pinfunction "A_2") (pintype "unspecified"))
      (node (ref "D354") (pin "1") (pinfunction "K_1") (pintype "unspecified"))
      (node (ref "R334") (pin "2") (pinfunction "2_2") (pintype "input"))
    )
    (net (code "111") (name "Net-(D315-A)") (class "Default")
      (node (ref "D315") (pin "2") (pinfunction "A_2") (pintype "unspecified"))
      (node (ref "D355") (pin "1") (pinfunction "K_1") (pintype "unspecified"))
      (node (ref "R335") (pin "2") (pinfunction "2_2") (pintype "input"))
    )
    (net (code "112") (name "Net-(D316-A)") (class "Default")
      (node (ref "D316") (pin "2") (pinfunction "A_2") (pintype "unspecified"))
      (node (ref "D356") (pin "1") (pinfunction "K_1") (pintype "unspecified"))
      (node (ref "R336") (pin "2") (pinfunction "2_2") (pintype "input"))
    )
    (net (code "113") (name "Net-(D317-A)") (class "Default")
      (node (ref "D317") (pin "2") (pinfunction "A_2") (pintype "unspecified"))
      (node (ref "D357") (pin "1") (pinfunction "K_1") (pintype "unspecified"))
      (node (ref "R337") (pin "2") (pinfunction "2_2") (pintype "input"))
    )
    (net (code "114") (name "Net-(D320-A)") (class "Default")
      (node (ref "D320") (pin "2") (pinfunction "A_2") (pintype "unspecified"))
      (node (ref "D330") (pin "1") (pinfunction "C_1") (pintype "unspecified"))
    )
    (net (code "115") (name "Net-(D321-A)") (class "Default")
      (node (ref "D321") (pin "2") (pinfunction "A_2") (pintype "unspecified"))
      (node (ref "D331") (pin "1") (pinfunction "C_1") (pintype "unspecified"))
    )
    (net (code "116") (name "Net-(D322-A)") (class "Default")
      (node (ref "D322") (pin "2") (pinfunction "A_2") (pintype "unspecified"))
      (node (ref "D332") (pin "1") (pinfunction "C_1") (pintype "unspecified"))
    )
    (net (code "117") (name "Net-(D323-A)") (class "Default")
      (node (ref "D323") (pin "2") (pinfunction "A_2") (pintype "unspecified"))
      (node (ref "D333") (pin "1") (pinfunction "C_1") (pintype "unspecified"))
    )
    (net (code "118") (name "Net-(D324-A)") (class "Default")
      (node (ref "D324") (pin "2") (pinfunction "A_2") (pintype "unspecified"))
      (node (ref "D334") (pin "1") (pinfunction "C_1") (pintype "unspecified"))
    )
    (net (code "119") (name "Net-(D325-A)") (class "Default")
      (node (ref "D325") (pin "2") (pinfunction "A_2") (pintype "unspecified"))
      (node (ref "D335") (pin "1") (pinfunction "C_1") (pintype "unspecified"))
    )
    (net (code "120") (name "Net-(D326-A)") (class "Default")
      (node (ref "D326") (pin "2") (pinfunction "A_2") (pintype "unspecified"))
      (node (ref "D336") (pin "1") (pinfunction "C_1") (pintype "unspecified"))
    )
    (net (code "121") (name "Net-(D327-A)") (class "Default")
      (node (ref "D327") (pin "2") (pinfunction "A_2") (pintype "unspecified"))
      (node (ref "D337") (pin "1") (pinfunction "C_1") (pintype "unspecified"))
    )
    (net (code "122") (name "Net-(D330-A)") (class "Default")
      (node (ref "C310") (pin "1") (pinfunction "1_1") (pintype "unspecified"))
      (node (ref "D330") (pin "2") (pinfunction "A_2") (pintype "unspecified"))
      (node (ref "D350") (pin "2") (pinfunction "A_2") (pintype "unspecified"))
      (node (ref "D360") (pin "2") (pinfunction "A_2") (pintype "unspecified"))
      (node (ref "R320") (pin "1") (pinfunction "1_1") (pintype "input"))
      (node (ref "U300") (pin "2") (pinfunction "CAT_2") (pintype "unspecified"))
    )
    (net (code "123") (name "Net-(D331-A)") (class "Default")
      (node (ref "C311") (pin "1") (pinfunction "1_1") (pintype "unspecified"))
      (node (ref "D331") (pin "2") (pinfunction "A_2") (pintype "unspecified"))
      (node (ref "D351") (pin "2") (pinfunction "A_2") (pintype "unspecified"))
      (node (ref "D361") (pin "2") (pinfunction "A_2") (pintype "unspecified"))
      (node (ref "R321") (pin "1") (pinfunction "1_1") (pintype "input"))
      (node (ref "U301") (pin "2") (pinfunction "CAT_2") (pintype "unspecified"))
    )
    (net (code "124") (name "Net-(D332-A)") (class "Default")
      (node (ref "C312") (pin "1") (pinfunction "1_1") (pintype "unspecified"))
      (node (ref "D332") (pin "2") (pinfunction "A_2") (pintype "unspecified"))
      (node (ref "D352") (pin "2") (pinfunction "A_2") (pintype "unspecified"))
      (node (ref "D362") (pin "2") (pinfunction "A_2") (pintype "unspecified"))
      (node (ref "R322") (pin "1") (pinfunction "1_1") (pintype "input"))
      (node (ref "U302") (pin "2") (pinfunction "CAT_2") (pintype "unspecified"))
    )
    (net (code "125") (name "Net-(D333-A)") (class "Default")
      (node (ref "C313") (pin "1") (pinfunction "1_1") (pintype "unspecified"))
      (node (ref "D333") (pin "2") (pinfunction "A_2") (pintype "unspecified"))
      (node (ref "D353") (pin "2") (pinfunction "A_2") (pintype "unspecified"))
      (node (ref "D363") (pin "2") (pinfunction "A_2") (pintype "unspecified"))
      (node (ref "R323") (pin "1") (pinfunction "1_1") (pintype "input"))
      (node (ref "U303") (pin "2") (pinfunction "CAT_2") (pintype "unspecified"))
    )
    (net (code "126") (name "Net-(D334-A)") (class "Default")
      (node (ref "C314") (pin "1") (pinfunction "1_1") (pintype "unspecified"))
      (node (ref "D334") (pin "2") (pinfunction "A_2") (pintype "unspecified"))
      (node (ref "D354") (pin "2") (pinfunction "A_2") (pintype "unspecified"))
      (node (ref "D364") (pin "2") (pinfunction "A_2") (pintype "unspecified"))
      (node (ref "R324") (pin "1") (pinfunction "1_1") (pintype "input"))
      (node (ref "U304") (pin "2") (pinfunction "CAT_2") (pintype "unspecified"))
    )
    (net (code "127") (name "Net-(D335-A)") (class "Default")
      (node (ref "C315") (pin "1") (pinfunction "1_1") (pintype "unspecified"))
      (node (ref "D335") (pin "2") (pinfunction "A_2") (pintype "unspecified"))
      (node (ref "D355") (pin "2") (pinfunction "A_2") (pintype "unspecified"))
      (node (ref "D365") (pin "2") (pinfunction "A_2") (pintype "unspecified"))
      (node (ref "R325") (pin "1") (pinfunction "1_1") (pintype "input"))
      (node (ref "U305") (pin "2") (pinfunction "CAT_2") (pintype "unspecified"))
    )
    (net (code "128") (name "Net-(D336-A)") (class "Default")
      (node (ref "C316") (pin "1") (pinfunction "1_1") (pintype "unspecified"))
      (node (ref "D336") (pin "2") (pinfunction "A_2") (pintype "unspecified"))
      (node (ref "D356") (pin "2") (pinfunction "A_2") (pintype "unspecified"))
      (node (ref "D366") (pin "2") (pinfunction "A_2") (pintype "unspecified"))
      (node (ref "R326") (pin "1") (pinfunction "1_1") (pintype "input"))
      (node (ref "U306") (pin "2") (pinfunction "CAT_2") (pintype "unspecified"))
    )
    (net (code "129") (name "Net-(D337-A)") (class "Default")
      (node (ref "C317") (pin "1") (pinfunction "1_1") (pintype "unspecified"))
      (node (ref "D337") (pin "2") (pinfunction "A_2") (pintype "unspecified"))
      (node (ref "D357") (pin "2") (pinfunction "A_2") (pintype "unspecified"))
      (node (ref "D367") (pin "2") (pinfunction "A_2") (pintype "unspecified"))
      (node (ref "R327") (pin "1") (pinfunction "1_1") (pintype "input"))
      (node (ref "U307") (pin "2") (pinfunction "CAT_2") (pintype "unspecified"))
    )
    (net (code "130") (name "Net-(IO1-Pad1)") (class "Default")
      (node (ref "IO1") (pin "1") (pinfunction "1_1") (pintype "unspecified"))
      (node (ref "PWR1") (pin "2") (pinfunction "2_2") (pintype "unspecified"))
    )
    (net (code "131") (name "Net-(IO1-Pad3)") (class "Default")
      (node (ref "IO1") (pin "3") (pinfunction "3_3") (pintype "unspecified"))
      (node (ref "R11") (pin "2") (pinfunction "2_2") (pintype "input"))
    )
    (net (code "132") (name "Net-(IO2-Pad1)") (class "Default")
      (node (ref "IO2") (pin "1") (pinfunction "1_1") (pintype "unspecified"))
      (node (ref "PWR2") (pin "2") (pinfunction "2_2") (pintype "unspecified"))
    )
    (net (code "133") (name "Net-(IO2-Pad3)") (class "Default")
      (node (ref "IO2") (pin "3") (pinfunction "3_3") (pintype "unspecified"))
      (node (ref "R12") (pin "2") (pinfunction "2_2") (pintype "input"))
    )
    (net (code "134") (name "Net-(IO3-Pad1)") (class "Default")
      (node (ref "IO3") (pin "1") (pinfunction "1_1") (pintype "unspecified"))
      (node (ref "PWR3") (pin "2") (pinfunction "2_2") (pintype "unspecified"))
    )
    (net (code "135") (name "Net-(IO3-Pad3)") (class "Default")
      (node (ref "IO3") (pin "3") (pinfunction "3_3") (pintype "unspecified"))
      (node (ref "R13") (pin "2") (pinfunction "2_2") (pintype "input"))
    )
    (net (code "136") (name "Net-(IO4-Pad1)") (class "Default")
      (node (ref "IO4") (pin "1") (pinfunction "1_1") (pintype "unspecified"))
      (node (ref "PWR4") (pin "2") (pinfunction "2_2") (pintype "unspecified"))
    )
    (net (code "137") (name "Net-(IO4-Pad3)") (class "Default")
      (node (ref "IO4") (pin "3") (pinfunction "3_3") (pintype "unspecified"))
      (node (ref "R14") (pin "2") (pinfunction "2_2") (pintype "input"))
    )
    (net (code "138") (name "Net-(IO5-Pad1)") (class "Default")
      (node (ref "IO5") (pin "1") (pinfunction "1_1") (pintype "unspecified"))
      (node (ref "PWR5") (pin "2") (pinfunction "2_2") (pintype "unspecified"))
    )
    (net (code "139") (name "Net-(IO5-Pad3)") (class "Default")
      (node (ref "IO5") (pin "3") (pinfunction "3_3") (pintype "unspecified"))
      (node (ref "R15") (pin "2") (pinfunction "2_2") (pintype "input"))
    )
    (net (code "140") (name "Net-(IO6-Pad1)") (class "Default")
      (node (ref "IO6") (pin "1") (pinfunction "1_1") (pintype "unspecified"))
      (node (ref "PWR6") (pin "2") (pinfunction "2_2") (pintype "unspecified"))
    )
    (net (code "141") (name "Net-(IO6-Pad3)") (class "Default")
      (node (ref "IO6") (pin "3") (pinfunction "3_3") (pintype "unspecified"))
      (node (ref "R16") (pin "2") (pinfunction "2_2") (pintype "input"))
    )
    (net (code "142") (name "Net-(IO7-Pad1)") (class "Default")
      (node (ref "IO7") (pin "1") (pinfunction "1_1") (pintype "unspecified"))
      (node (ref "PWR7") (pin "2") (pinfunction "2_2") (pintype "unspecified"))
    )
    (net (code "143") (name "Net-(IO7-Pad3)") (class "Default")
      (node (ref "IO7") (pin "3") (pinfunction "3_3") (pintype "unspecified"))
      (node (ref "R17") (pin "2") (pinfunction "2_2") (pintype "input"))
    )
    (net (code "144") (name "Net-(IO8-Pad1)") (class "Default")
      (node (ref "IO8") (pin "1") (pinfunction "1_1") (pintype "unspecified"))
      (node (ref "PWR8") (pin "2") (pinfunction "2_2") (pintype "unspecified"))
    )
    (net (code "145") (name "Net-(IO8-Pad3)") (class "Default")
      (node (ref "IO8") (pin "3") (pinfunction "3_3") (pintype "unspecified"))
      (node (ref "R18") (pin "2") (pinfunction "2_2") (pintype "input"))
    )
    (net (code "146") (name "Net-(IO_1-K)") (class "Default")
      (node (ref "IO_1") (pin "1") (pinfunction "K_1") (pintype "input"))
      (node (ref "R1") (pin "1") (pinfunction "1_1") (pintype "input"))
    )
    (net (code "147") (name "Net-(IO_2-K)") (class "Default")
      (node (ref "IO_2") (pin "1") (pinfunction "K_1") (pintype "input"))
      (node (ref "R2") (pin "1") (pinfunction "1_1") (pintype "input"))
    )
    (net (code "148") (name "Net-(IO_3-K)") (class "Default")
      (node (ref "IO_3") (pin "1") (pinfunction "K_1") (pintype "input"))
      (node (ref "R3") (pin "1") (pinfunction "1_1") (pintype "input"))
    )
    (net (code "149") (name "Net-(IO_4-K)") (class "Default")
      (node (ref "IO_4") (pin "1") (pinfunction "K_1") (pintype "input"))
      (node (ref "R4") (pin "1") (pinfunction "1_1") (pintype "input"))
    )
    (net (code "150") (name "Net-(IO_5-K)") (class "Default")
      (node (ref "IO_5") (pin "1") (pinfunction "K_1") (pintype "input"))
      (node (ref "R5") (pin "1") (pinfunction "1_1") (pintype "input"))
    )
    (net (code "151") (name "Net-(IO_6-K)") (class "Default")
      (node (ref "IO_6") (pin "1") (pinfunction "K_1") (pintype "input"))
      (node (ref "R6") (pin "1") (pinfunction "1_1") (pintype "input"))
    )
    (net (code "152") (name "Net-(IO_7-K)") (class "Default")
      (node (ref "IO_7") (pin "1") (pinfunction "K_1") (pintype "input"))
      (node (ref "R7") (pin "1") (pinfunction "1_1") (pintype "input"))
    )
    (net (code "153") (name "Net-(IO_8-K)") (class "Default")
      (node (ref "IO_8") (pin "1") (pinfunction "K_1") (pintype "input"))
      (node (ref "R8") (pin "1") (pinfunction "1_1") (pintype "input"))
    )
    (net (code "154") (name "Net-(OPTO1-A)") (class "Default")
      (node (ref "OPTO1") (pin "1") (pinfunction "A_1") (pintype "input"))
      (node (ref "Q3") (pin "2") (pinfunction "E_2") (pintype "unspecified"))
    )
    (net (code "155") (name "Net-(OPTO2-A)") (class "Default")
      (node (ref "OPTO2") (pin "1") (pinfunction "A_1") (pintype "input"))
      (node (ref "Q4") (pin "2") (pinfunction "E_2") (pintype "unspecified"))
    )
    (net (code "156") (name "Net-(OPTO3-C)") (class "Default")
      (node (ref "OPTO3") (pin "2") (pinfunction "C_2") (pintype "input"))
      (node (ref "U13") (pin "1") (pinfunction "AN_1") (pintype "unspecified"))
    )
    (net (code "157") (name "Net-(OPTO4-C)") (class "Default")
      (node (ref "OPTO4") (pin "2") (pinfunction "C_2") (pintype "input"))
      (node (ref "U14") (pin "1") (pinfunction "AN_1") (pintype "unspecified"))
    )
    (net (code "158") (name "Net-(Q1-B)") (class "Default")
      (node (ref "Q1") (pin "1") (pinfunction "B_1") (pintype "unspecified"))
      (node (ref "Q2") (pin "3") (pinfunction "C_3") (pintype "unspecified"))
      (node (ref "R43") (pin "1") (pinfunction "1_1") (pintype "input"))
    )
    (net (code "159") (name "Net-(Q1-C)") (class "Default")
      (node (ref "Q1") (pin "3") (pinfunction "C_3") (pintype "unspecified"))
      (node (ref "U11") (pin "2") (pinfunction "CAT_2") (pintype "unspecified"))
    )
    (net (code "160") (name "Net-(Q1-E)") (class "Default")
      (node (ref "Q1") (pin "2") (pinfunction "E_2") (pintype "unspecified"))
      (node (ref "Q2") (pin "1") (pinfunction "B_1") (pintype "unspecified"))
      (node (ref "R29") (pin "2") (pinfunction "2_2") (pintype "input"))
    )
    (net (code "161") (name "Net-(Q2-E)") (class "Default")
      (node (ref "OPTOIN") (pin "2") (pinfunction "2_2") (pintype "unspecified"))
      (node (ref "Q2") (pin "2") (pinfunction "E_2") (pintype "unspecified"))
      (node (ref "R29") (pin "1") (pinfunction "1_1") (pintype "input"))
    )
    (net (code "162") (name "Net-(Q3-B)") (class "Default")
      (node (ref "Q3") (pin "1") (pinfunction "B_1") (pintype "unspecified"))
      (node (ref "U11") (pin "3") (pinfunction "EM_3") (pintype "unspecified"))
    )
    (net (code "163") (name "Net-(Q4-B)") (class "Default")
      (node (ref "Q4") (pin "1") (pinfunction "B_1") (pintype "unspecified"))
      (node (ref "U4") (pin "3") (pinfunction "EM_3") (pintype "unspecified"))
    )
    (net (code "164") (name "Net-(Q5-B)") (class "Default")
      (node (ref "Q5") (pin "1") (pinfunction "B_1") (pintype "unspecified"))
      (node (ref "Q6") (pin "3") (pinfunction "C_3") (pintype "unspecified"))
      (node (ref "R45") (pin "1") (pinfunction "1_1") (pintype "input"))
    )
    (net (code "165") (name "Net-(Q5-C)") (class "Default")
      (node (ref "Q5") (pin "3") (pinfunction "C_3") (pintype "unspecified"))
      (node (ref "U4") (pin "2") (pinfunction "CAT_2") (pintype "unspecified"))
    )
    (net (code "166") (name "Net-(Q5-E)") (class "Default")
      (node (ref "Q5") (pin "2") (pinfunction "E_2") (pintype "unspecified"))
      (node (ref "Q6") (pin "1") (pinfunction "B_1") (pintype "unspecified"))
      (node (ref "R44") (pin "2") (pinfunction "2_2") (pintype "input"))
    )
    (net (code "167") (name "Net-(Q6-E)") (class "Default")
      (node (ref "OPTOIN") (pin "4") (pinfunction "4_4") (pintype "unspecified"))
      (node (ref "Q6") (pin "2") (pinfunction "E_2") (pintype "unspecified"))
      (node (ref "R44") (pin "1") (pinfunction "1_1") (pintype "input"))
    )
    (net (code "168") (name "Net-(Q200-D)") (class "Default")
      (node (ref "Q200") (pin "3") (pinfunction "D_3") (pintype "unspecified"))
      (node (ref "R200") (pin "2") (pinfunction "2_2") (pintype "input"))
      (node (ref "R210") (pin "1") (pinfunction "1_1") (pintype "input"))
    )
    (net (code "169") (name "Net-(Q201-D)") (class "Default")
      (node (ref "Q201") (pin "3") (pinfunction "D_3") (pintype "unspecified"))
      (node (ref "R201") (pin "2") (pinfunction "2_2") (pintype "input"))
      (node (ref "R211") (pin "1") (pinfunction "1_1") (pintype "input"))
    )
    (net (code "170") (name "Net-(Q202-D)") (class "Default")
      (node (ref "Q202") (pin "3") (pinfunction "D_3") (pintype "unspecified"))
      (node (ref "R202") (pin "2") (pinfunction "2_2") (pintype "input"))
      (node (ref "R212") (pin "1") (pinfunction "1_1") (pintype "input"))
    )
    (net (code "171") (name "Net-(Q203-D)") (class "Default")
      (node (ref "Q203") (pin "3") (pinfunction "D_3") (pintype "unspecified"))
      (node (ref "R203") (pin "2") (pinfunction "2_2") (pintype "input"))
      (node (ref "R213") (pin "1") (pinfunction "1_1") (pintype "input"))
    )
    (net (code "172") (name "Net-(Q204-D)") (class "Default")
      (node (ref "Q204") (pin "3") (pinfunction "D_3") (pintype "unspecified"))
      (node (ref "R204") (pin "2") (pinfunction "2_2") (pintype "input"))
      (node (ref "R214") (pin "1") (pinfunction "1_1") (pintype "input"))
    )
    (net (code "173") (name "Net-(Q205-D)") (class "Default")
      (node (ref "Q205") (pin "3") (pinfunction "D_3") (pintype "unspecified"))
      (node (ref "R205") (pin "2") (pinfunction "2_2") (pintype "input"))
      (node (ref "R215") (pin "1") (pinfunction "1_1") (pintype "input"))
    )
    (net (code "174") (name "Net-(Q206-D)") (class "Default")
      (node (ref "Q206") (pin "3") (pinfunction "D_3") (pintype "unspecified"))
      (node (ref "R206") (pin "2") (pinfunction "2_2") (pintype "input"))
      (node (ref "R216") (pin "1") (pinfunction "1_1") (pintype "input"))
    )
    (net (code "175") (name "Net-(Q207-D)") (class "Default")
      (node (ref "Q207") (pin "3") (pinfunction "D_3") (pintype "unspecified"))
      (node (ref "R207") (pin "2") (pinfunction "2_2") (pintype "input"))
      (node (ref "R217") (pin "1") (pinfunction "1_1") (pintype "input"))
    )
    (net (code "176") (name "Net-(Q300-D)") (class "Default")
      (node (ref "Q300") (pin "3") (pinfunction "D_3") (pintype "unspecified"))
      (node (ref "R380") (pin "2") (pinfunction "2_2") (pintype "input"))
    )
    (net (code "177") (name "Net-(Q300-G)") (class "Default")
      (node (ref "C300") (pin "2") (pinfunction "2_2") (pintype "unspecified"))
      (node (ref "Q300") (pin "1") (pinfunction "G_1") (pintype "unspecified"))
      (node (ref "R300") (pin "2") (pinfunction "2_2") (pintype "input"))
      (node (ref "U300") (pin "4") (pinfunction "COL_4") (pintype "unspecified"))
    )
    (net (code "178") (name "Net-(Q301-D)") (class "Default")
      (node (ref "Q301") (pin "3") (pinfunction "D_3") (pintype "unspecified"))
      (node (ref "R381") (pin "2") (pinfunction "2_2") (pintype "input"))
    )
    (net (code "179") (name "Net-(Q301-G)") (class "Default")
      (node (ref "C301") (pin "2") (pinfunction "2_2") (pintype "unspecified"))
      (node (ref "Q301") (pin "1") (pinfunction "G_1") (pintype "unspecified"))
      (node (ref "R301") (pin "2") (pinfunction "2_2") (pintype "input"))
      (node (ref "U301") (pin "4") (pinfunction "COL_4") (pintype "unspecified"))
    )
    (net (code "180") (name "Net-(Q302-D)") (class "Default")
      (node (ref "Q302") (pin "3") (pinfunction "D_3") (pintype "unspecified"))
      (node (ref "R382") (pin "2") (pinfunction "2_2") (pintype "input"))
    )
    (net (code "181") (name "Net-(Q302-G)") (class "Default")
      (node (ref "C302") (pin "2") (pinfunction "2_2") (pintype "unspecified"))
      (node (ref "Q302") (pin "1") (pinfunction "G_1") (pintype "unspecified"))
      (node (ref "R302") (pin "2") (pinfunction "2_2") (pintype "input"))
      (node (ref "U302") (pin "4") (pinfunction "COL_4") (pintype "unspecified"))
    )
    (net (code "182") (name "Net-(Q303-D)") (class "Default")
      (node (ref "Q303") (pin "3") (pinfunction "D_3") (pintype "unspecified"))
      (node (ref "R383") (pin "2") (pinfunction "2_2") (pintype "input"))
    )
    (net (code "183") (name "Net-(Q303-G)") (class "Default")
      (node (ref "C303") (pin "2") (pinfunction "2_2") (pintype "unspecified"))
      (node (ref "Q303") (pin "1") (pinfunction "G_1") (pintype "unspecified"))
      (node (ref "R303") (pin "2") (pinfunction "2_2") (pintype "input"))
      (node (ref "U303") (pin "4") (pinfunction "COL_4") (pintype "unspecified"))
    )
    (net (code "184") (name "Net-(Q304-D)") (class "Default")
      (node (ref "Q304") (pin "3") (pinfunction "D_3") (pintype "unspecified"))
      (node (ref "R384") (pin "2") (pinfunction "2_2") (pintype "input"))
    )
    (net (code "185") (name "Net-(Q304-G)") (class "Default")
      (node (ref "C304") (pin "2") (pinfunction "2_2") (pintype "unspecified"))
      (node (ref "Q304") (pin "1") (pinfunction "G_1") (pintype "unspecified"))
      (node (ref "R304") (pin "2") (pinfunction "2_2") (pintype "input"))
      (node (ref "U304") (pin "4") (pinfunction "COL_4") (pintype "unspecified"))
    )
    (net (code "186") (name "Net-(Q305-D)") (class "Default")
      (node (ref "Q305") (pin "3") (pinfunction "D_3") (pintype "unspecified"))
      (node (ref "R385") (pin "2") (pinfunction "2_2") (pintype "input"))
    )
    (net (code "187") (name "Net-(Q305-G)") (class "Default")
      (node (ref "C305") (pin "2") (pinfunction "2_2") (pintype "unspecified"))
      (node (ref "Q305") (pin "1") (pinfunction "G_1") (pintype "unspecified"))
      (node (ref "R305") (pin "2") (pinfunction "2_2") (pintype "input"))
      (node (ref "U305") (pin "4") (pinfunction "COL_4") (pintype "unspecified"))
    )
    (net (code "188") (name "Net-(Q306-D)") (class "Default")
      (node (ref "Q306") (pin "3") (pinfunction "D_3") (pintype "unspecified"))
      (node (ref "R386") (pin "2") (pinfunction "2_2") (pintype "input"))
    )
    (net (code "189") (name "Net-(Q306-G)") (class "Default")
      (node (ref "C306") (pin "2") (pinfunction "2_2") (pintype "unspecified"))
      (node (ref "Q306") (pin "1") (pinfunction "G_1") (pintype "unspecified"))
      (node (ref "R306") (pin "2") (pinfunction "2_2") (pintype "input"))
      (node (ref "U306") (pin "4") (pinfunction "COL_4") (pintype "unspecified"))
    )
    (net (code "190") (name "Net-(Q307-D)") (class "Default")
      (node (ref "Q307") (pin "3") (pinfunction "D_3") (pintype "unspecified"))
      (node (ref "R387") (pin "2") (pinfunction "2_2") (pintype "input"))
    )
    (net (code "191") (name "Net-(Q307-G)") (class "Default")
      (node (ref "C307") (pin "2") (pinfunction "2_2") (pintype "unspecified"))
      (node (ref "Q307") (pin "1") (pinfunction "G_1") (pintype "unspecified"))
      (node (ref "R307") (pin "2") (pinfunction "2_2") (pintype "input"))
      (node (ref "U307") (pin "4") (pinfunction "COL_4") (pintype "unspecified"))
    )
    (net (code "192") (name "Net-(Q310-D)") (class "Default")
      (node (ref "Q310") (pin "3") (pinfunction "D_3") (pintype "unspecified"))
      (node (ref "R310") (pin "2") (pinfunction "2_2") (pintype "input"))
    )
    (net (code "193") (name "Net-(Q311-D)") (class "Default")
      (node (ref "Q311") (pin "3") (pinfunction "D_3") (pintype "unspecified"))
      (node (ref "R311") (pin "2") (pinfunction "2_2") (pintype "input"))
    )
    (net (code "194") (name "Net-(Q312-D)") (class "Default")
      (node (ref "Q312") (pin "3") (pinfunction "D_3") (pintype "unspecified"))
      (node (ref "R312") (pin "2") (pinfunction "2_2") (pintype "input"))
    )
    (net (code "195") (name "Net-(Q313-D)") (class "Default")
      (node (ref "Q313") (pin "3") (pinfunction "D_3") (pintype "unspecified"))
      (node (ref "R313") (pin "2") (pinfunction "2_2") (pintype "input"))
    )
    (net (code "196") (name "Net-(Q314-D)") (class "Default")
      (node (ref "Q314") (pin "3") (pinfunction "D_3") (pintype "unspecified"))
      (node (ref "R314") (pin "2") (pinfunction "2_2") (pintype "input"))
    )
    (net (code "197") (name "Net-(Q315-D)") (class "Default")
      (node (ref "Q315") (pin "3") (pinfunction "D_3") (pintype "unspecified"))
      (node (ref "R315") (pin "2") (pinfunction "2_2") (pintype "input"))
    )
    (net (code "198") (name "Net-(Q316-D)") (class "Default")
      (node (ref "Q316") (pin "3") (pinfunction "D_3") (pintype "unspecified"))
      (node (ref "R316") (pin "2") (pinfunction "2_2") (pintype "input"))
    )
    (net (code "199") (name "Net-(Q317-D)") (class "Default")
      (node (ref "Q317") (pin "3") (pinfunction "D_3") (pintype "unspecified"))
      (node (ref "R317") (pin "2") (pinfunction "2_2") (pintype "input"))
    )
    (net (code "200") (name "Net-(R330-Pad1)") (class "Default")
      (node (ref "R330") (pin "1") (pinfunction "1_1") (pintype "input"))
      (node (ref "R340") (pin "2") (pinfunction "2_2") (pintype "input"))
    )
    (net (code "201") (name "Net-(R331-Pad1)") (class "Default")
      (node (ref "R331") (pin "1") (pinfunction "1_1") (pintype "input"))
      (node (ref "R341") (pin "2") (pinfunction "2_2") (pintype "input"))
    )
    (net (code "202") (name "Net-(R332-Pad1)") (class "Default")
      (node (ref "R332") (pin "1") (pinfunction "1_1") (pintype "input"))
      (node (ref "R342") (pin "2") (pinfunction "2_2") (pintype "input"))
    )
    (net (code "203") (name "Net-(R333-Pad1)") (class "Default")
      (node (ref "R333") (pin "1") (pinfunction "1_1") (pintype "input"))
      (node (ref "R343") (pin "2") (pinfunction "2_2") (pintype "input"))
    )
    (net (code "204") (name "Net-(R334-Pad1)") (class "Default")
      (node (ref "R334") (pin "1") (pinfunction "1_1") (pintype "input"))
      (node (ref "R344") (pin "2") (pinfunction "2_2") (pintype "input"))
    )
    (net (code "205") (name "Net-(R335-Pad1)") (class "Default")
      (node (ref "R335") (pin "1") (pinfunction "1_1") (pintype "input"))
      (node (ref "R345") (pin "2") (pinfunction "2_2") (pintype "input"))
    )
    (net (code "206") (name "Net-(R336-Pad1)") (class "Default")
      (node (ref "R336") (pin "1") (pinfunction "1_1") (pintype "input"))
      (node (ref "R346") (pin "2") (pinfunction "2_2") (pintype "input"))
    )
    (net (code "207") (name "Net-(R337-Pad1)") (class "Default")
      (node (ref "R337") (pin "1") (pinfunction "1_1") (pintype "input"))
      (node (ref "R347") (pin "2") (pinfunction "2_2") (pintype "input"))
    )
    (net (code "208") (name "Net-(R340-Pad1)") (class "Default")
      (node (ref "R340") (pin "1") (pinfunction "1_1") (pintype "input"))
      (node (ref "R350") (pin "2") (pinfunction "2_2") (pintype "input"))
    )
    (net (code "209") (name "Net-(R341-Pad1)") (class "Default")
      (node (ref "R341") (pin "1") (pinfunction "1_1") (pintype "input"))
      (node (ref "R351") (pin "2") (pinfunction "2_2") (pintype "input"))
    )
    (net (code "210") (name "Net-(R342-Pad1)") (class "Default")
      (node (ref "R342") (pin "1") (pinfunction "1_1") (pintype "input"))
      (node (ref "R352") (pin "2") (pinfunction "2_2") (pintype "input"))
    )
    (net (code "211") (name "Net-(R343-Pad1)") (class "Default")
      (node (ref "R343") (pin "1") (pinfunction "1_1") (pintype "input"))
      (node (ref "R353") (pin "2") (pinfunction "2_2") (pintype "input"))
    )
    (net (code "212") (name "Net-(R344-Pad1)") (class "Default")
      (node (ref "R344") (pin "1") (pinfunction "1_1") (pintype "input"))
      (node (ref "R354") (pin "2") (pinfunction "2_2") (pintype "input"))
    )
    (net (code "213") (name "Net-(R345-Pad1)") (class "Default")
      (node (ref "R345") (pin "1") (pinfunction "1_1") (pintype "input"))
      (node (ref "R355") (pin "2") (pinfunction "2_2") (pintype "input"))
    )
    (net (code "214") (name "Net-(R346-Pad1)") (class "Default")
      (node (ref "R346") (pin "1") (pinfunction "1_1") (pintype "input"))
      (node (ref "R356") (pin "2") (pinfunction "2_2") (pintype "input"))
    )
    (net (code "215") (name "Net-(R347-Pad1)") (class "Default")
      (node (ref "R347") (pin "1") (pinfunction "1_1") (pintype "input"))
      (node (ref "R357") (pin "2") (pinfunction "2_2") (pintype "input"))
    )
    (net (code "216") (name "Net-(R350-Pad1)") (class "Default")
      (node (ref "R350") (pin "1") (pinfunction "1_1") (pintype "input"))
      (node (ref "R360") (pin "2") (pinfunction "2_2") (pintype "input"))
    )
    (net (code "217") (name "Net-(R351-Pad1)") (class "Default")
      (node (ref "R351") (pin "1") (pinfunction "1_1") (pintype "input"))
      (node (ref "R361") (pin "2") (pinfunction "2_2") (pintype "input"))
    )
    (net (code "218") (name "Net-(R352-Pad1)") (class "Default")
      (node (ref "R352") (pin "1") (pinfunction "1_1") (pintype "input"))
      (node (ref "R362") (pin "2") (pinfunction "2_2") (pintype "input"))
    )
    (net (code "219") (name "Net-(R353-Pad1)") (class "Default")
      (node (ref "R353") (pin "1") (pinfunction "1_1") (pintype "input"))
      (node (ref "R363") (pin "2") (pinfunction "2_2") (pintype "input"))
    )
    (net (code "220") (name "Net-(R354-Pad1)") (class "Default")
      (node (ref "R354") (pin "1") (pinfunction "1_1") (pintype "input"))
      (node (ref "R364") (pin "2") (pinfunction "2_2") (pintype "input"))
    )
    (net (code "221") (name "Net-(R355-Pad1)") (class "Default")
      (node (ref "R355") (pin "1") (pinfunction "1_1") (pintype "input"))
      (node (ref "R365") (pin "2") (pinfunction "2_2") (pintype "input"))
    )
    (net (code "222") (name "Net-(R356-Pad1)") (class "Default")
      (node (ref "R356") (pin "1") (pinfunction "1_1") (pintype "input"))
      (node (ref "R366") (pin "2") (pinfunction "2_2") (pintype "input"))
    )
    (net (code "223") (name "Net-(R357-Pad1)") (class "Default")
      (node (ref "R357") (pin "1") (pinfunction "1_1") (pintype "input"))
      (node (ref "R367") (pin "2") (pinfunction "2_2") (pintype "input"))
    )
    (net (code "224") (name "Net-(R360-Pad1)") (class "Default")
      (node (ref "R360") (pin "1") (pinfunction "1_1") (pintype "input"))
      (node (ref "R370") (pin "2") (pinfunction "2_2") (pintype "input"))
    )
    (net (code "225") (name "Net-(R361-Pad1)") (class "Default")
      (node (ref "R361") (pin "1") (pinfunction "1_1") (pintype "input"))
      (node (ref "R371") (pin "2") (pinfunction "2_2") (pintype "input"))
    )
    (net (code "226") (name "Net-(R362-Pad1)") (class "Default")
      (node (ref "R362") (pin "1") (pinfunction "1_1") (pintype "input"))
      (node (ref "R372") (pin "2") (pinfunction "2_2") (pintype "input"))
    )
    (net (code "227") (name "Net-(R363-Pad1)") (class "Default")
      (node (ref "R363") (pin "1") (pinfunction "1_1") (pintype "input"))
      (node (ref "R373") (pin "2") (pinfunction "2_2") (pintype "input"))
    )
    (net (code "228") (name "Net-(R364-Pad1)") (class "Default")
      (node (ref "R364") (pin "1") (pinfunction "1_1") (pintype "input"))
      (node (ref "R374") (pin "2") (pinfunction "2_2") (pintype "input"))
    )
    (net (code "229") (name "Net-(R365-Pad1)") (class "Default")
      (node (ref "R365") (pin "1") (pinfunction "1_1") (pintype "input"))
      (node (ref "R375") (pin "2") (pinfunction "2_2") (pintype "input"))
    )
    (net (code "230") (name "Net-(R366-Pad1)") (class "Default")
      (node (ref "R366") (pin "1") (pinfunction "1_1") (pintype "input"))
      (node (ref "R376") (pin "2") (pinfunction "2_2") (pintype "input"))
    )
    (net (code "231") (name "Net-(R367-Pad1)") (class "Default")
      (node (ref "R367") (pin "1") (pinfunction "1_1") (pintype "input"))
      (node (ref "R377") (pin "2") (pinfunction "2_2") (pintype "input"))
    )
    (net (code "232") (name "Net-(REL0-K)") (class "Default")
      (node (ref "R220") (pin "2") (pinfunction "2_2") (pintype "input"))
      (node (ref "REL0") (pin "1") (pinfunction "K_1") (pintype "input"))
    )
    (net (code "233") (name "Net-(REL1-K)") (class "Default")
      (node (ref "R221") (pin "2") (pinfunction "2_2") (pintype "input"))
      (node (ref "REL1") (pin "1") (pinfunction "K_1") (pintype "input"))
    )
    (net (code "234") (name "Net-(REL2-K)") (class "Default")
      (node (ref "R222") (pin "2") (pinfunction "2_2") (pintype "input"))
      (node (ref "REL2") (pin "1") (pinfunction "K_1") (pintype "input"))
    )
    (net (code "235") (name "Net-(REL3-K)") (class "Default")
      (node (ref "R223") (pin "2") (pinfunction "2_2") (pintype "input"))
      (node (ref "REL3") (pin "1") (pinfunction "K_1") (pintype "input"))
    )
    (net (code "236") (name "Net-(REL4-K)") (class "Default")
      (node (ref "R224") (pin "2") (pinfunction "2_2") (pintype "input"))
      (node (ref "REL4") (pin "1") (pinfunction "K_1") (pintype "input"))
    )
    (net (code "237") (name "Net-(REL5-K)") (class "Default")
      (node (ref "R225") (pin "2") (pinfunction "2_2") (pintype "input"))
      (node (ref "REL5") (pin "1") (pinfunction "K_1") (pintype "input"))
    )
    (net (code "238") (name "Net-(REL6-K)") (class "Default")
      (node (ref "R226") (pin "2") (pinfunction "2_2") (pintype "input"))
      (node (ref "REL6") (pin "1") (pinfunction "K_1") (pintype "input"))
    )
    (net (code "239") (name "Net-(REL7-K)") (class "Default")
      (node (ref "R227") (pin "2") (pinfunction "2_2") (pintype "input"))
      (node (ref "REL7") (pin "1") (pinfunction "K_1") (pintype "input"))
    )
    (net (code "240") (name "Net-(REL200-Pad5)") (class "Default")
      (node (ref "REL200") (pin "5") (pinfunction "5_5") (pintype "input"))
      (node (ref "TP5") (pin "1") (pinfunction "1_1") (pintype "unspecified"))
    )
    (net (code "241") (name "Net-(REL200-Pad6)") (class "Default")
      (node (ref "REL200") (pin "6") (pinfunction "6_6") (pintype "input"))
      (node (ref "TP2") (pin "1") (pinfunction "1_1") (pintype "unspecified"))
    )
    (net (code "242") (name "Net-(REL200-Pad7)") (class "Default")
      (node (ref "REL200") (pin "7") (pinfunction "7_7") (pintype "input"))
      (node (ref "TP3") (pin "1") (pinfunction "1_1") (pintype "unspecified"))
    )
    (net (code "243") (name "Net-(REL201-COM)") (class "Default")
      (node (ref "REL201") (pin "4") (pinfunction "COM_4") (pintype "unspecified"))
      (node (ref "TP6") (pin "1") (pinfunction "1_1") (pintype "unspecified"))
    )
    (net (code "244") (name "Net-(REL202-COM)") (class "Default")
      (node (ref "REL202") (pin "4") (pinfunction "COM_4") (pintype "unspecified"))
      (node (ref "TP20") (pin "1") (pinfunction "1_1") (pintype "unspecified"))
    )
    (net (code "245") (name "Net-(REL203-COM)") (class "Default")
      (node (ref "REL203") (pin "4") (pinfunction "COM_4") (pintype "unspecified"))
      (node (ref "TP19") (pin "1") (pinfunction "1_1") (pintype "unspecified"))
    )
    (net (code "246") (name "Net-(REL204-COM)") (class "Default")
      (node (ref "REL204") (pin "4") (pinfunction "COM_4") (pintype "unspecified"))
      (node (ref "TP18") (pin "1") (pinfunction "1_1") (pintype "unspecified"))
    )
    (net (code "247") (name "Net-(REL205-COM)") (class "Default")
      (node (ref "REL205") (pin "4") (pinfunction "COM_4") (pintype "unspecified"))
      (node (ref "TP17") (pin "1") (pinfunction "1_1") (pintype "unspecified"))
    )
    (net (code "248") (name "Net-(REL206-COM)") (class "Default")
      (node (ref "REL206") (pin "4") (pinfunction "COM_4") (pintype "unspecified"))
      (node (ref "TP16") (pin "1") (pinfunction "1_1") (pintype "unspecified"))
    )
    (net (code "249") (name "Net-(REL207-COM)") (class "Default")
      (node (ref "REL207") (pin "4") (pinfunction "COM_4") (pintype "unspecified"))
      (node (ref "TP15") (pin "1") (pinfunction "1_1") (pintype "unspecified"))
    )
    (net (code "250") (name "Net-(U2-AC(N))") (class "Default")
      (node (ref "F1") (pin "1") (pinfunction "1_1") (pintype "unspecified"))
      (node (ref "R57") (pin "1") (pinfunction "1_1") (pintype "unspecified"))
      (node (ref "U2") (pin "1") (pinfunction "AC(N)_1") (pintype "unspecified"))
    )
    (net (code "251") (name "Net-(U4-AN)") (class "Default")
      (node (ref "OPTOIN") (pin "3") (pinfunction "3_3") (pintype "unspecified"))
      (node (ref "R45") (pin "2") (pinfunction "2_2") (pintype "input"))
      (node (ref "U4") (pin "1") (pinfunction "AN_1") (pintype "unspecified"))
    )
    (net (code "252") (name "Net-(U11-AN)") (class "Default")
      (node (ref "OPTOIN") (pin "1") (pinfunction "1_1") (pintype "unspecified"))
      (node (ref "R43") (pin "2") (pinfunction "2_2") (pintype "input"))
      (node (ref "U11") (pin "1") (pinfunction "AN_1") (pintype "unspecified"))
    )
    (net (code "253") (name "Net-(U13-CAT)") (class "Default")
      (node (ref "R38") (pin "2") (pinfunction "2_2") (pintype "input"))
      (node (ref "U13") (pin "2") (pinfunction "CAT_2") (pintype "unspecified"))
    )
    (net (code "254") (name "Net-(U13-COL)") (class "Default")
      (node (ref "OPTOOUT") (pin "1") (pinfunction "1_1") (pintype "unspecified"))
      (node (ref "U13") (pin "4") (pinfunction "COL_4") (pintype "unspecified"))
    )
    (net (code "255") (name "Net-(U13-EM)") (class "Default")
      (node (ref "OPTOOUT") (pin "2") (pinfunction "2_2") (pintype "unspecified"))
      (node (ref "U13") (pin "3") (pinfunction "EM_3") (pintype "unspecified"))
    )
    (net (code "256") (name "Net-(U14-CAT)") (class "Default")
      (node (ref "R39") (pin "2") (pinfunction "2_2") (pintype "input"))
      (node (ref "U14") (pin "2") (pinfunction "CAT_2") (pintype "unspecified"))
    )
    (net (code "257") (name "Net-(U14-COL)") (class "Default")
      (node (ref "OPTOOUT") (pin "3") (pinfunction "3_3") (pintype "unspecified"))
      (node (ref "U14") (pin "4") (pinfunction "COL_4") (pintype "unspecified"))
    )
    (net (code "258") (name "Net-(U14-EM)") (class "Default")
      (node (ref "OPTOOUT") (pin "4") (pinfunction "4_4") (pintype "unspecified"))
      (node (ref "U14") (pin "3") (pinfunction "EM_3") (pintype "unspecified"))
    )
    (net (code "259") (name "Net-(U300-AN)") (class "Default")
      (node (ref "R310") (pin "1") (pinfunction "1_1") (pintype "input"))
      (node (ref "U300") (pin "1") (pinfunction "AN_1") (pintype "unspecified"))
    )
    (net (code "260") (name "Net-(U301-AN)") (class "Default")
      (node (ref "R311") (pin "1") (pinfunction "1_1") (pintype "input"))
      (node (ref "U301") (pin "1") (pinfunction "AN_1") (pintype "unspecified"))
    )
    (net (code "261") (name "Net-(U302-AN)") (class "Default")
      (node (ref "R312") (pin "1") (pinfunction "1_1") (pintype "input"))
      (node (ref "U302") (pin "1") (pinfunction "AN_1") (pintype "unspecified"))
    )
    (net (code "262") (name "Net-(U303-AN)") (class "Default")
      (node (ref "R313") (pin "1") (pinfunction "1_1") (pintype "input"))
      (node (ref "U303") (pin "1") (pinfunction "AN_1") (pintype "unspecified"))
    )
    (net (code "263") (name "Net-(U304-AN)") (class "Default")
      (node (ref "R314") (pin "1") (pinfunction "1_1") (pintype "input"))
      (node (ref "U304") (pin "1") (pinfunction "AN_1") (pintype "unspecified"))
    )
    (net (code "264") (name "Net-(U305-AN)") (class "Default")
      (node (ref "R315") (pin "1") (pinfunction "1_1") (pintype "input"))
      (node (ref "U305") (pin "1") (pinfunction "AN_1") (pintype "unspecified"))
    )
    (net (code "265") (name "Net-(U306-AN)") (class "Default")
      (node (ref "R316") (pin "1") (pinfunction "1_1") (pintype "input"))
      (node (ref "U306") (pin "1") (pinfunction "AN_1") (pintype "unspecified"))
    )
    (net (code "266") (name "Net-(U307-AN)") (class "Default")
      (node (ref "R317") (pin "1") (pinfunction "1_1") (pintype "input"))
      (node (ref "U307") (pin "1") (pinfunction "AN_1") (pintype "unspecified"))
    )
    (net (code "267") (name "Opto0") (class "Default")
      (node (ref "GP1") (pin "7") (pinfunction "GP5_7") (pintype "unspecified"))
      (node (ref "OPTO1") (pin "2") (pinfunction "C_2") (pintype "input"))
      (node (ref "R19") (pin "1") (pinfunction "1_1") (pintype "input"))
    )
    (net (code "268") (name "Opto1") (class "Default")
      (node (ref "GP1") (pin "17") (pinfunction "GP13_17") (pintype "unspecified"))
      (node (ref "OPTO2") (pin "2") (pinfunction "C_2") (pintype "input"))
      (node (ref "R46") (pin "1") (pinfunction "1_1") (pintype "input"))
    )
    (net (code "269") (name "Opto2") (class "Default")
      (node (ref "GP1") (pin "19") (pinfunction "GP14_19") (pintype "unspecified"))
      (node (ref "R38") (pin "1") (pinfunction "1_1") (pintype "input"))
    )
    (net (code "270") (name "Opto3") (class "Default")
      (node (ref "GP1") (pin "20") (pinfunction "GP15_20") (pintype "unspecified"))
      (node (ref "R39") (pin "1") (pinfunction "1_1") (pintype "input"))
    )
    (net (code "271") (name "RelEnable") (class "Default")
      (node (ref "GP1") (pin "12") (pinfunction "GP9_12") (pintype "unspecified"))
      (node (ref "R200") (pin "1") (pinfunction "1_1") (pintype "input"))
      (node (ref "R201") (pin "1") (pinfunction "1_1") (pintype "input"))
      (node (ref "R202") (pin "1") (pinfunction "1_1") (pintype "input"))
      (node (ref "R203") (pin "1") (pinfunction "1_1") (pintype "input"))
      (node (ref "R204") (pin "1") (pinfunction "1_1") (pintype "input"))
      (node (ref "R205") (pin "1") (pinfunction "1_1") (pintype "input"))
      (node (ref "R206") (pin "1") (pinfunction "1_1") (pintype "input"))
      (node (ref "R207") (pin "1") (pinfunction "1_1") (pintype "input"))
      (node (ref "R208") (pin "1") (pinfunction "1_1") (pintype "input"))
    )
    (net (code "272") (name "SCL") (class "Default")
      (node (ref "GP1") (pin "27") (pinfunction "GP21_27") (pintype "unspecified"))
      (node (ref "QWIIC") (pin "4") (pinfunction "SCL_4") (pintype "unspecified"))
      (node (ref "R9") (pin "1") (pinfunction "1_1") (pintype "input"))
      (node (ref "SCL") (pin "1") (pinfunction "1_1") (pintype "unspecified"))
      (node (ref "U1") (pin "2") (pinfunction "SCK_2") (pintype "unspecified"))
    )
    (net (code "273") (name "SDA") (class "Default")
      (node (ref "GP1") (pin "26") (pinfunction "GP20_26") (pintype "unspecified"))
      (node (ref "QWIIC") (pin "3") (pinfunction "SDA_3") (pintype "unspecified"))
      (node (ref "R10") (pin "1") (pinfunction "1_1") (pintype "input"))
      (node (ref "SDA") (pin "1") (pinfunction "1_1") (pintype "unspecified"))
      (node (ref "U1") (pin "1") (pinfunction "SDA_1") (pintype "unspecified"))
    )
    (net (code "274") (name "Vref") (class "Default")
      (node (ref "C6") (pin "2") (pinfunction "2_2") (pintype "unspecified"))
      (node (ref "D19") (pin "2") (pinfunction "A_2") (pintype "unspecified"))
      (node (ref "GP1") (pin "35") (pinfunction "ADC_VREF_35") (pintype "unspecified"))
      (node (ref "R40") (pin "1") (pinfunction "1_1") (pintype "input"))
      (node (ref "R41") (pin "2") (pinfunction "2_2") (pintype "input"))
    )
    (net (code "275") (name "unconnected-(GP1-3V3_EN-Pad37)") (class "Default")
      (node (ref "GP1") (pin "37") (pinfunction "3V3_EN_37") (pintype "unspecified+no_connect"))
    )
    (net (code "276") (name "unconnected-(GP1-GND-Pad42)") (class "Default")
      (node (ref "GP1") (pin "42") (pinfunction "GND_42") (pintype "unspecified+no_connect"))
    )
    (net (code "277") (name "unconnected-(GP1-RUN-Pad30)") (class "Default")
      (node (ref "GP1") (pin "30") (pinfunction "RUN_30") (pintype "unspecified+no_connect"))
    )
    (net (code "278") (name "unconnected-(GP1-SWCLK-Pad41)") (class "Default")
      (node (ref "GP1") (pin "41") (pinfunction "SWCLK_41") (pintype "unspecified+no_connect"))
    )
    (net (code "279") (name "unconnected-(GP1-SWDIO-Pad43)") (class "Default")
      (node (ref "GP1") (pin "43") (pinfunction "SWDIO_43") (pintype "unspecified+no_connect"))
    )
    (net (code "280") (name "unconnected-(GP1-TP1-Pad44)") (class "Default")
      (node (ref "GP1") (pin "44") (pinfunction "TP1_44") (pintype "unspecified+no_connect"))
    )
    (net (code "281") (name "unconnected-(GP1-TP2-Pad45)") (class "Default")
      (node (ref "GP1") (pin "45") (pinfunction "TP2_45") (pintype "unspecified+no_connect"))
    )
    (net (code "282") (name "unconnected-(GP1-TP3-Pad46)") (class "Default")
      (node (ref "GP1") (pin "46") (pinfunction "TP3_46") (pintype "unspecified+no_connect"))
    )
    (net (code "283") (name "unconnected-(GP1-TP4-Pad47)") (class "Default")
      (node (ref "GP1") (pin "47") (pinfunction "TP4_47") (pintype "unspecified+no_connect"))
    )
    (net (code "284") (name "unconnected-(GP1-TP5-Pad48)") (class "Default")
      (node (ref "GP1") (pin "48") (pinfunction "TP5_48") (pintype "unspecified+no_connect"))
    )
    (net (code "285") (name "unconnected-(GP1-TP6-Pad49)") (class "Default")
      (node (ref "GP1") (pin "49") (pinfunction "TP6_49") (pintype "unspecified+no_connect"))
    )
    (net (code "286") (name "unconnected-(GP1-USB_SHIELD-Pad50)") (class "Default")
      (node (ref "GP1") (pin "50") (pinfunction "USB_SHIELD_50") (pintype "unspecified+no_connect"))
    )
    (net (code "287") (name "unconnected-(REL200-Pad3)") (class "Default")
      (node (ref "REL200") (pin "3") (pinfunction "3_3") (pintype "input+no_connect"))
    )
    (net (code "288") (name "unconnected-(REL200-Pad4)") (class "Default")
      (node (ref "REL200") (pin "4") (pinfunction "4_4") (pintype "input+no_connect"))
    )
    (net (code "289") (name "unconnected-(REL201-NC-Pad3)") (class "Default")
      (node (ref "REL201") (pin "3") (pinfunction "NC_3") (pintype "unspecified+no_connect"))
    )
    (net (code "290") (name "unconnected-(REL202-NC-Pad3)") (class "Default")
      (node (ref "REL202") (pin "3") (pinfunction "NC_3") (pintype "unspecified+no_connect"))
    )
    (net (code "291") (name "unconnected-(REL203-NC-Pad3)") (class "Default")
      (node (ref "REL203") (pin "3") (pinfunction "NC_3") (pintype "unspecified+no_connect"))
    )
    (net (code "292") (name "unconnected-(REL204-NC-Pad3)") (class "Default")
      (node (ref "REL204") (pin "3") (pinfunction "NC_3") (pintype "unspecified+no_connect"))
    )
    (net (code "293") (name "unconnected-(REL205-NC-Pad3)") (class "Default")
      (node (ref "REL205") (pin "3") (pinfunction "NC_3") (pintype "unspecified+no_connect"))
    )
    (net (code "294") (name "unconnected-(REL206-NC-Pad3)") (class "Default")
      (node (ref "REL206") (pin "3") (pinfunction "NC_3") (pintype "unspecified+no_connect"))
    )
    (net (code "295") (name "unconnected-(REL207-NC-Pad3)") (class "Default")
      (node (ref "REL207") (pin "3") (pinfunction "NC_3") (pintype "unspecified+no_connect"))
    )
    (net (code "296") (name "unconnected-(U7-NC-Pad3)") (class "Default")
      (node (ref "U7") (pin "3") (pinfunction "NC_3") (pintype "unspecified+no_connect"))
    )
  )
)
